# RF08bOmnibus.net
KiCad netlist of a schematic drawn in EAGLE
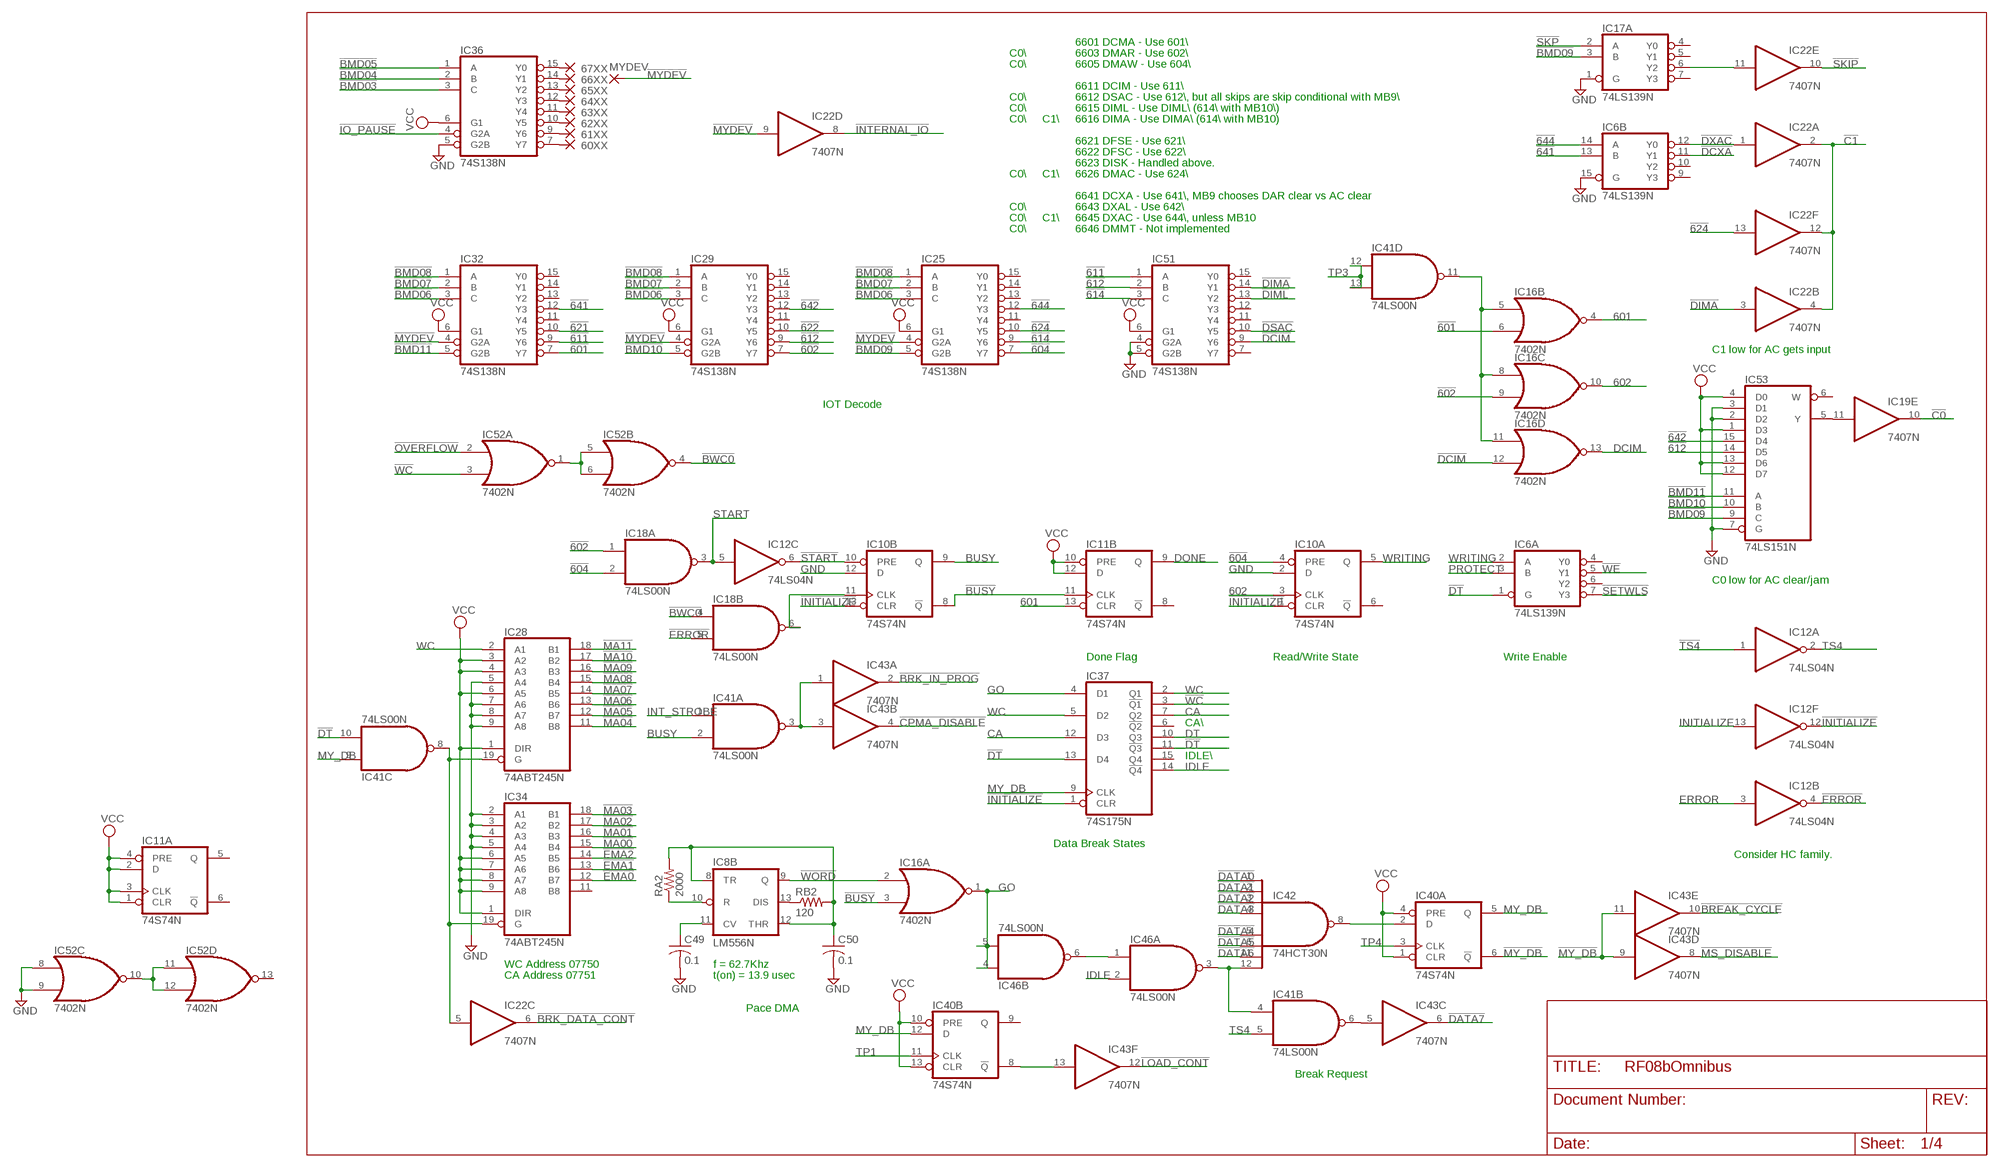
[diagram p0: schematic, sheet 1]
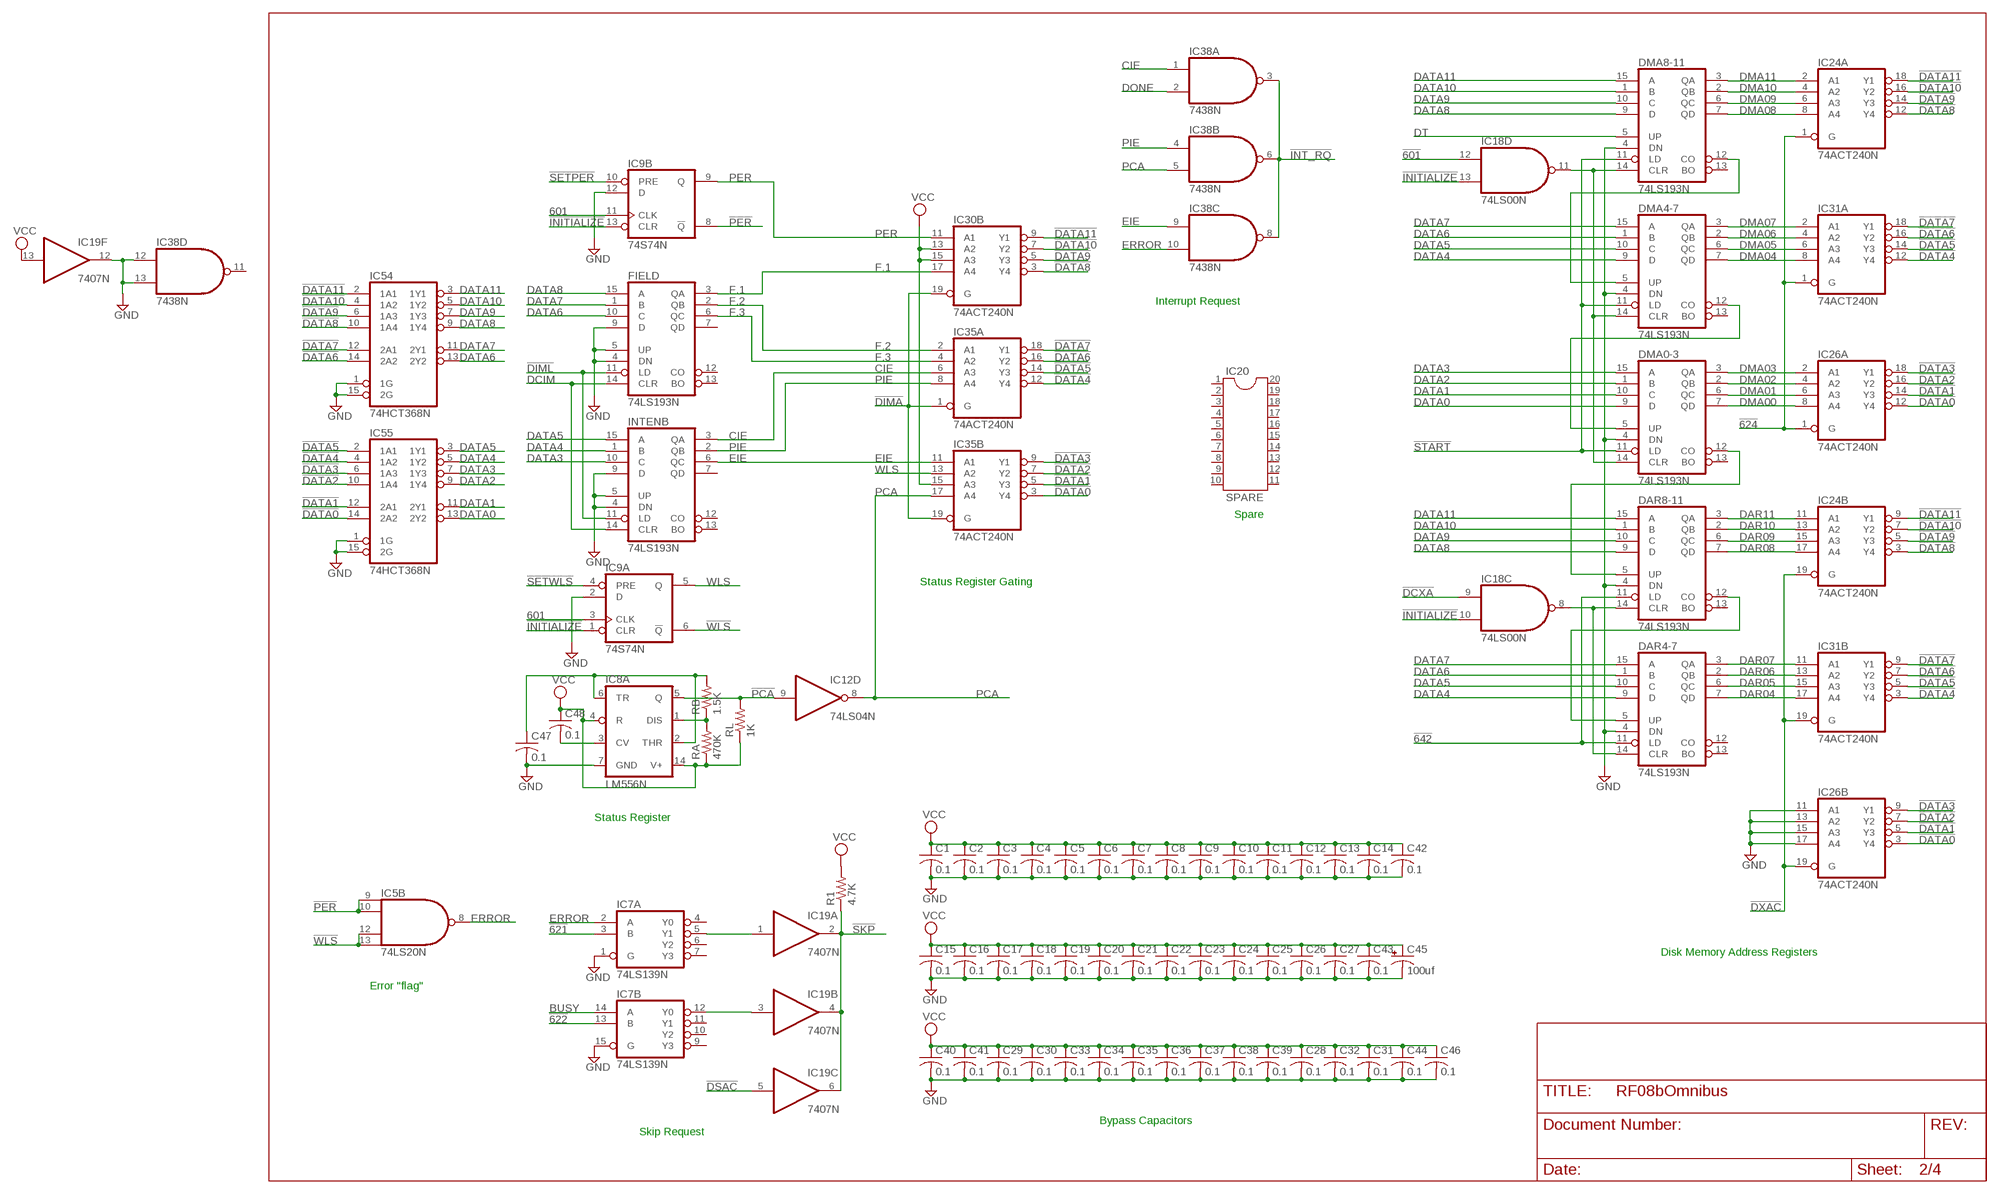
[diagram p1: schematic, sheet 2]
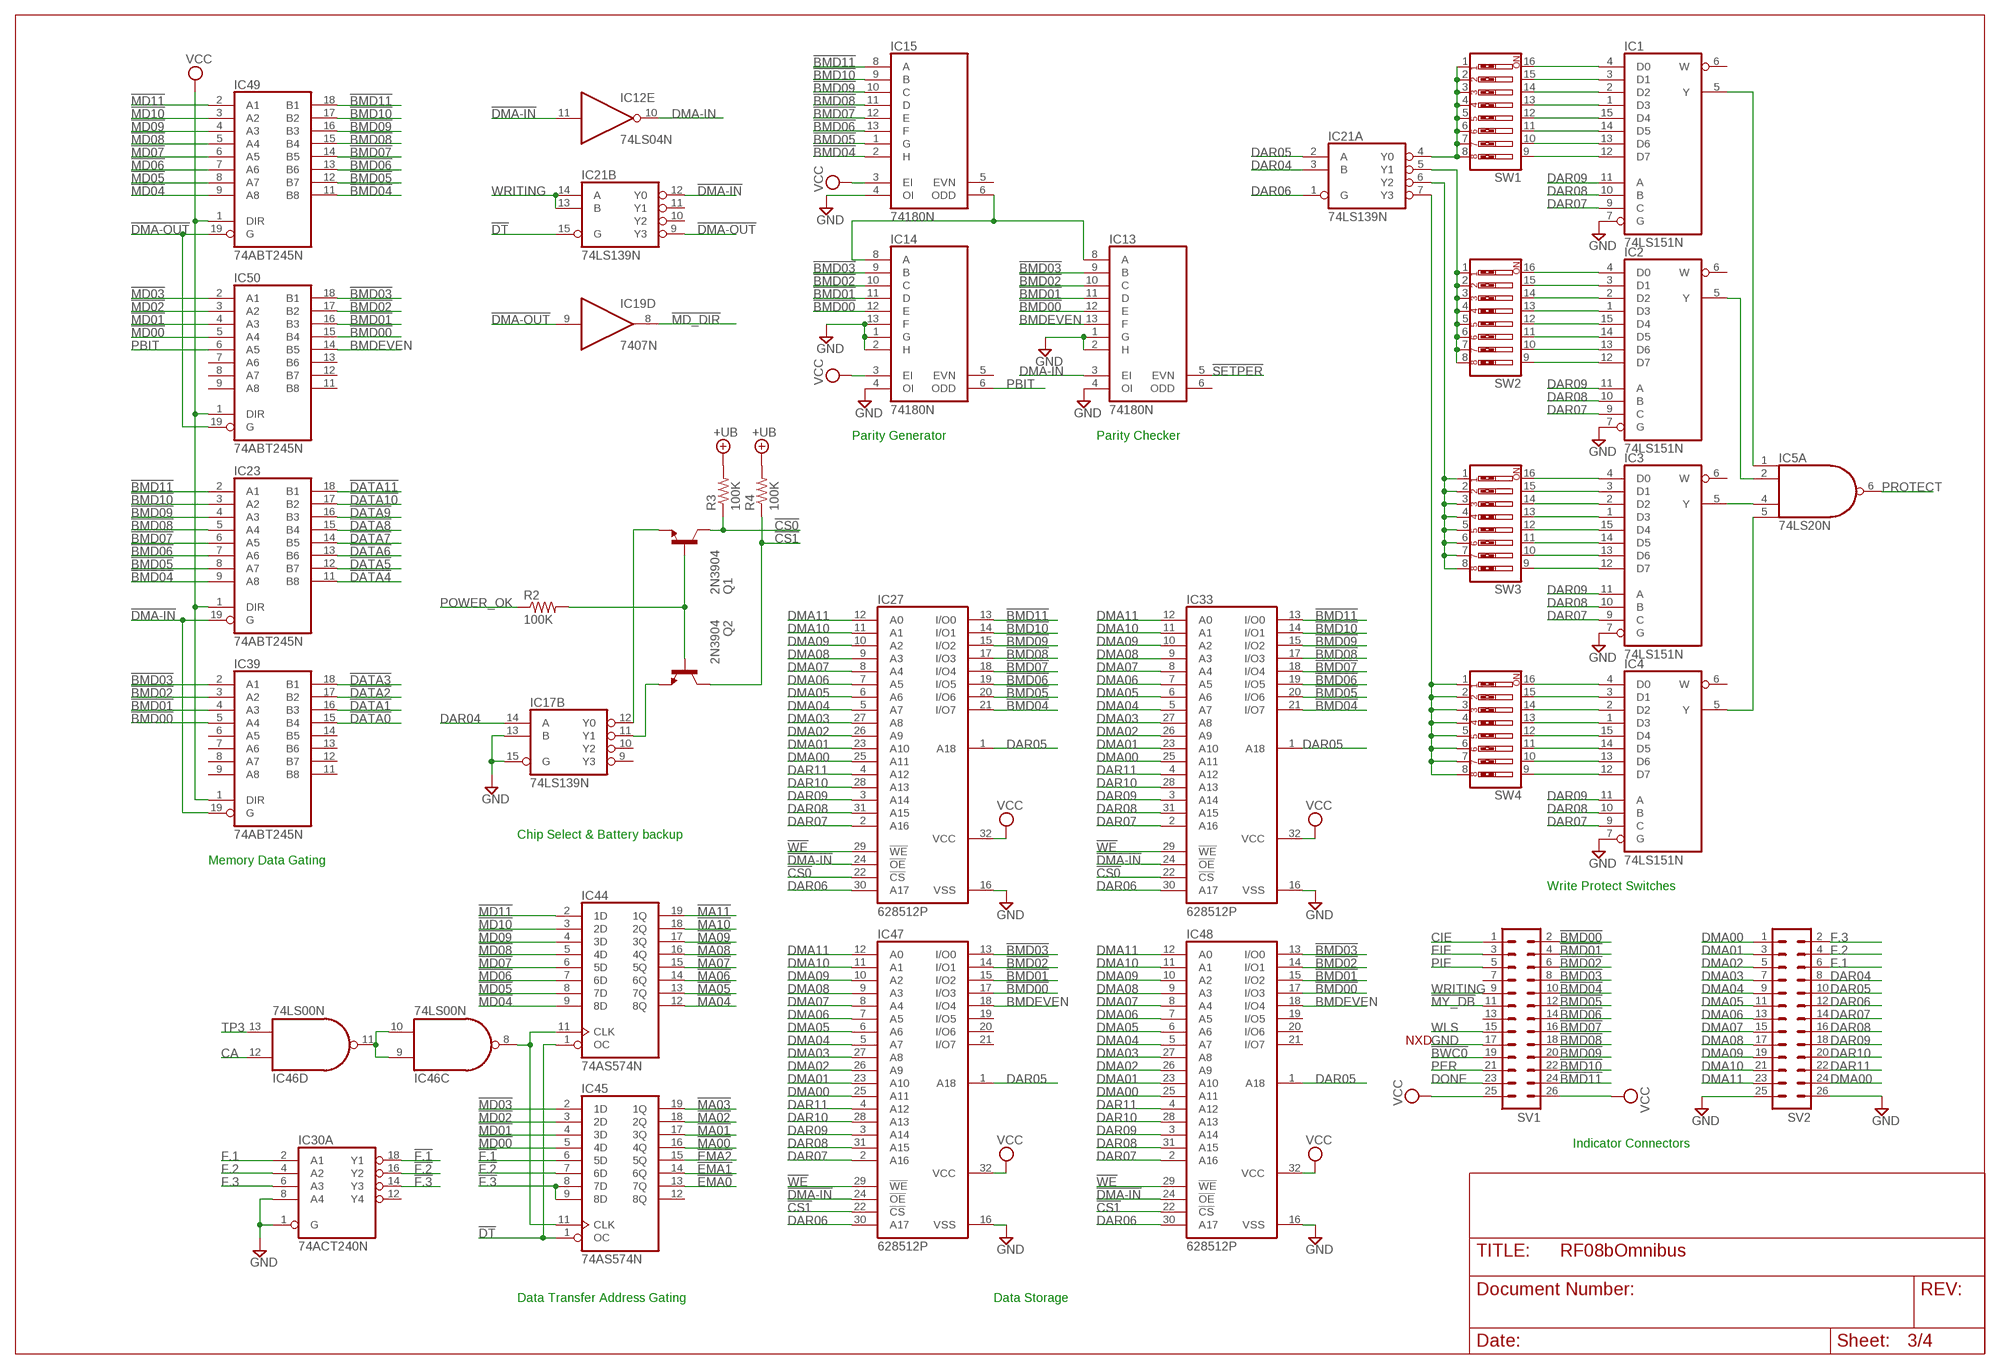
[diagram p2: schematic, sheet 3]
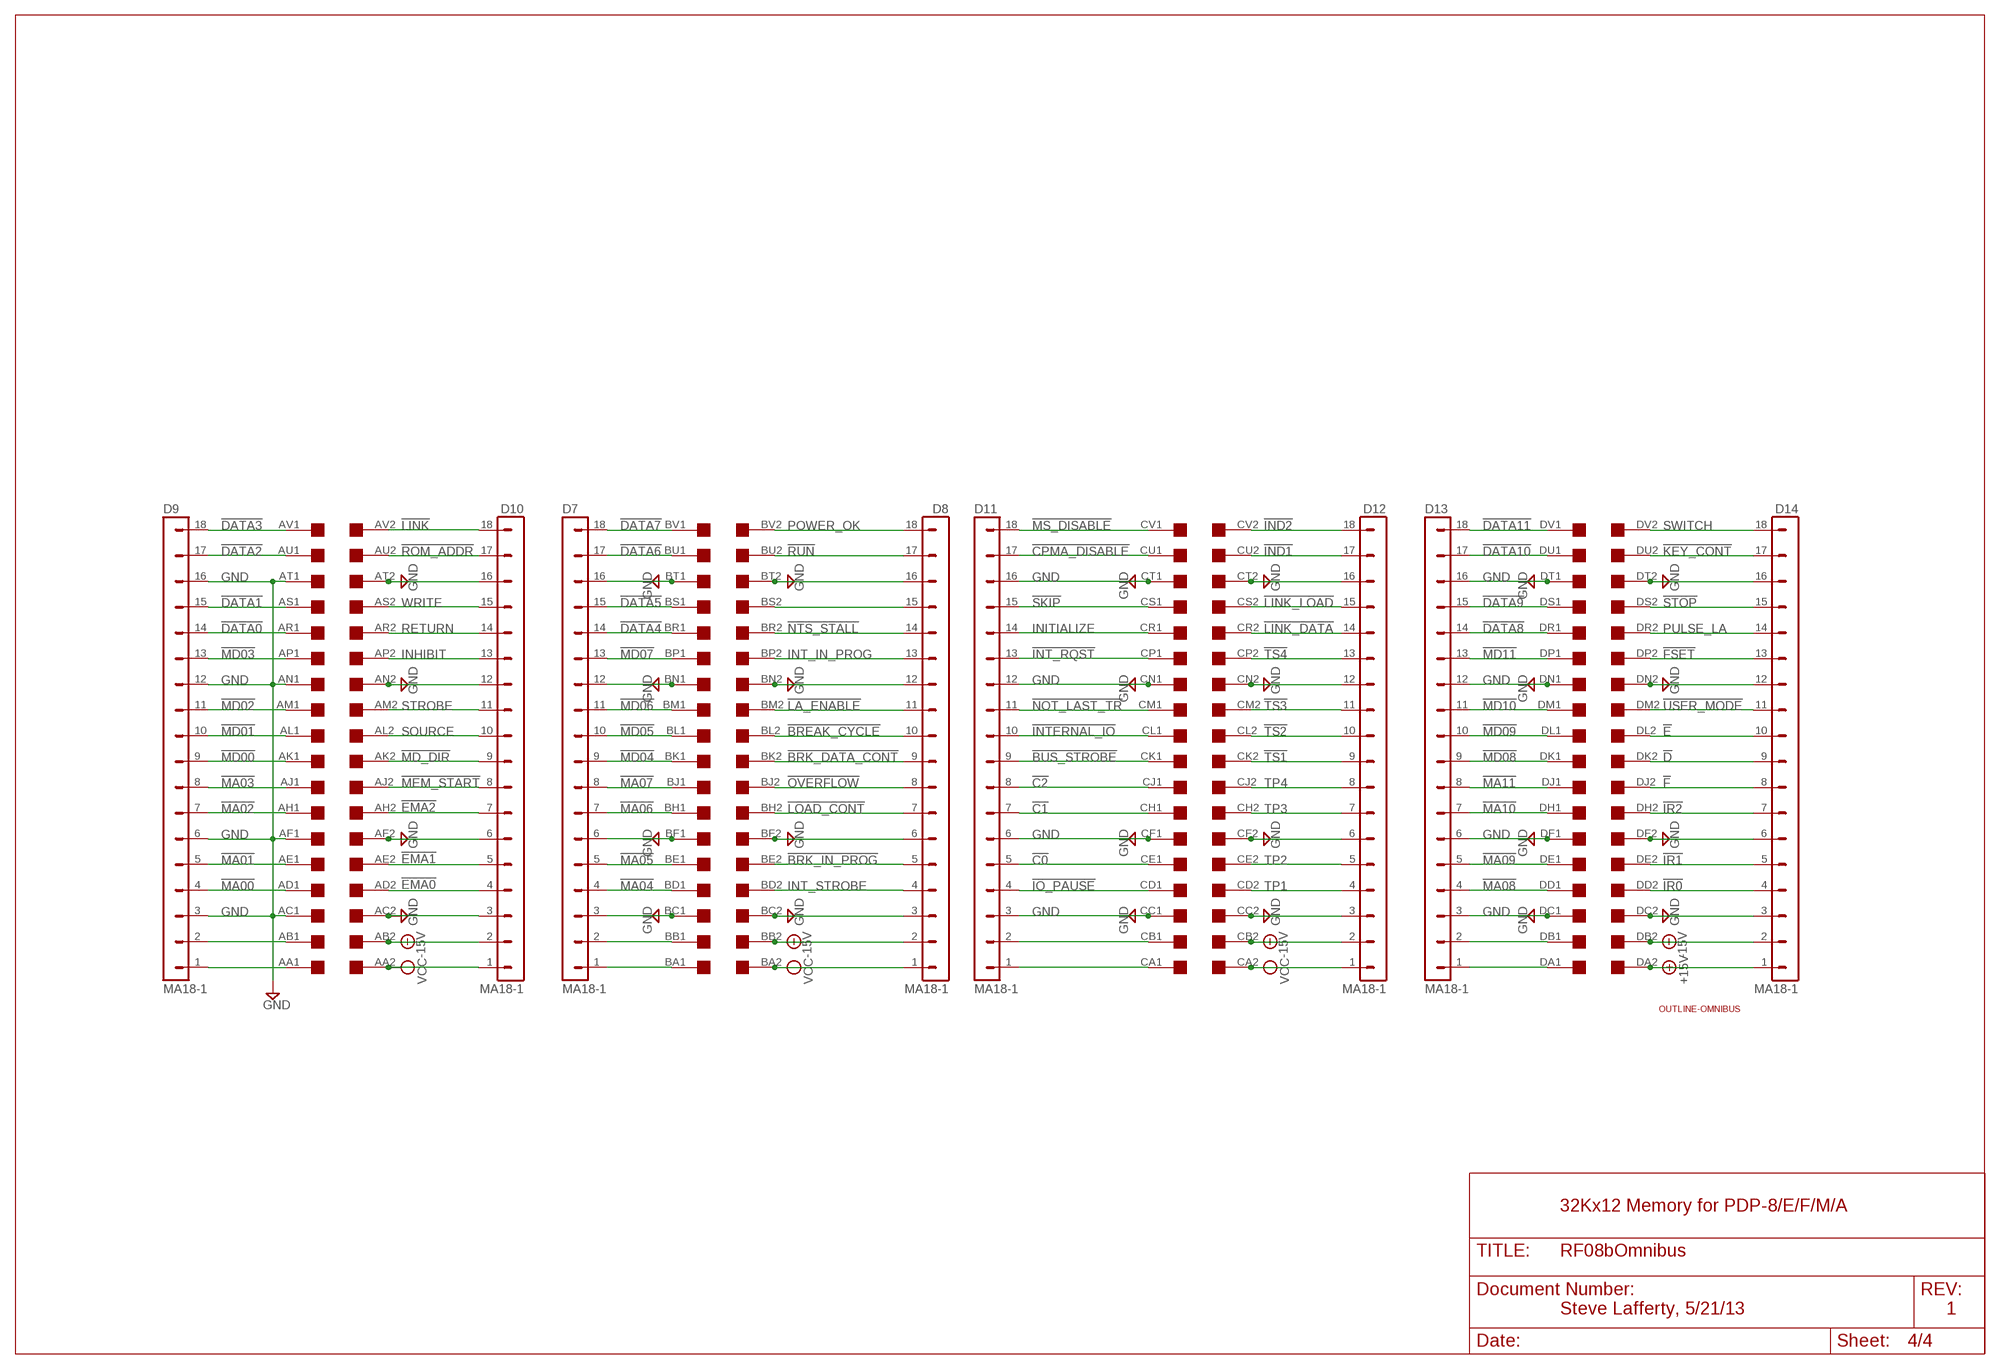
[diagram p3: schematic, sheet 4]

(export (version "E")
  (design (tool "Eeschema 10.0.6"))
  (components
    (comp (ref "D7")
      (value "MA18-1")
      (footprint "eagle-import:MA18-1")
      (libsource (lib "eagle-import") (part "MA18-1"))
    )
    (comp (ref "D8")
      (value "MA18-1")
      (footprint "eagle-import:MA18-1")
      (libsource (lib "eagle-import") (part "MA18-1"))
    )
    (comp (ref "D9")
      (value "MA18-1")
      (footprint "eagle-import:MA18-1")
      (libsource (lib "eagle-import") (part "MA18-1"))
    )
    (comp (ref "D10")
      (value "MA18-1")
      (footprint "eagle-import:MA18-1")
      (libsource (lib "eagle-import") (part "MA18-1"))
    )
    (comp (ref "D11")
      (value "MA18-1")
      (footprint "eagle-import:MA18-1")
      (libsource (lib "eagle-import") (part "MA18-1"))
    )
    (comp (ref "D12")
      (value "MA18-1")
      (footprint "eagle-import:MA18-1")
      (libsource (lib "eagle-import") (part "MA18-1"))
    )
    (comp (ref "D13")
      (value "MA18-1")
      (footprint "eagle-import:MA18-1")
      (libsource (lib "eagle-import") (part "MA18-1"))
    )
    (comp (ref "D14")
      (value "MA18-1")
      (footprint "eagle-import:MA18-1")
      (libsource (lib "eagle-import") (part "MA18-1"))
    )
    (comp (ref "U$15")
      (value "OUTLINE-OMNIBUS")
      (footprint "eagle-import:OMNIBUS")
      (libsource (lib "eagle-import") (part "OUTLINE-OMNIBUS"))
    )
    (comp (ref "U$19")
      (value "QUAD")
      (footprint "eagle-import:EDGE-CON8")
      (libsource (lib "eagle-import") (part "QUAD"))
    )
    (comp (ref "IC1")
      (value "74LS151N")
      (footprint "eagle-import:DIL16")
      (libsource (lib "eagle-import") (part "74151NLS"))
    )
    (comp (ref "IC2")
      (value "74LS151N")
      (footprint "eagle-import:DIL16")
      (libsource (lib "eagle-import") (part "74151NLS"))
    )
    (comp (ref "IC3")
      (value "74LS151N")
      (footprint "eagle-import:DIL16")
      (libsource (lib "eagle-import") (part "74151NLS"))
    )
    (comp (ref "IC4")
      (value "74LS151N")
      (footprint "eagle-import:DIL16")
      (libsource (lib "eagle-import") (part "74151NLS"))
    )
    (comp (ref "IC5")
      (value "74LS20N")
      (footprint "eagle-import:DIL14")
      (libsource (lib "eagle-import") (part "7420NLS"))
    )
    (comp (ref "IC12")
      (value "74LS04N")
      (footprint "eagle-import:DIL14")
      (libsource (lib "eagle-import") (part "7404NLS"))
    )
    (comp (ref "IC13")
      (value "74180N")
      (footprint "eagle-import:DIL14")
      (libsource (lib "eagle-import") (part "74180N"))
    )
    (comp (ref "IC14")
      (value "74180N")
      (footprint "eagle-import:DIL14")
      (libsource (lib "eagle-import") (part "74180N"))
    )
    (comp (ref "IC15")
      (value "74180N")
      (footprint "eagle-import:DIL14")
      (libsource (lib "eagle-import") (part "74180N"))
    )
    (comp (ref "IC17")
      (value "74LS139N")
      (footprint "eagle-import:DIL16")
      (libsource (lib "eagle-import") (part "74139NS"))
    )
    (comp (ref "IC19")
      (value "7407N")
      (footprint "eagle-import:DIL14")
      (libsource (lib "eagle-import") (part "7407N"))
    )
    (comp (ref "IC21")
      (value "74LS139N")
      (footprint "eagle-import:DIL16")
      (libsource (lib "eagle-import") (part "74139NLS"))
    )
    (comp (ref "IC23")
      (value "74ABT245N")
      (footprint "eagle-import:DIL20")
      (libsource (lib "eagle-import") (part "74245NLS"))
    )
    (comp (ref "IC27")
      (value "628512P")
      (footprint "eagle-import:DIL32")
      (libsource (lib "eagle-import") (part "628512P"))
    )
    (comp (ref "IC30")
      (value "74ACT240N")
      (footprint "eagle-import:DIL20")
      (libsource (lib "eagle-import") (part "74240NLS"))
    )
    (comp (ref "IC33")
      (value "628512P")
      (footprint "eagle-import:DIL32")
      (libsource (lib "eagle-import") (part "628512P"))
    )
    (comp (ref "IC39")
      (value "74ABT245N")
      (footprint "eagle-import:DIL20")
      (libsource (lib "eagle-import") (part "74245NLS"))
    )
    (comp (ref "IC44")
      (value "74AS574N")
      (footprint "eagle-import:DIL20")
      (libsource (lib "eagle-import") (part "74574NAS"))
    )
    (comp (ref "IC45")
      (value "74AS574N")
      (footprint "eagle-import:DIL20")
      (libsource (lib "eagle-import") (part "74574NAS"))
    )
    (comp (ref "IC46")
      (value "74LS00N")
      (footprint "eagle-import:DIL14")
      (libsource (lib "eagle-import") (part "7400NLS"))
    )
    (comp (ref "IC47")
      (value "628512P")
      (footprint "eagle-import:DIL32")
      (libsource (lib "eagle-import") (part "628512P"))
    )
    (comp (ref "IC48")
      (value "628512P")
      (footprint "eagle-import:DIL32")
      (libsource (lib "eagle-import") (part "628512P"))
    )
    (comp (ref "IC49")
      (value "74ABT245N")
      (footprint "eagle-import:DIL20")
      (libsource (lib "eagle-import") (part "74245NLS"))
    )
    (comp (ref "IC50")
      (value "74ABT245N")
      (footprint "eagle-import:DIL20")
      (libsource (lib "eagle-import") (part "74245NLS"))
    )
    (comp (ref "Q1")
      (value "2N3904")
      (footprint "eagle-import:TO92")
      (libsource (lib "eagle-import") (part "2N3904"))
    )
    (comp (ref "Q2")
      (value "2N3904")
      (footprint "eagle-import:TO92")
      (libsource (lib "eagle-import") (part "2N3904"))
    )
    (comp (ref "R2")
      (value "100K")
      (footprint "eagle-import:0207_10")
      (libsource (lib "eagle-import") (part "R-US_0207/10"))
    )
    (comp (ref "R3")
      (value "100K")
      (footprint "eagle-import:0207_10")
      (libsource (lib "eagle-import") (part "R-US_0207/10"))
    )
    (comp (ref "R4")
      (value "100K")
      (footprint "eagle-import:0207_10")
      (libsource (lib "eagle-import") (part "R-US_0207/10"))
    )
    (comp (ref "SV1")
      (value "MA13-2")
      (footprint "eagle-import:MA13-2")
      (libsource (lib "eagle-import") (part "MA13-2"))
    )
    (comp (ref "SV2")
      (value "MA13-2")
      (footprint "eagle-import:MA13-2")
      (libsource (lib "eagle-import") (part "MA13-2"))
    )
    (comp (ref "SW1")
      (value "SW_DIP-8")
      (footprint "eagle-import:EDG-08")
      (libsource (lib "eagle-import") (part "SW_DIP-8"))
    )
    (comp (ref "SW2")
      (value "SW_DIP-8")
      (footprint "eagle-import:EDG-08")
      (libsource (lib "eagle-import") (part "SW_DIP-8"))
    )
    (comp (ref "SW3")
      (value "SW_DIP-8")
      (footprint "eagle-import:EDG-08")
      (libsource (lib "eagle-import") (part "SW_DIP-8"))
    )
    (comp (ref "SW4")
      (value "SW_DIP-8")
      (footprint "eagle-import:EDG-08")
      (libsource (lib "eagle-import") (part "SW_DIP-8"))
    )
    (comp (ref "60XX")
      (value "1,6/0,8")
      (footprint "eagle-import:1,6_0,8")
      (libsource (lib "eagle-import") (part "1,6/0,8"))
    )
    (comp (ref "61XX")
      (value "1,6/0,8")
      (footprint "eagle-import:1,6_0,8")
      (libsource (lib "eagle-import") (part "1,6/0,8"))
    )
    (comp (ref "62XX")
      (value "1,6/0,8")
      (footprint "eagle-import:1,6_0,8")
      (libsource (lib "eagle-import") (part "1,6/0,8"))
    )
    (comp (ref "63XX")
      (value "1,6/0,8")
      (footprint "eagle-import:1,6_0,8")
      (libsource (lib "eagle-import") (part "1,6/0,8"))
    )
    (comp (ref "64XX")
      (value "1,6/0,8")
      (footprint "eagle-import:1,6_0,8")
      (libsource (lib "eagle-import") (part "1,6/0,8"))
    )
    (comp (ref "65XX")
      (value "1,6/0,8")
      (footprint "eagle-import:1,6_0,8")
      (libsource (lib "eagle-import") (part "1,6/0,8"))
    )
    (comp (ref "66XX")
      (value "1,6/0,8")
      (footprint "eagle-import:1,6_0,8")
      (libsource (lib "eagle-import") (part "1,6/0,8"))
    )
    (comp (ref "67XX")
      (value "1,6/0,8")
      (footprint "eagle-import:1,6_0,8")
      (libsource (lib "eagle-import") (part "1,6/0,8"))
    )
    (comp (ref "C49")
      (value "0.1")
      (footprint "eagle-import:C050-025X075")
      (libsource (lib "eagle-import") (part "C-US050-025X075"))
    )
    (comp (ref "C50")
      (value "0.1")
      (footprint "eagle-import:C050-025X075")
      (libsource (lib "eagle-import") (part "C-US050-025X075"))
    )
    (comp (ref "IC6")
      (value "74LS139N")
      (footprint "eagle-import:DIL16")
      (libsource (lib "eagle-import") (part "74139NS"))
    )
    (comp (ref "IC8")
      (value "LM556N")
      (footprint "eagle-import:DIL14")
      (libsource (lib "eagle-import") (part "556NLM"))
    )
    (comp (ref "IC10")
      (value "74S74N")
      (footprint "eagle-import:DIL14")
      (libsource (lib "eagle-import") (part "7474NS"))
    )
    (comp (ref "IC11")
      (value "74S74N")
      (footprint "eagle-import:DIL14")
      (libsource (lib "eagle-import") (part "7474NS"))
    )
    (comp (ref "IC16")
      (value "7402N")
      (footprint "eagle-import:DIL14")
      (libsource (lib "eagle-import") (part "7402N"))
    )
    (comp (ref "IC18")
      (value "74LS00N")
      (footprint "eagle-import:DIL14")
      (libsource (lib "eagle-import") (part "7400NLS"))
    )
    (comp (ref "IC22")
      (value "7407N")
      (footprint "eagle-import:DIL14")
      (libsource (lib "eagle-import") (part "7407N"))
    )
    (comp (ref "IC25")
      (value "74S138N")
      (footprint "eagle-import:DIL16")
      (libsource (lib "eagle-import") (part "74138NS"))
    )
    (comp (ref "IC28")
      (value "74ABT245N")
      (footprint "eagle-import:DIL20")
      (libsource (lib "eagle-import") (part "74245NLS"))
    )
    (comp (ref "IC29")
      (value "74S138N")
      (footprint "eagle-import:DIL16")
      (libsource (lib "eagle-import") (part "74138NS"))
    )
    (comp (ref "IC32")
      (value "74S138N")
      (footprint "eagle-import:DIL16")
      (libsource (lib "eagle-import") (part "74138NS"))
    )
    (comp (ref "IC34")
      (value "74ABT245N")
      (footprint "eagle-import:DIL20")
      (libsource (lib "eagle-import") (part "74245NLS"))
    )
    (comp (ref "IC36")
      (value "74S138N")
      (footprint "eagle-import:DIL16")
      (libsource (lib "eagle-import") (part "74138NS"))
    )
    (comp (ref "IC37")
      (value "74S175N")
      (footprint "eagle-import:DIL16")
      (libsource (lib "eagle-import") (part "74175NS"))
    )
    (comp (ref "IC40")
      (value "74S74N")
      (footprint "eagle-import:DIL14")
      (libsource (lib "eagle-import") (part "7474NS"))
    )
    (comp (ref "IC41")
      (value "74LS00N")
      (footprint "eagle-import:DIL14")
      (libsource (lib "eagle-import") (part "7400NLS"))
    )
    (comp (ref "IC42")
      (value "74HCT30N")
      (footprint "eagle-import:DIL14")
      (libsource (lib "eagle-import") (part "7430NLS"))
    )
    (comp (ref "IC43")
      (value "7407N")
      (footprint "eagle-import:DIL14")
      (libsource (lib "eagle-import") (part "7407N"))
    )
    (comp (ref "IC51")
      (value "74S138N")
      (footprint "eagle-import:DIL16")
      (libsource (lib "eagle-import") (part "74138NS"))
    )
    (comp (ref "IC52")
      (value "7402N")
      (footprint "eagle-import:DIL14")
      (libsource (lib "eagle-import") (part "7402N"))
    )
    (comp (ref "IC53")
      (value "74LS151N")
      (footprint "eagle-import:DIL16")
      (libsource (lib "eagle-import") (part "74151NLS"))
    )
    (comp (ref "MYDEV")
      (value "1,6/0,8")
      (footprint "eagle-import:1,6_0,8")
      (libsource (lib "eagle-import") (part "1,6/0,8"))
    )
    (comp (ref "RA2")
      (value "2000")
      (footprint "eagle-import:0207_10")
      (libsource (lib "eagle-import") (part "R-US_0207/10"))
    )
    (comp (ref "RB2")
      (value "120")
      (footprint "eagle-import:0207_10")
      (libsource (lib "eagle-import") (part "R-US_0207/10"))
    )
    (comp (ref "C1")
      (value "0.1")
      (footprint "eagle-import:C050-025X075")
      (libsource (lib "eagle-import") (part "C-US050-025X075"))
    )
    (comp (ref "C2")
      (value "0.1")
      (footprint "eagle-import:C050-025X075")
      (libsource (lib "eagle-import") (part "C-US050-025X075"))
    )
    (comp (ref "C3")
      (value "0.1")
      (footprint "eagle-import:C050-025X075")
      (libsource (lib "eagle-import") (part "C-US050-025X075"))
    )
    (comp (ref "C4")
      (value "0.1")
      (footprint "eagle-import:C050-025X075")
      (libsource (lib "eagle-import") (part "C-US050-025X075"))
    )
    (comp (ref "C5")
      (value "0.1")
      (footprint "eagle-import:C050-025X075")
      (libsource (lib "eagle-import") (part "C-US050-025X075"))
    )
    (comp (ref "C6")
      (value "0.1")
      (footprint "eagle-import:C050-025X075")
      (libsource (lib "eagle-import") (part "C-US050-025X075"))
    )
    (comp (ref "C7")
      (value "0.1")
      (footprint "eagle-import:C050-025X075")
      (libsource (lib "eagle-import") (part "C-US050-025X075"))
    )
    (comp (ref "C8")
      (value "0.1")
      (footprint "eagle-import:C050-025X075")
      (libsource (lib "eagle-import") (part "C-US050-025X075"))
    )
    (comp (ref "C9")
      (value "0.1")
      (footprint "eagle-import:C050-025X075")
      (libsource (lib "eagle-import") (part "C-US050-025X075"))
    )
    (comp (ref "C10")
      (value "0.1")
      (footprint "eagle-import:C050-025X075")
      (libsource (lib "eagle-import") (part "C-US050-025X075"))
    )
    (comp (ref "C11")
      (value "0.1")
      (footprint "eagle-import:C050-025X075")
      (libsource (lib "eagle-import") (part "C-US050-025X075"))
    )
    (comp (ref "C12")
      (value "0.1")
      (footprint "eagle-import:C050-025X075")
      (libsource (lib "eagle-import") (part "C-US050-025X075"))
    )
    (comp (ref "C13")
      (value "0.1")
      (footprint "eagle-import:C050-025X075")
      (libsource (lib "eagle-import") (part "C-US050-025X075"))
    )
    (comp (ref "C14")
      (value "0.1")
      (footprint "eagle-import:C050-025X075")
      (libsource (lib "eagle-import") (part "C-US050-025X075"))
    )
    (comp (ref "C15")
      (value "0.1")
      (footprint "eagle-import:C050-025X075")
      (libsource (lib "eagle-import") (part "C-US050-025X075"))
    )
    (comp (ref "C16")
      (value "0.1")
      (footprint "eagle-import:C050-025X075")
      (libsource (lib "eagle-import") (part "C-US050-025X075"))
    )
    (comp (ref "C17")
      (value "0.1")
      (footprint "eagle-import:C050-025X075")
      (libsource (lib "eagle-import") (part "C-US050-025X075"))
    )
    (comp (ref "C18")
      (value "0.1")
      (footprint "eagle-import:C050-025X075")
      (libsource (lib "eagle-import") (part "C-US050-025X075"))
    )
    (comp (ref "C19")
      (value "0.1")
      (footprint "eagle-import:C050-025X075")
      (libsource (lib "eagle-import") (part "C-US050-025X075"))
    )
    (comp (ref "C20")
      (value "0.1")
      (footprint "eagle-import:C050-025X075")
      (libsource (lib "eagle-import") (part "C-US050-025X075"))
    )
    (comp (ref "C21")
      (value "0.1")
      (footprint "eagle-import:C050-025X075")
      (libsource (lib "eagle-import") (part "C-US050-025X075"))
    )
    (comp (ref "C22")
      (value "0.1")
      (footprint "eagle-import:C050-025X075")
      (libsource (lib "eagle-import") (part "C-US050-025X075"))
    )
    (comp (ref "C23")
      (value "0.1")
      (footprint "eagle-import:C050-025X075")
      (libsource (lib "eagle-import") (part "C-US050-025X075"))
    )
    (comp (ref "C24")
      (value "0.1")
      (footprint "eagle-import:C050-025X075")
      (libsource (lib "eagle-import") (part "C-US050-025X075"))
    )
    (comp (ref "C25")
      (value "0.1")
      (footprint "eagle-import:C050-025X075")
      (libsource (lib "eagle-import") (part "C-US050-025X075"))
    )
    (comp (ref "C26")
      (value "0.1")
      (footprint "eagle-import:C050-025X075")
      (libsource (lib "eagle-import") (part "C-US050-025X075"))
    )
    (comp (ref "C27")
      (value "0.1")
      (footprint "eagle-import:C050-025X075")
      (libsource (lib "eagle-import") (part "C-US050-025X075"))
    )
    (comp (ref "C28")
      (value "0.1")
      (footprint "eagle-import:C050-025X075")
      (libsource (lib "eagle-import") (part "C-US050-025X075"))
    )
    (comp (ref "C29")
      (value "0.1")
      (footprint "eagle-import:C050-025X075")
      (libsource (lib "eagle-import") (part "C-US050-025X075"))
    )
    (comp (ref "C30")
      (value "0.1")
      (footprint "eagle-import:C050-025X075")
      (libsource (lib "eagle-import") (part "C-US050-025X075"))
    )
    (comp (ref "C31")
      (value "0.1")
      (footprint "eagle-import:C050-025X075")
      (libsource (lib "eagle-import") (part "C-US050-025X075"))
    )
    (comp (ref "C32")
      (value "0.1")
      (footprint "eagle-import:C050-025X075")
      (libsource (lib "eagle-import") (part "C-US050-025X075"))
    )
    (comp (ref "C33")
      (value "0.1")
      (footprint "eagle-import:C050-025X075")
      (libsource (lib "eagle-import") (part "C-US050-025X075"))
    )
    (comp (ref "C34")
      (value "0.1")
      (footprint "eagle-import:C050-025X075")
      (libsource (lib "eagle-import") (part "C-US050-025X075"))
    )
    (comp (ref "C35")
      (value "0.1")
      (footprint "eagle-import:C050-025X075")
      (libsource (lib "eagle-import") (part "C-US050-025X075"))
    )
    (comp (ref "C36")
      (value "0.1")
      (footprint "eagle-import:C050-025X075")
      (libsource (lib "eagle-import") (part "C-US050-025X075"))
    )
    (comp (ref "C37")
      (value "0.1")
      (footprint "eagle-import:C050-025X075")
      (libsource (lib "eagle-import") (part "C-US050-025X075"))
    )
    (comp (ref "C38")
      (value "0.1")
      (footprint "eagle-import:C050-025X075")
      (libsource (lib "eagle-import") (part "C-US050-025X075"))
    )
    (comp (ref "C39")
      (value "0.1")
      (footprint "eagle-import:C050-025X075")
      (libsource (lib "eagle-import") (part "C-US050-025X075"))
    )
    (comp (ref "C40")
      (value "0.1")
      (footprint "eagle-import:C050-025X075")
      (libsource (lib "eagle-import") (part "C-US050-025X075"))
    )
    (comp (ref "C41")
      (value "0.1")
      (footprint "eagle-import:C050-025X075")
      (libsource (lib "eagle-import") (part "C-US050-025X075"))
    )
    (comp (ref "C42")
      (value "0.1")
      (footprint "eagle-import:C050-025X075")
      (libsource (lib "eagle-import") (part "C-US050-025X075"))
    )
    (comp (ref "C43")
      (value "0.1")
      (footprint "eagle-import:C050-025X075")
      (libsource (lib "eagle-import") (part "C-US050-025X075"))
    )
    (comp (ref "C44")
      (value "0.1")
      (footprint "eagle-import:C050-025X075")
      (libsource (lib "eagle-import") (part "C-US050-025X075"))
    )
    (comp (ref "C45")
      (value "100uf")
      (footprint "eagle-import:E22-6")
      (libsource (lib "eagle-import") (part "CPOL-USE22-6AXIAL"))
    )
    (comp (ref "C46")
      (value "0.1")
      (footprint "eagle-import:C050-025X075")
      (libsource (lib "eagle-import") (part "C-US050-025X075"))
    )
    (comp (ref "C47")
      (value "0.1")
      (footprint "eagle-import:C050-025X075")
      (libsource (lib "eagle-import") (part "C-US050-025X075"))
    )
    (comp (ref "C48")
      (value "0.1")
      (footprint "eagle-import:C050-025X075")
      (libsource (lib "eagle-import") (part "C-US050-025X075"))
    )
    (comp (ref "DAR4-7")
      (value "74LS193N")
      (footprint "eagle-import:DIL16")
      (libsource (lib "eagle-import") (part "74192NLS"))
    )
    (comp (ref "DAR8-11")
      (value "74LS193N")
      (footprint "eagle-import:DIL16")
      (libsource (lib "eagle-import") (part "74192NLS"))
    )
    (comp (ref "DMA0-3")
      (value "74LS193N")
      (footprint "eagle-import:DIL16")
      (libsource (lib "eagle-import") (part "74192NLS"))
    )
    (comp (ref "DMA4-7")
      (value "74LS193N")
      (footprint "eagle-import:DIL16")
      (libsource (lib "eagle-import") (part "74192NLS"))
    )
    (comp (ref "DMA8-11")
      (value "74LS193N")
      (footprint "eagle-import:DIL16")
      (libsource (lib "eagle-import") (part "74192NLS"))
    )
    (comp (ref "FIELD")
      (value "74LS193N")
      (footprint "eagle-import:DIL16")
      (libsource (lib "eagle-import") (part "74192NLS"))
    )
    (comp (ref "IC7")
      (value "74LS139N")
      (footprint "eagle-import:DIL16")
      (libsource (lib "eagle-import") (part "74139NLS"))
    )
    (comp (ref "IC9")
      (value "74S74N")
      (footprint "eagle-import:DIL14")
      (libsource (lib "eagle-import") (part "7474NS"))
    )
    (comp (ref "IC20")
      (value "SPARE")
      (footprint "eagle-import:DIL20")
      (libsource (lib "eagle-import") (part "DIL20"))
    )
    (comp (ref "IC24")
      (value "74ACT240N")
      (footprint "eagle-import:DIL20")
      (libsource (lib "eagle-import") (part "74240NLS"))
    )
    (comp (ref "IC26")
      (value "74ACT240N")
      (footprint "eagle-import:DIL20")
      (libsource (lib "eagle-import") (part "74240NLS"))
    )
    (comp (ref "IC31")
      (value "74ACT240N")
      (footprint "eagle-import:DIL20")
      (libsource (lib "eagle-import") (part "74240NLS"))
    )
    (comp (ref "IC35")
      (value "74ACT240N")
      (footprint "eagle-import:DIL20")
      (libsource (lib "eagle-import") (part "74240NLS"))
    )
    (comp (ref "IC38")
      (value "7438N")
      (footprint "eagle-import:DIL14")
      (libsource (lib "eagle-import") (part "7438N"))
    )
    (comp (ref "IC54")
      (value "74HCT368N")
      (footprint "eagle-import:DIL16")
      (libsource (lib "eagle-import") (part "74368N"))
    )
    (comp (ref "IC55")
      (value "74HCT368N")
      (footprint "eagle-import:DIL16")
      (libsource (lib "eagle-import") (part "74368N"))
    )
    (comp (ref "INTENB")
      (value "74LS193N")
      (footprint "eagle-import:DIL16")
      (libsource (lib "eagle-import") (part "74192NLS"))
    )
    (comp (ref "R1")
      (value "4.7K")
      (footprint "eagle-import:0207_10")
      (libsource (lib "eagle-import") (part "R-US_0207/10"))
    )
    (comp (ref "RA")
      (value "470K")
      (footprint "eagle-import:0207_10")
      (libsource (lib "eagle-import") (part "R-US_0207/10"))
    )
    (comp (ref "RB")
      (value "1.5K")
      (footprint "eagle-import:0207_10")
      (libsource (lib "eagle-import") (part "R-US_0207/10"))
    )
    (comp (ref "RL")
      (value "1K")
      (footprint "eagle-import:0207_10")
      (libsource (lib "eagle-import") (part "R-US_0207/10"))
    )
  )
  (nets
    (net (code "1") (name "+15V") (class "Default")
      (node (ref "D14") (pin "1") (pinfunction "1_1") (pintype "passive"))
      (node (ref "U$19") (pin "DA2") (pinfunction "1_DA2") (pintype "bidirectional"))
    )
    (net (code "2") (name "+UB") (class "Default")
      (node (ref "R3") (pin "2") (pinfunction "2_2") (pintype "passive"))
      (node (ref "R4") (pin "2") (pinfunction "2_2") (pintype "passive"))
    )
    (net (code "3") (name "-15V") (class "Default")
      (node (ref "D10") (pin "2") (pinfunction "2_2") (pintype "passive"))
      (node (ref "D12") (pin "2") (pinfunction "2_2") (pintype "passive"))
      (node (ref "D14") (pin "2") (pinfunction "2_2") (pintype "passive"))
      (node (ref "D8") (pin "2") (pinfunction "2_2") (pintype "passive"))
      (node (ref "U$19") (pin "AB2") (pinfunction "1_AB2") (pintype "bidirectional"))
      (node (ref "U$19") (pin "BB2") (pinfunction "1_BB2") (pintype "bidirectional"))
      (node (ref "U$19") (pin "CB2") (pinfunction "1_CB2") (pintype "bidirectional"))
      (node (ref "U$19") (pin "DB2") (pinfunction "1_DB2") (pintype "bidirectional"))
    )
    (net (code "4") (name "601") (class "Default")
      (node (ref "IC11") (pin "13") (pinfunction "CLR_13") (pintype "input"))
      (node (ref "IC16") (pin "4") (pinfunction "O_4") (pintype "output"))
      (node (ref "IC9") (pin "11") (pinfunction "CLK_11") (pintype "input"))
      (node (ref "IC9") (pin "3") (pinfunction "CLK_3") (pintype "input"))
    )
    (net (code "5") (name "602") (class "Default")
      (node (ref "IC10") (pin "3") (pinfunction "CLK_3") (pintype "input"))
      (node (ref "IC16") (pin "10") (pinfunction "O_10") (pintype "output"))
    )
    (net (code "6") (name "BMDEVEN") (class "Default")
      (node (ref "IC13") (pin "13") (pinfunction "F_13") (pintype "input"))
      (node (ref "IC47") (pin "18") (pinfunction "I/O4_18") (pintype "bidirectional"))
      (node (ref "IC48") (pin "18") (pinfunction "I/O4_18") (pintype "bidirectional"))
      (node (ref "IC50") (pin "14") (pinfunction "B5_14") (pintype "bidirectional"))
    )
    (net (code "7") (name "BUSY") (class "Default")
      (node (ref "IC10") (pin "9") (pinfunction "Q_9") (pintype "output"))
      (node (ref "IC41") (pin "2") (pinfunction "I1_2") (pintype "input"))
      (node (ref "IC7") (pin "14") (pinfunction "A_14") (pintype "input"))
    )
    (net (code "8") (name "CA") (class "Default")
      (node (ref "IC37") (pin "12") (pinfunction "D3_12") (pintype "input"))
      (node (ref "IC37") (pin "7") (pinfunction "Q2_7") (pintype "output"))
      (node (ref "IC46") (pin "12") (pinfunction "I0_12") (pintype "input"))
    )
    (net (code "9") (name "CIE") (class "Default")
      (node (ref "IC35") (pin "6") (pinfunction "A3_6") (pintype "input"))
      (node (ref "IC38") (pin "1") (pinfunction "I0_1") (pintype "input"))
      (node (ref "INTENB") (pin "3") (pinfunction "QA_3") (pintype "output"))
      (node (ref "SV1") (pin "1") (pinfunction "1_1") (pintype "passive"))
    )
    (net (code "10") (name "DAR04") (class "Default")
      (node (ref "DAR4-7") (pin "7") (pinfunction "QD_7") (pintype "output"))
      (node (ref "IC17") (pin "14") (pinfunction "A_14") (pintype "input"))
      (node (ref "IC21") (pin "3") (pinfunction "B_3") (pintype "input"))
      (node (ref "IC31") (pin "17") (pinfunction "A4_17") (pintype "input"))
      (node (ref "SV2") (pin "8") (pinfunction "8_8") (pintype "passive"))
    )
    (net (code "11") (name "DAR05") (class "Default")
      (node (ref "DAR4-7") (pin "6") (pinfunction "QC_6") (pintype "output"))
      (node (ref "IC21") (pin "2") (pinfunction "A_2") (pintype "input"))
      (node (ref "IC27") (pin "1") (pinfunction "A18_1") (pintype "input"))
      (node (ref "IC31") (pin "15") (pinfunction "A3_15") (pintype "input"))
      (node (ref "IC33") (pin "1") (pinfunction "A18_1") (pintype "input"))
      (node (ref "IC47") (pin "1") (pinfunction "A18_1") (pintype "input"))
      (node (ref "IC48") (pin "1") (pinfunction "A18_1") (pintype "input"))
      (node (ref "SV2") (pin "10") (pinfunction "10_10") (pintype "passive"))
    )
    (net (code "12") (name "DAR06") (class "Default")
      (node (ref "DAR4-7") (pin "2") (pinfunction "QB_2") (pintype "output"))
      (node (ref "IC21") (pin "1") (pinfunction "G_1") (pintype "input"))
      (node (ref "IC27") (pin "30") (pinfunction "A17_30") (pintype "input"))
      (node (ref "IC31") (pin "13") (pinfunction "A2_13") (pintype "input"))
      (node (ref "IC33") (pin "30") (pinfunction "A17_30") (pintype "input"))
      (node (ref "IC47") (pin "30") (pinfunction "A17_30") (pintype "input"))
      (node (ref "IC48") (pin "30") (pinfunction "A17_30") (pintype "input"))
      (node (ref "SV2") (pin "12") (pinfunction "12_12") (pintype "passive"))
    )
    (net (code "13") (name "DAR07") (class "Default")
      (node (ref "DAR4-7") (pin "3") (pinfunction "QA_3") (pintype "output"))
      (node (ref "IC1") (pin "9") (pinfunction "C_9") (pintype "input"))
      (node (ref "IC2") (pin "9") (pinfunction "C_9") (pintype "input"))
      (node (ref "IC27") (pin "2") (pinfunction "A16_2") (pintype "input"))
      (node (ref "IC3") (pin "9") (pinfunction "C_9") (pintype "input"))
      (node (ref "IC31") (pin "11") (pinfunction "A1_11") (pintype "input"))
      (node (ref "IC33") (pin "2") (pinfunction "A16_2") (pintype "input"))
      (node (ref "IC4") (pin "9") (pinfunction "C_9") (pintype "input"))
      (node (ref "IC47") (pin "2") (pinfunction "A16_2") (pintype "input"))
      (node (ref "IC48") (pin "2") (pinfunction "A16_2") (pintype "input"))
      (node (ref "SV2") (pin "14") (pinfunction "14_14") (pintype "passive"))
    )
    (net (code "14") (name "DAR08") (class "Default")
      (node (ref "DAR8-11") (pin "7") (pinfunction "QD_7") (pintype "output"))
      (node (ref "IC1") (pin "10") (pinfunction "B_10") (pintype "input"))
      (node (ref "IC2") (pin "10") (pinfunction "B_10") (pintype "input"))
      (node (ref "IC24") (pin "17") (pinfunction "A4_17") (pintype "input"))
      (node (ref "IC27") (pin "31") (pinfunction "A15_31") (pintype "input"))
      (node (ref "IC3") (pin "10") (pinfunction "B_10") (pintype "input"))
      (node (ref "IC33") (pin "31") (pinfunction "A15_31") (pintype "input"))
      (node (ref "IC4") (pin "10") (pinfunction "B_10") (pintype "input"))
      (node (ref "IC47") (pin "31") (pinfunction "A15_31") (pintype "input"))
      (node (ref "IC48") (pin "31") (pinfunction "A15_31") (pintype "input"))
      (node (ref "SV2") (pin "16") (pinfunction "16_16") (pintype "passive"))
    )
    (net (code "15") (name "DAR09") (class "Default")
      (node (ref "DAR8-11") (pin "6") (pinfunction "QC_6") (pintype "output"))
      (node (ref "IC1") (pin "11") (pinfunction "A_11") (pintype "input"))
      (node (ref "IC2") (pin "11") (pinfunction "A_11") (pintype "input"))
      (node (ref "IC24") (pin "15") (pinfunction "A3_15") (pintype "input"))
      (node (ref "IC27") (pin "3") (pinfunction "A14_3") (pintype "input"))
      (node (ref "IC3") (pin "11") (pinfunction "A_11") (pintype "input"))
      (node (ref "IC33") (pin "3") (pinfunction "A14_3") (pintype "input"))
      (node (ref "IC4") (pin "11") (pinfunction "A_11") (pintype "input"))
      (node (ref "IC47") (pin "3") (pinfunction "A14_3") (pintype "input"))
      (node (ref "IC48") (pin "3") (pinfunction "A14_3") (pintype "input"))
      (node (ref "SV2") (pin "18") (pinfunction "18_18") (pintype "passive"))
    )
    (net (code "16") (name "DAR10") (class "Default")
      (node (ref "DAR8-11") (pin "2") (pinfunction "QB_2") (pintype "output"))
      (node (ref "IC24") (pin "13") (pinfunction "A2_13") (pintype "input"))
      (node (ref "IC27") (pin "28") (pinfunction "A13_28") (pintype "input"))
      (node (ref "IC33") (pin "28") (pinfunction "A13_28") (pintype "input"))
      (node (ref "IC47") (pin "28") (pinfunction "A13_28") (pintype "input"))
      (node (ref "IC48") (pin "28") (pinfunction "A13_28") (pintype "input"))
      (node (ref "SV2") (pin "20") (pinfunction "20_20") (pintype "passive"))
    )
    (net (code "17") (name "DAR11") (class "Default")
      (node (ref "DAR8-11") (pin "3") (pinfunction "QA_3") (pintype "output"))
      (node (ref "IC24") (pin "11") (pinfunction "A1_11") (pintype "input"))
      (node (ref "IC27") (pin "4") (pinfunction "A12_4") (pintype "input"))
      (node (ref "IC33") (pin "4") (pinfunction "A12_4") (pintype "input"))
      (node (ref "IC47") (pin "4") (pinfunction "A12_4") (pintype "input"))
      (node (ref "IC48") (pin "4") (pinfunction "A12_4") (pintype "input"))
      (node (ref "SV2") (pin "22") (pinfunction "22_22") (pintype "passive"))
    )
    (net (code "18") (name "DATA0") (class "Default")
      (node (ref "DMA0-3") (pin "9") (pinfunction "D_9") (pintype "input"))
      (node (ref "IC55") (pin "13") (pinfunction "2Y2_13") (pintype "tri_state"))
    )
    (net (code "19") (name "DATA1") (class "Default")
      (node (ref "DMA0-3") (pin "10") (pinfunction "C_10") (pintype "input"))
      (node (ref "IC55") (pin "11") (pinfunction "2Y1_11") (pintype "tri_state"))
    )
    (net (code "20") (name "DATA2") (class "Default")
      (node (ref "DMA0-3") (pin "1") (pinfunction "B_1") (pintype "input"))
      (node (ref "IC55") (pin "9") (pinfunction "1Y4_9") (pintype "tri_state"))
    )
    (net (code "21") (name "DATA3") (class "Default")
      (node (ref "DMA0-3") (pin "15") (pinfunction "A_15") (pintype "input"))
      (node (ref "IC55") (pin "7") (pinfunction "1Y3_7") (pintype "tri_state"))
      (node (ref "INTENB") (pin "10") (pinfunction "C_10") (pintype "input"))
    )
    (net (code "22") (name "DATA4") (class "Default")
      (node (ref "DAR4-7") (pin "9") (pinfunction "D_9") (pintype "input"))
      (node (ref "DMA4-7") (pin "9") (pinfunction "D_9") (pintype "input"))
      (node (ref "IC55") (pin "5") (pinfunction "1Y2_5") (pintype "tri_state"))
      (node (ref "INTENB") (pin "1") (pinfunction "B_1") (pintype "input"))
    )
    (net (code "23") (name "DATA5") (class "Default")
      (node (ref "DAR4-7") (pin "10") (pinfunction "C_10") (pintype "input"))
      (node (ref "DMA4-7") (pin "10") (pinfunction "C_10") (pintype "input"))
      (node (ref "IC55") (pin "3") (pinfunction "1Y1_3") (pintype "tri_state"))
      (node (ref "INTENB") (pin "15") (pinfunction "A_15") (pintype "input"))
    )
    (net (code "24") (name "DATA6") (class "Default")
      (node (ref "DAR4-7") (pin "1") (pinfunction "B_1") (pintype "input"))
      (node (ref "DMA4-7") (pin "1") (pinfunction "B_1") (pintype "input"))
      (node (ref "FIELD") (pin "10") (pinfunction "C_10") (pintype "input"))
      (node (ref "IC54") (pin "13") (pinfunction "2Y2_13") (pintype "tri_state"))
    )
    (net (code "25") (name "DATA7") (class "Default")
      (node (ref "DAR4-7") (pin "15") (pinfunction "A_15") (pintype "input"))
      (node (ref "DMA4-7") (pin "15") (pinfunction "A_15") (pintype "input"))
      (node (ref "FIELD") (pin "1") (pinfunction "B_1") (pintype "input"))
      (node (ref "IC54") (pin "11") (pinfunction "2Y1_11") (pintype "tri_state"))
    )
    (net (code "26") (name "DATA8") (class "Default")
      (node (ref "DAR8-11") (pin "9") (pinfunction "D_9") (pintype "input"))
      (node (ref "DMA8-11") (pin "9") (pinfunction "D_9") (pintype "input"))
      (node (ref "FIELD") (pin "15") (pinfunction "A_15") (pintype "input"))
      (node (ref "IC54") (pin "9") (pinfunction "1Y4_9") (pintype "tri_state"))
    )
    (net (code "27") (name "DATA9") (class "Default")
      (node (ref "DAR8-11") (pin "10") (pinfunction "C_10") (pintype "input"))
      (node (ref "DMA8-11") (pin "10") (pinfunction "C_10") (pintype "input"))
      (node (ref "IC54") (pin "7") (pinfunction "1Y3_7") (pintype "tri_state"))
    )
    (net (code "28") (name "DATA10") (class "Default")
      (node (ref "DAR8-11") (pin "1") (pinfunction "B_1") (pintype "input"))
      (node (ref "DMA8-11") (pin "1") (pinfunction "B_1") (pintype "input"))
      (node (ref "IC54") (pin "5") (pinfunction "1Y2_5") (pintype "tri_state"))
    )
    (net (code "29") (name "DATA11") (class "Default")
      (node (ref "DAR8-11") (pin "15") (pinfunction "A_15") (pintype "input"))
      (node (ref "DMA8-11") (pin "15") (pinfunction "A_15") (pintype "input"))
      (node (ref "IC54") (pin "3") (pinfunction "1Y1_3") (pintype "tri_state"))
    )
    (net (code "30") (name "DCIM") (class "Default")
      (node (ref "FIELD") (pin "14") (pinfunction "CLR_14") (pintype "input"))
      (node (ref "IC16") (pin "13") (pinfunction "O_13") (pintype "output"))
      (node (ref "INTENB") (pin "14") (pinfunction "CLR_14") (pintype "input"))
    )
    (net (code "31") (name "DMA-IN") (class "Default")
      (node (ref "IC12") (pin "10") (pinfunction "O_10") (pintype "output"))
      (node (ref "IC13") (pin "3") (pinfunction "EI_3") (pintype "input"))
    )
    (net (code "32") (name "DMA00") (class "Default")
      (node (ref "DMA0-3") (pin "7") (pinfunction "QD_7") (pintype "output"))
      (node (ref "IC26") (pin "8") (pinfunction "A4_8") (pintype "input"))
      (node (ref "IC27") (pin "25") (pinfunction "A11_25") (pintype "input"))
      (node (ref "IC33") (pin "25") (pinfunction "A11_25") (pintype "input"))
      (node (ref "IC47") (pin "25") (pinfunction "A11_25") (pintype "input"))
      (node (ref "IC48") (pin "25") (pinfunction "A11_25") (pintype "input"))
      (node (ref "SV2") (pin "1") (pinfunction "1_1") (pintype "passive"))
      (node (ref "SV2") (pin "24") (pinfunction "24_24") (pintype "passive"))
    )
    (net (code "33") (name "DMA01") (class "Default")
      (node (ref "DMA0-3") (pin "6") (pinfunction "QC_6") (pintype "output"))
      (node (ref "IC26") (pin "6") (pinfunction "A3_6") (pintype "input"))
      (node (ref "IC27") (pin "23") (pinfunction "A10_23") (pintype "input"))
      (node (ref "IC33") (pin "23") (pinfunction "A10_23") (pintype "input"))
      (node (ref "IC47") (pin "23") (pinfunction "A10_23") (pintype "input"))
      (node (ref "IC48") (pin "23") (pinfunction "A10_23") (pintype "input"))
      (node (ref "SV2") (pin "3") (pinfunction "3_3") (pintype "passive"))
    )
    (net (code "34") (name "DMA02") (class "Default")
      (node (ref "DMA0-3") (pin "2") (pinfunction "QB_2") (pintype "output"))
      (node (ref "IC26") (pin "4") (pinfunction "A2_4") (pintype "input"))
      (node (ref "IC27") (pin "26") (pinfunction "A9_26") (pintype "input"))
      (node (ref "IC33") (pin "26") (pinfunction "A9_26") (pintype "input"))
      (node (ref "IC47") (pin "26") (pinfunction "A9_26") (pintype "input"))
      (node (ref "IC48") (pin "26") (pinfunction "A9_26") (pintype "input"))
      (node (ref "SV2") (pin "5") (pinfunction "5_5") (pintype "passive"))
    )
    (net (code "35") (name "DMA03") (class "Default")
      (node (ref "DMA0-3") (pin "3") (pinfunction "QA_3") (pintype "output"))
      (node (ref "IC26") (pin "2") (pinfunction "A1_2") (pintype "input"))
      (node (ref "IC27") (pin "27") (pinfunction "A8_27") (pintype "input"))
      (node (ref "IC33") (pin "27") (pinfunction "A8_27") (pintype "input"))
      (node (ref "IC47") (pin "27") (pinfunction "A8_27") (pintype "input"))
      (node (ref "IC48") (pin "27") (pinfunction "A8_27") (pintype "input"))
      (node (ref "SV2") (pin "7") (pinfunction "7_7") (pintype "passive"))
    )
    (net (code "36") (name "DMA04") (class "Default")
      (node (ref "DMA4-7") (pin "7") (pinfunction "QD_7") (pintype "output"))
      (node (ref "IC27") (pin "5") (pinfunction "A7_5") (pintype "input"))
      (node (ref "IC31") (pin "8") (pinfunction "A4_8") (pintype "input"))
      (node (ref "IC33") (pin "5") (pinfunction "A7_5") (pintype "input"))
      (node (ref "IC47") (pin "5") (pinfunction "A7_5") (pintype "input"))
      (node (ref "IC48") (pin "5") (pinfunction "A7_5") (pintype "input"))
      (node (ref "SV2") (pin "9") (pinfunction "9_9") (pintype "passive"))
    )
    (net (code "37") (name "DMA05") (class "Default")
      (node (ref "DMA4-7") (pin "6") (pinfunction "QC_6") (pintype "output"))
      (node (ref "IC27") (pin "6") (pinfunction "A6_6") (pintype "input"))
      (node (ref "IC31") (pin "6") (pinfunction "A3_6") (pintype "input"))
      (node (ref "IC33") (pin "6") (pinfunction "A6_6") (pintype "input"))
      (node (ref "IC47") (pin "6") (pinfunction "A6_6") (pintype "input"))
      (node (ref "IC48") (pin "6") (pinfunction "A6_6") (pintype "input"))
      (node (ref "SV2") (pin "11") (pinfunction "11_11") (pintype "passive"))
    )
    (net (code "38") (name "DMA06") (class "Default")
      (node (ref "DMA4-7") (pin "2") (pinfunction "QB_2") (pintype "output"))
      (node (ref "IC27") (pin "7") (pinfunction "A5_7") (pintype "input"))
      (node (ref "IC31") (pin "4") (pinfunction "A2_4") (pintype "input"))
      (node (ref "IC33") (pin "7") (pinfunction "A5_7") (pintype "input"))
      (node (ref "IC47") (pin "7") (pinfunction "A5_7") (pintype "input"))
      (node (ref "IC48") (pin "7") (pinfunction "A5_7") (pintype "input"))
      (node (ref "SV2") (pin "13") (pinfunction "13_13") (pintype "passive"))
    )
    (net (code "39") (name "DMA07") (class "Default")
      (node (ref "DMA4-7") (pin "3") (pinfunction "QA_3") (pintype "output"))
      (node (ref "IC27") (pin "8") (pinfunction "A4_8") (pintype "input"))
      (node (ref "IC31") (pin "2") (pinfunction "A1_2") (pintype "input"))
      (node (ref "IC33") (pin "8") (pinfunction "A4_8") (pintype "input"))
      (node (ref "IC47") (pin "8") (pinfunction "A4_8") (pintype "input"))
      (node (ref "IC48") (pin "8") (pinfunction "A4_8") (pintype "input"))
      (node (ref "SV2") (pin "15") (pinfunction "15_15") (pintype "passive"))
    )
    (net (code "40") (name "DMA08") (class "Default")
      (node (ref "DMA8-11") (pin "7") (pinfunction "QD_7") (pintype "output"))
      (node (ref "IC24") (pin "8") (pinfunction "A4_8") (pintype "input"))
      (node (ref "IC27") (pin "9") (pinfunction "A3_9") (pintype "input"))
      (node (ref "IC33") (pin "9") (pinfunction "A3_9") (pintype "input"))
      (node (ref "IC47") (pin "9") (pinfunction "A3_9") (pintype "input"))
      (node (ref "IC48") (pin "9") (pinfunction "A3_9") (pintype "input"))
      (node (ref "SV2") (pin "17") (pinfunction "17_17") (pintype "passive"))
    )
    (net (code "41") (name "DMA09") (class "Default")
      (node (ref "DMA8-11") (pin "6") (pinfunction "QC_6") (pintype "output"))
      (node (ref "IC24") (pin "6") (pinfunction "A3_6") (pintype "input"))
      (node (ref "IC27") (pin "10") (pinfunction "A2_10") (pintype "input"))
      (node (ref "IC33") (pin "10") (pinfunction "A2_10") (pintype "input"))
      (node (ref "IC47") (pin "10") (pinfunction "A2_10") (pintype "input"))
      (node (ref "IC48") (pin "10") (pinfunction "A2_10") (pintype "input"))
      (node (ref "SV2") (pin "19") (pinfunction "19_19") (pintype "passive"))
    )
    (net (code "42") (name "DMA10") (class "Default")
      (node (ref "DMA8-11") (pin "2") (pinfunction "QB_2") (pintype "output"))
      (node (ref "IC24") (pin "4") (pinfunction "A2_4") (pintype "input"))
      (node (ref "IC27") (pin "11") (pinfunction "A1_11") (pintype "input"))
      (node (ref "IC33") (pin "11") (pinfunction "A1_11") (pintype "input"))
      (node (ref "IC47") (pin "11") (pinfunction "A1_11") (pintype "input"))
      (node (ref "IC48") (pin "11") (pinfunction "A1_11") (pintype "input"))
      (node (ref "SV2") (pin "21") (pinfunction "21_21") (pintype "passive"))
    )
    (net (code "43") (name "DMA11") (class "Default")
      (node (ref "DMA8-11") (pin "3") (pinfunction "QA_3") (pintype "output"))
      (node (ref "IC24") (pin "2") (pinfunction "A1_2") (pintype "input"))
      (node (ref "IC27") (pin "12") (pinfunction "A0_12") (pintype "input"))
      (node (ref "IC33") (pin "12") (pinfunction "A0_12") (pintype "input"))
      (node (ref "IC47") (pin "12") (pinfunction "A0_12") (pintype "input"))
      (node (ref "IC48") (pin "12") (pinfunction "A0_12") (pintype "input"))
      (node (ref "SV2") (pin "23") (pinfunction "23_23") (pintype "passive"))
    )
    (net (code "44") (name "DONE") (class "Default")
      (node (ref "IC11") (pin "9") (pinfunction "Q_9") (pintype "output"))
      (node (ref "IC38") (pin "2") (pinfunction "I1_2") (pintype "input"))
      (node (ref "SV1") (pin "23") (pinfunction "23_23") (pintype "passive"))
    )
    (net (code "45") (name "DT") (class "Default")
      (node (ref "DMA8-11") (pin "5") (pinfunction "UP_5") (pintype "input"))
      (node (ref "IC37") (pin "10") (pinfunction "Q3_10") (pintype "output"))
    )
    (net (code "46") (name "EIE") (class "Default")
      (node (ref "IC35") (pin "11") (pinfunction "A1_11") (pintype "input"))
      (node (ref "IC38") (pin "9") (pinfunction "I0_9") (pintype "input"))
      (node (ref "INTENB") (pin "6") (pinfunction "QC_6") (pintype "output"))
      (node (ref "SV1") (pin "3") (pinfunction "3_3") (pintype "passive"))
    )
    (net (code "47") (name "ERROR") (class "Default")
      (node (ref "IC12") (pin "3") (pinfunction "I_3") (pintype "input"))
      (node (ref "IC38") (pin "10") (pinfunction "I1_10") (pintype "input"))
      (node (ref "IC5") (pin "8") (pinfunction "O_8") (pintype "output"))
      (node (ref "IC7") (pin "2") (pinfunction "A_2") (pintype "input"))
    )
    (net (code "48") (name "F.1") (class "Default")
      (node (ref "FIELD") (pin "3") (pinfunction "QA_3") (pintype "output"))
      (node (ref "IC30") (pin "17") (pinfunction "A4_17") (pintype "input"))
      (node (ref "IC30") (pin "2") (pinfunction "A1_2") (pintype "input"))
      (node (ref "SV2") (pin "6") (pinfunction "6_6") (pintype "passive"))
    )
    (net (code "49") (name "F.2") (class "Default")
      (node (ref "FIELD") (pin "2") (pinfunction "QB_2") (pintype "output"))
      (node (ref "IC30") (pin "4") (pinfunction "A2_4") (pintype "input"))
      (node (ref "IC35") (pin "2") (pinfunction "A1_2") (pintype "input"))
      (node (ref "SV2") (pin "4") (pinfunction "4_4") (pintype "passive"))
    )
    (net (code "50") (name "F.3") (class "Default")
      (node (ref "FIELD") (pin "6") (pinfunction "QC_6") (pintype "output"))
      (node (ref "IC30") (pin "6") (pinfunction "A3_6") (pintype "input"))
      (node (ref "IC35") (pin "4") (pinfunction "A2_4") (pintype "input"))
      (node (ref "SV2") (pin "2") (pinfunction "2_2") (pintype "passive"))
    )
    (net (code "51") (name "GND") (class "Default")
      (node (ref "C1") (pin "2") (pinfunction "2_2") (pintype "passive"))
      (node (ref "C10") (pin "2") (pinfunction "2_2") (pintype "passive"))
      (node (ref "C11") (pin "2") (pinfunction "2_2") (pintype "passive"))
      (node (ref "C12") (pin "2") (pinfunction "2_2") (pintype "passive"))
      (node (ref "C13") (pin "2") (pinfunction "2_2") (pintype "passive"))
      (node (ref "C14") (pin "2") (pinfunction "2_2") (pintype "passive"))
      (node (ref "C15") (pin "2") (pinfunction "2_2") (pintype "passive"))
      (node (ref "C16") (pin "2") (pinfunction "2_2") (pintype "passive"))
      (node (ref "C17") (pin "2") (pinfunction "2_2") (pintype "passive"))
      (node (ref "C18") (pin "2") (pinfunction "2_2") (pintype "passive"))
      (node (ref "C19") (pin "2") (pinfunction "2_2") (pintype "passive"))
      (node (ref "C2") (pin "2") (pinfunction "2_2") (pintype "passive"))
      (node (ref "C20") (pin "2") (pinfunction "2_2") (pintype "passive"))
      (node (ref "C21") (pin "2") (pinfunction "2_2") (pintype "passive"))
      (node (ref "C22") (pin "2") (pinfunction "2_2") (pintype "passive"))
      (node (ref "C23") (pin "2") (pinfunction "2_2") (pintype "passive"))
      (node (ref "C24") (pin "2") (pinfunction "2_2") (pintype "passive"))
      (node (ref "C25") (pin "2") (pinfunction "2_2") (pintype "passive"))
      (node (ref "C26") (pin "2") (pinfunction "2_2") (pintype "passive"))
      (node (ref "C27") (pin "2") (pinfunction "2_2") (pintype "passive"))
      (node (ref "C28") (pin "2") (pinfunction "2_2") (pintype "passive"))
      (node (ref "C29") (pin "2") (pinfunction "2_2") (pintype "passive"))
      (node (ref "C3") (pin "2") (pinfunction "2_2") (pintype "passive"))
      (node (ref "C30") (pin "2") (pinfunction "2_2") (pintype "passive"))
      (node (ref "C31") (pin "2") (pinfunction "2_2") (pintype "passive"))
      (node (ref "C32") (pin "2") (pinfunction "2_2") (pintype "passive"))
      (node (ref "C33") (pin "2") (pinfunction "2_2") (pintype "passive"))
      (node (ref "C34") (pin "2") (pinfunction "2_2") (pintype "passive"))
      (node (ref "C35") (pin "2") (pinfunction "2_2") (pintype "passive"))
      (node (ref "C36") (pin "2") (pinfunction "2_2") (pintype "passive"))
      (node (ref "C37") (pin "2") (pinfunction "2_2") (pintype "passive"))
      (node (ref "C38") (pin "2") (pinfunction "2_2") (pintype "passive"))
      (node (ref "C39") (pin "2") (pinfunction "2_2") (pintype "passive"))
      (node (ref "C4") (pin "2") (pinfunction "2_2") (pintype "passive"))
      (node (ref "C40") (pin "2") (pinfunction "2_2") (pintype "passive"))
      (node (ref "C41") (pin "2") (pinfunction "2_2") (pintype "passive"))
      (node (ref "C42") (pin "2") (pinfunction "2_2") (pintype "passive"))
      (node (ref "C43") (pin "2") (pinfunction "2_2") (pintype "passive"))
      (node (ref "C44") (pin "2") (pinfunction "2_2") (pintype "passive"))
      (node (ref "C45") (pin "-") (pinfunction "-_-") (pintype "passive"))
      (node (ref "C46") (pin "2") (pinfunction "2_2") (pintype "passive"))
      (node (ref "C47") (pin "2") (pinfunction "2_2") (pintype "passive"))
      (node (ref "C49") (pin "2") (pinfunction "2_2") (pintype "passive"))
      (node (ref "C5") (pin "2") (pinfunction "2_2") (pintype "passive"))
      (node (ref "C50") (pin "2") (pinfunction "2_2") (pintype "passive"))
      (node (ref "C6") (pin "2") (pinfunction "2_2") (pintype "passive"))
      (node (ref "C7") (pin "2") (pinfunction "2_2") (pintype "passive"))
      (node (ref "C8") (pin "2") (pinfunction "2_2") (pintype "passive"))
      (node (ref "C9") (pin "2") (pinfunction "2_2") (pintype "passive"))
      (node (ref "D10") (pin "12") (pinfunction "12_12") (pintype "passive"))
      (node (ref "D10") (pin "16") (pinfunction "16_16") (pintype "passive"))
      (node (ref "D10") (pin "3") (pinfunction "3_3") (pintype "passive"))
      (node (ref "D10") (pin "6") (pinfunction "6_6") (pintype "passive"))
      (node (ref "D11") (pin "12") (pinfunction "12_12") (pintype "passive"))
      (node (ref "D11") (pin "16") (pinfunction "16_16") (pintype "passive"))
      (node (ref "D11") (pin "3") (pinfunction "3_3") (pintype "passive"))
      (node (ref "D11") (pin "6") (pinfunction "6_6") (pintype "passive"))
      (node (ref "D12") (pin "12") (pinfunction "12_12") (pintype "passive"))
      (node (ref "D12") (pin "16") (pinfunction "16_16") (pintype "passive"))
      (node (ref "D12") (pin "3") (pinfunction "3_3") (pintype "passive"))
      (node (ref "D12") (pin "6") (pinfunction "6_6") (pintype "passive"))
      (node (ref "D13") (pin "12") (pinfunction "12_12") (pintype "passive"))
      (node (ref "D13") (pin "16") (pinfunction "16_16") (pintype "passive"))
      (node (ref "D13") (pin "3") (pinfunction "3_3") (pintype "passive"))
      (node (ref "D13") (pin "6") (pinfunction "6_6") (pintype "passive"))
      (node (ref "D14") (pin "12") (pinfunction "12_12") (pintype "passive"))
      (node (ref "D14") (pin "16") (pinfunction "16_16") (pintype "passive"))
      (node (ref "D14") (pin "3") (pinfunction "3_3") (pintype "passive"))
      (node (ref "D14") (pin "6") (pinfunction "6_6") (pintype "passive"))
      (node (ref "D7") (pin "12") (pinfunction "12_12") (pintype "passive"))
      (node (ref "D7") (pin "16") (pinfunction "16_16") (pintype "passive"))
      (node (ref "D7") (pin "3") (pinfunction "3_3") (pintype "passive"))
      (node (ref "D7") (pin "6") (pinfunction "6_6") (pintype "passive"))
      (node (ref "D8") (pin "12") (pinfunction "12_12") (pintype "passive"))
      (node (ref "D8") (pin "16") (pinfunction "16_16") (pintype "passive"))
      (node (ref "D8") (pin "3") (pinfunction "3_3") (pintype "passive"))
      (node (ref "D8") (pin "6") (pinfunction "6_6") (pintype "passive"))
      (node (ref "D9") (pin "12") (pinfunction "12_12") (pintype "passive"))
      (node (ref "D9") (pin "16") (pinfunction "16_16") (pintype "passive"))
      (node (ref "D9") (pin "3") (pinfunction "3_3") (pintype "passive"))
      (node (ref "D9") (pin "6") (pinfunction "6_6") (pintype "passive"))
      (node (ref "DAR4-7") (pin "4") (pinfunction "DN_4") (pintype "input"))
      (node (ref "DAR8-11") (pin "4") (pinfunction "DN_4") (pintype "input"))
      (node (ref "DMA0-3") (pin "4") (pinfunction "DN_4") (pintype "input"))
      (node (ref "DMA4-7") (pin "4") (pinfunction "DN_4") (pintype "input"))
      (node (ref "DMA8-11") (pin "4") (pinfunction "DN_4") (pintype "input"))
      (node (ref "FIELD") (pin "4") (pinfunction "DN_4") (pintype "input"))
      (node (ref "FIELD") (pin "5") (pinfunction "UP_5") (pintype "input"))
      (node (ref "FIELD") (pin "9") (pinfunction "D_9") (pintype "input"))
      (node (ref "IC1") (pin "7") (pinfunction "G_7") (pintype "input"))
      (node (ref "IC10") (pin "12") (pinfunction "D_12") (pintype "input"))
      (node (ref "IC10") (pin "2") (pinfunction "D_2") (pintype "input"))
      (node (ref "IC13") (pin "1") (pinfunction "G_1") (pintype "input"))
      (node (ref "IC13") (pin "2") (pinfunction "H_2") (pintype "input"))
      (node (ref "IC13") (pin "4") (pinfunction "OI_4") (pintype "input"))
      (node (ref "IC14") (pin "1") (pinfunction "G_1") (pintype "input"))
      (node (ref "IC14") (pin "13") (pinfunction "F_13") (pintype "input"))
      (node (ref "IC14") (pin "2") (pinfunction "H_2") (pintype "input"))
      (node (ref "IC14") (pin "4") (pinfunction "OI_4") (pintype "input"))
      (node (ref "IC15") (pin "4") (pinfunction "OI_4") (pintype "input"))
      (node (ref "IC17") (pin "1") (pinfunction "G_1") (pintype "input"))
      (node (ref "IC17") (pin "13") (pinfunction "B_13") (pintype "input"))
      (node (ref "IC17") (pin "15") (pinfunction "G_15") (pintype "input"))
      (node (ref "IC19") (pin "12") (pinfunction "O_12") (pintype "open_collector"))
      (node (ref "IC2") (pin "7") (pinfunction "G_7") (pintype "input"))
      (node (ref "IC26") (pin "11") (pinfunction "A1_11") (pintype "input"))
      (node (ref "IC26") (pin "13") (pinfunction "A2_13") (pintype "input"))
      (node (ref "IC26") (pin "15") (pinfunction "A3_15") (pintype "input"))
      (node (ref "IC26") (pin "17") (pinfunction "A4_17") (pintype "input"))
      (node (ref "IC27") (pin "16") (pinfunction "VSS_16") (pintype "power_in"))
      (node (ref "IC28") (pin "5") (pinfunction "A4_5") (pintype "bidirectional"))
      (node (ref "IC28") (pin "7") (pinfunction "A6_7") (pintype "bidirectional"))
      (node (ref "IC28") (pin "8") (pinfunction "A7_8") (pintype "bidirectional"))
      (node (ref "IC28") (pin "9") (pinfunction "A8_9") (pintype "bidirectional"))
      (node (ref "IC3") (pin "7") (pinfunction "G_7") (pintype "input"))
      (node (ref "IC30") (pin "1") (pinfunction "G_1") (pintype "input"))
      (node (ref "IC30") (pin "8") (pinfunction "A4_8") (pintype "input"))
      (node (ref "IC33") (pin "16") (pinfunction "VSS_16") (pintype "power_in"))
      (node (ref "IC34") (pin "2") (pinfunction "A1_2") (pintype "bidirectional"))
      (node (ref "IC34") (pin "3") (pinfunction "A2_3") (pintype "bidirectional"))
      (node (ref "IC34") (pin "4") (pinfunction "A3_4") (pintype "bidirectional"))
      (node (ref "IC34") (pin "5") (pinfunction "A4_5") (pintype "bidirectional"))
      (node (ref "IC36") (pin "5") (pinfunction "G2B_5") (pintype "input"))
      (node (ref "IC38") (pin "12") (pinfunction "I0_12") (pintype "input"))
      (node (ref "IC38") (pin "13") (pinfunction "I1_13") (pintype "input"))
      (node (ref "IC4") (pin "7") (pinfunction "G_7") (pintype "input"))
      (node (ref "IC47") (pin "16") (pinfunction "VSS_16") (pintype "power_in"))
      (node (ref "IC48") (pin "16") (pinfunction "VSS_16") (pintype "power_in"))
      (node (ref "IC51") (pin "4") (pinfunction "G2A_4") (pintype "input"))
      (node (ref "IC51") (pin "5") (pinfunction "G2B_5") (pintype "input"))
      (node (ref "IC52") (pin "8") (pinfunction "I0_8") (pintype "input"))
      (node (ref "IC52") (pin "9") (pinfunction "I1_9") (pintype "input"))
      (node (ref "IC53") (pin "2") (pinfunction "D2_2") (pintype "input"))
      (node (ref "IC53") (pin "3") (pinfunction "D1_3") (pintype "input"))
      (node (ref "IC53") (pin "7") (pinfunction "G_7") (pintype "input"))
      (node (ref "IC54") (pin "1") (pinfunction "1G_1") (pintype "input"))
      (node (ref "IC54") (pin "15") (pinfunction "2G_15") (pintype "input"))
      (node (ref "IC55") (pin "1") (pinfunction "1G_1") (pintype "input"))
      (node (ref "IC55") (pin "15") (pinfunction "2G_15") (pintype "input"))
      (node (ref "IC6") (pin "15") (pinfunction "G_15") (pintype "input"))
      (node (ref "IC7") (pin "1") (pinfunction "G_1") (pintype "input"))
      (node (ref "IC7") (pin "15") (pinfunction "G_15") (pintype "input"))
      (node (ref "IC8") (pin "7") (pinfunction "GND_7") (pintype "power_in"))
      (node (ref "IC9") (pin "12") (pinfunction "D_12") (pintype "input"))
      (node (ref "IC9") (pin "2") (pinfunction "D_2") (pintype "input"))
      (node (ref "INTENB") (pin "4") (pinfunction "DN_4") (pintype "input"))
      (node (ref "INTENB") (pin "5") (pinfunction "UP_5") (pintype "input"))
      (node (ref "INTENB") (pin "9") (pinfunction "D_9") (pintype "input"))
      (node (ref "SV1") (pin "17") (pinfunction "17_17") (pintype "passive"))
      (node (ref "SV2") (pin "25") (pinfunction "25_25") (pintype "passive"))
      (node (ref "SV2") (pin "26") (pinfunction "26_26") (pintype "passive"))
      (node (ref "U$19") (pin "AC1") (pinfunction "1_AC1") (pintype "bidirectional"))
      (node (ref "U$19") (pin "AC2") (pinfunction "1_AC2") (pintype "bidirectional"))
      (node (ref "U$19") (pin "AF1") (pinfunction "1_AF1") (pintype "bidirectional"))
      (node (ref "U$19") (pin "AF2") (pinfunction "1_AF2") (pintype "bidirectional"))
      (node (ref "U$19") (pin "AN1") (pinfunction "1_AN1") (pintype "bidirectional"))
      (node (ref "U$19") (pin "AN2") (pinfunction "1_AN2") (pintype "bidirectional"))
      (node (ref "U$19") (pin "AT1") (pinfunction "1_AT1") (pintype "bidirectional"))
      (node (ref "U$19") (pin "AT2") (pinfunction "1_AT2") (pintype "bidirectional"))
      (node (ref "U$19") (pin "BC1") (pinfunction "1_BC1") (pintype "bidirectional"))
      (node (ref "U$19") (pin "BC2") (pinfunction "1_BC2") (pintype "bidirectional"))
      (node (ref "U$19") (pin "BF1") (pinfunction "1_BF1") (pintype "bidirectional"))
      (node (ref "U$19") (pin "BF2") (pinfunction "1_BF2") (pintype "bidirectional"))
      (node (ref "U$19") (pin "BN1") (pinfunction "1_BN1") (pintype "bidirectional"))
      (node (ref "U$19") (pin "BN2") (pinfunction "1_BN2") (pintype "bidirectional"))
      (node (ref "U$19") (pin "BT1") (pinfunction "1_BT1") (pintype "bidirectional"))
      (node (ref "U$19") (pin "BT2") (pinfunction "1_BT2") (pintype "bidirectional"))
      (node (ref "U$19") (pin "CC1") (pinfunction "1_CC1") (pintype "bidirectional"))
      (node (ref "U$19") (pin "CC2") (pinfunction "1_CC2") (pintype "bidirectional"))
      (node (ref "U$19") (pin "CF1") (pinfunction "1_CF1") (pintype "bidirectional"))
      (node (ref "U$19") (pin "CF2") (pinfunction "1_CF2") (pintype "bidirectional"))
      (node (ref "U$19") (pin "CN1") (pinfunction "1_CN1") (pintype "bidirectional"))
      (node (ref "U$19") (pin "CN2") (pinfunction "1_CN2") (pintype "bidirectional"))
      (node (ref "U$19") (pin "CT1") (pinfunction "1_CT1") (pintype "bidirectional"))
      (node (ref "U$19") (pin "CT2") (pinfunction "1_CT2") (pintype "bidirectional"))
      (node (ref "U$19") (pin "DC1") (pinfunction "1_DC1") (pintype "bidirectional"))
      (node (ref "U$19") (pin "DC2") (pinfunction "1_DC2") (pintype "bidirectional"))
      (node (ref "U$19") (pin "DF1") (pinfunction "1_DF1") (pintype "bidirectional"))
      (node (ref "U$19") (pin "DF2") (pinfunction "1_DF2") (pintype "bidirectional"))
      (node (ref "U$19") (pin "DN1") (pinfunction "1_DN1") (pintype "bidirectional"))
      (node (ref "U$19") (pin "DN2") (pinfunction "1_DN2") (pintype "bidirectional"))
      (node (ref "U$19") (pin "DT1") (pinfunction "1_DT1") (pintype "bidirectional"))
      (node (ref "U$19") (pin "DT2") (pinfunction "1_DT2") (pintype "bidirectional"))
    )
    (net (code "52") (name "GO") (class "Default")
      (node (ref "IC16") (pin "1") (pinfunction "O_1") (pintype "output"))
      (node (ref "IC37") (pin "4") (pinfunction "D1_4") (pintype "input"))
      (node (ref "IC46") (pin "4") (pinfunction "I0_4") (pintype "input"))
      (node (ref "IC46") (pin "5") (pinfunction "I1_5") (pintype "input"))
    )
    (net (code "53") (name "IDLE") (class "Default")
      (node (ref "IC37") (pin "14") (pinfunction "~{Q4}_14") (pintype "output"))
      (node (ref "IC46") (pin "2") (pinfunction "I1_2") (pintype "input"))
    )
    (net (code "54") (name "INHIBIT") (class "Default")
      (node (ref "D10") (pin "13") (pinfunction "13_13") (pintype "passive"))
      (node (ref "U$19") (pin "AP2") (pinfunction "1_AP2") (pintype "bidirectional"))
    )
    (net (code "55") (name "INITIALIZE") (class "Default")
      (node (ref "D11") (pin "14") (pinfunction "14_14") (pintype "passive"))
      (node (ref "IC12") (pin "13") (pinfunction "I_13") (pintype "input"))
      (node (ref "U$19") (pin "CR1") (pinfunction "1_CR1") (pintype "bidirectional"))
    )
    (net (code "56") (name "INT_IN_PROG") (class "Default")
      (node (ref "D8") (pin "13") (pinfunction "13_13") (pintype "passive"))
      (node (ref "U$19") (pin "BP2") (pinfunction "1_BP2") (pintype "bidirectional"))
    )
    (net (code "57") (name "INT_STROBE") (class "Default")
      (node (ref "D8") (pin "4") (pinfunction "4_4") (pintype "passive"))
      (node (ref "IC41") (pin "1") (pinfunction "I0_1") (pintype "input"))
      (node (ref "U$19") (pin "BD2") (pinfunction "1_BD2") (pintype "bidirectional"))
    )
    (net (code "58") (name "MY_DB") (class "Default")
      (node (ref "IC37") (pin "9") (pinfunction "CLK_9") (pintype "input"))
      (node (ref "IC40") (pin "12") (pinfunction "D_12") (pintype "input"))
      (node (ref "IC40") (pin "5") (pinfunction "Q_5") (pintype "output"))
      (node (ref "IC41") (pin "9") (pinfunction "I0_9") (pintype "input"))
    )
    (net (code "59") (name "Net-(60XX-P)") (class "Default")
      (node (ref "60XX") (pin "1") (pinfunction "P_1") (pintype "passive"))
      (node (ref "IC36") (pin "7") (pinfunction "Y7_7") (pintype "output"))
    )
    (net (code "60") (name "Net-(61XX-P)") (class "Default")
      (node (ref "61XX") (pin "1") (pinfunction "P_1") (pintype "passive"))
      (node (ref "IC36") (pin "9") (pinfunction "Y6_9") (pintype "output"))
    )
    (net (code "61") (name "Net-(62XX-P)") (class "Default")
      (node (ref "62XX") (pin "1") (pinfunction "P_1") (pintype "passive"))
      (node (ref "IC36") (pin "10") (pinfunction "Y5_10") (pintype "output"))
    )
    (net (code "62") (name "Net-(63XX-P)") (class "Default")
      (node (ref "63XX") (pin "1") (pinfunction "P_1") (pintype "passive"))
      (node (ref "IC36") (pin "11") (pinfunction "Y4_11") (pintype "output"))
    )
    (net (code "63") (name "Net-(64XX-P)") (class "Default")
      (node (ref "64XX") (pin "1") (pinfunction "P_1") (pintype "passive"))
      (node (ref "IC36") (pin "12") (pinfunction "Y3_12") (pintype "output"))
    )
    (net (code "64") (name "Net-(65XX-P)") (class "Default")
      (node (ref "65XX") (pin "1") (pinfunction "P_1") (pintype "passive"))
      (node (ref "IC36") (pin "13") (pinfunction "Y2_13") (pintype "output"))
    )
    (net (code "65") (name "Net-(66XX-P)") (class "Default")
      (node (ref "66XX") (pin "1") (pinfunction "P_1") (pintype "passive"))
      (node (ref "IC36") (pin "14") (pinfunction "Y1_14") (pintype "output"))
    )
    (net (code "66") (name "Net-(67XX-P)") (class "Default")
      (node (ref "67XX") (pin "1") (pinfunction "P_1") (pintype "passive"))
      (node (ref "IC36") (pin "15") (pinfunction "Y0_15") (pintype "output"))
    )
    (net (code "67") (name "Net-(DAR4-7A-CLR)") (class "Default")
      (node (ref "DAR4-7") (pin "14") (pinfunction "CLR_14") (pintype "input"))
      (node (ref "DAR8-11") (pin "14") (pinfunction "CLR_14") (pintype "input"))
      (node (ref "IC18") (pin "8") (pinfunction "O_8") (pintype "output"))
    )
    (net (code "68") (name "Net-(DAR4-7A-UP)") (class "Default")
      (node (ref "DAR4-7") (pin "5") (pinfunction "UP_5") (pintype "input"))
      (node (ref "DAR8-11") (pin "12") (pinfunction "CO_12") (pintype "output"))
    )
    (net (code "69") (name "Net-(DAR8-11A-UP)") (class "Default")
      (node (ref "DAR8-11") (pin "5") (pinfunction "UP_5") (pintype "input"))
      (node (ref "DMA0-3") (pin "12") (pinfunction "CO_12") (pintype "output"))
    )
    (net (code "70") (name "Net-(DMA0-3A-CLR)") (class "Default")
      (node (ref "DMA0-3") (pin "14") (pinfunction "CLR_14") (pintype "input"))
      (node (ref "DMA4-7") (pin "14") (pinfunction "CLR_14") (pintype "input"))
      (node (ref "DMA8-11") (pin "14") (pinfunction "CLR_14") (pintype "input"))
      (node (ref "IC18") (pin "11") (pinfunction "O_11") (pintype "output"))
    )
    (net (code "71") (name "Net-(DMA0-3A-UP)") (class "Default")
      (node (ref "DMA0-3") (pin "5") (pinfunction "UP_5") (pintype "input"))
      (node (ref "DMA4-7") (pin "12") (pinfunction "CO_12") (pintype "output"))
    )
    (net (code "72") (name "Net-(DMA4-7A-UP)") (class "Default")
      (node (ref "DMA4-7") (pin "5") (pinfunction "UP_5") (pintype "input"))
      (node (ref "DMA8-11") (pin "12") (pinfunction "CO_12") (pintype "output"))
    )
    (net (code "73") (name "Net-(IC1A-D0)") (class "Default")
      (node (ref "IC1") (pin "4") (pinfunction "D0_4") (pintype "input"))
      (node (ref "SW1") (pin "16") (pinfunction "16_16") (pintype "passive"))
    )
    (net (code "74") (name "Net-(IC1A-D1)") (class "Default")
      (node (ref "IC1") (pin "3") (pinfunction "D1_3") (pintype "input"))
      (node (ref "SW1") (pin "15") (pinfunction "15_15") (pintype "passive"))
    )
    (net (code "75") (name "Net-(IC1A-D2)") (class "Default")
      (node (ref "IC1") (pin "2") (pinfunction "D2_2") (pintype "input"))
      (node (ref "SW1") (pin "14") (pinfunction "14_14") (pintype "passive"))
    )
    (net (code "76") (name "Net-(IC1A-D3)") (class "Default")
      (node (ref "IC1") (pin "1") (pinfunction "D3_1") (pintype "input"))
      (node (ref "SW1") (pin "13") (pinfunction "13_13") (pintype "passive"))
    )
    (net (code "77") (name "Net-(IC1A-D4)") (class "Default")
      (node (ref "IC1") (pin "15") (pinfunction "D4_15") (pintype "input"))
      (node (ref "SW1") (pin "12") (pinfunction "12_12") (pintype "passive"))
    )
    (net (code "78") (name "Net-(IC1A-D5)") (class "Default")
      (node (ref "IC1") (pin "14") (pinfunction "D5_14") (pintype "input"))
      (node (ref "SW1") (pin "11") (pinfunction "11_11") (pintype "passive"))
    )
    (net (code "79") (name "Net-(IC1A-D6)") (class "Default")
      (node (ref "IC1") (pin "13") (pinfunction "D6_13") (pintype "input"))
      (node (ref "SW1") (pin "10") (pinfunction "10_10") (pintype "passive"))
    )
    (net (code "80") (name "Net-(IC1A-D7)") (class "Default")
      (node (ref "IC1") (pin "12") (pinfunction "D7_12") (pintype "input"))
      (node (ref "SW1") (pin "9") (pinfunction "9_9") (pintype "passive"))
    )
    (net (code "81") (name "Net-(IC1A-Y)") (class "Default")
      (node (ref "IC1") (pin "5") (pinfunction "Y_5") (pintype "output"))
      (node (ref "IC5") (pin "1") (pinfunction "I0_1") (pintype "input"))
    )
    (net (code "82") (name "Net-(IC2A-D0)") (class "Default")
      (node (ref "IC2") (pin "4") (pinfunction "D0_4") (pintype "input"))
      (node (ref "SW2") (pin "16") (pinfunction "16_16") (pintype "passive"))
    )
    (net (code "83") (name "Net-(IC2A-D1)") (class "Default")
      (node (ref "IC2") (pin "3") (pinfunction "D1_3") (pintype "input"))
      (node (ref "SW2") (pin "15") (pinfunction "15_15") (pintype "passive"))
    )
    (net (code "84") (name "Net-(IC2A-D2)") (class "Default")
      (node (ref "IC2") (pin "2") (pinfunction "D2_2") (pintype "input"))
      (node (ref "SW2") (pin "14") (pinfunction "14_14") (pintype "passive"))
    )
    (net (code "85") (name "Net-(IC2A-D3)") (class "Default")
      (node (ref "IC2") (pin "1") (pinfunction "D3_1") (pintype "input"))
      (node (ref "SW2") (pin "13") (pinfunction "13_13") (pintype "passive"))
    )
    (net (code "86") (name "Net-(IC2A-D4)") (class "Default")
      (node (ref "IC2") (pin "15") (pinfunction "D4_15") (pintype "input"))
      (node (ref "SW2") (pin "12") (pinfunction "12_12") (pintype "passive"))
    )
    (net (code "87") (name "Net-(IC2A-D5)") (class "Default")
      (node (ref "IC2") (pin "14") (pinfunction "D5_14") (pintype "input"))
      (node (ref "SW2") (pin "11") (pinfunction "11_11") (pintype "passive"))
    )
    (net (code "88") (name "Net-(IC2A-D6)") (class "Default")
      (node (ref "IC2") (pin "13") (pinfunction "D6_13") (pintype "input"))
      (node (ref "SW2") (pin "10") (pinfunction "10_10") (pintype "passive"))
    )
    (net (code "89") (name "Net-(IC2A-D7)") (class "Default")
      (node (ref "IC2") (pin "12") (pinfunction "D7_12") (pintype "input"))
      (node (ref "SW2") (pin "9") (pinfunction "9_9") (pintype "passive"))
    )
    (net (code "90") (name "Net-(IC2A-Y)") (class "Default")
      (node (ref "IC2") (pin "5") (pinfunction "Y_5") (pintype "output"))
      (node (ref "IC5") (pin "2") (pinfunction "I1_2") (pintype "input"))
    )
    (net (code "91") (name "Net-(IC3A-D0)") (class "Default")
      (node (ref "IC3") (pin "4") (pinfunction "D0_4") (pintype "input"))
      (node (ref "SW3") (pin "16") (pinfunction "16_16") (pintype "passive"))
    )
    (net (code "92") (name "Net-(IC3A-D1)") (class "Default")
      (node (ref "IC3") (pin "3") (pinfunction "D1_3") (pintype "input"))
      (node (ref "SW3") (pin "15") (pinfunction "15_15") (pintype "passive"))
    )
    (net (code "93") (name "Net-(IC3A-D2)") (class "Default")
      (node (ref "IC3") (pin "2") (pinfunction "D2_2") (pintype "input"))
      (node (ref "SW3") (pin "14") (pinfunction "14_14") (pintype "passive"))
    )
    (net (code "94") (name "Net-(IC3A-D3)") (class "Default")
      (node (ref "IC3") (pin "1") (pinfunction "D3_1") (pintype "input"))
      (node (ref "SW3") (pin "13") (pinfunction "13_13") (pintype "passive"))
    )
    (net (code "95") (name "Net-(IC3A-D4)") (class "Default")
      (node (ref "IC3") (pin "15") (pinfunction "D4_15") (pintype "input"))
      (node (ref "SW3") (pin "12") (pinfunction "12_12") (pintype "passive"))
    )
    (net (code "96") (name "Net-(IC3A-D5)") (class "Default")
      (node (ref "IC3") (pin "14") (pinfunction "D5_14") (pintype "input"))
      (node (ref "SW3") (pin "11") (pinfunction "11_11") (pintype "passive"))
    )
    (net (code "97") (name "Net-(IC3A-D6)") (class "Default")
      (node (ref "IC3") (pin "13") (pinfunction "D6_13") (pintype "input"))
      (node (ref "SW3") (pin "10") (pinfunction "10_10") (pintype "passive"))
    )
    (net (code "98") (name "Net-(IC3A-D7)") (class "Default")
      (node (ref "IC3") (pin "12") (pinfunction "D7_12") (pintype "input"))
      (node (ref "SW3") (pin "9") (pinfunction "9_9") (pintype "passive"))
    )
    (net (code "99") (name "Net-(IC3A-Y)") (class "Default")
      (node (ref "IC3") (pin "5") (pinfunction "Y_5") (pintype "output"))
      (node (ref "IC5") (pin "4") (pinfunction "I2_4") (pintype "input"))
    )
    (net (code "100") (name "Net-(IC4A-D0)") (class "Default")
      (node (ref "IC4") (pin "4") (pinfunction "D0_4") (pintype "input"))
      (node (ref "SW4") (pin "16") (pinfunction "16_16") (pintype "passive"))
    )
    (net (code "101") (name "Net-(IC4A-D1)") (class "Default")
      (node (ref "IC4") (pin "3") (pinfunction "D1_3") (pintype "input"))
      (node (ref "SW4") (pin "15") (pinfunction "15_15") (pintype "passive"))
    )
    (net (code "102") (name "Net-(IC4A-D2)") (class "Default")
      (node (ref "IC4") (pin "2") (pinfunction "D2_2") (pintype "input"))
      (node (ref "SW4") (pin "14") (pinfunction "14_14") (pintype "passive"))
    )
    (net (code "103") (name "Net-(IC4A-D3)") (class "Default")
      (node (ref "IC4") (pin "1") (pinfunction "D3_1") (pintype "input"))
      (node (ref "SW4") (pin "13") (pinfunction "13_13") (pintype "passive"))
    )
    (net (code "104") (name "Net-(IC4A-D4)") (class "Default")
      (node (ref "IC4") (pin "15") (pinfunction "D4_15") (pintype "input"))
      (node (ref "SW4") (pin "12") (pinfunction "12_12") (pintype "passive"))
    )
    (net (code "105") (name "Net-(IC4A-D5)") (class "Default")
      (node (ref "IC4") (pin "14") (pinfunction "D5_14") (pintype "input"))
      (node (ref "SW4") (pin "11") (pinfunction "11_11") (pintype "passive"))
    )
    (net (code "106") (name "Net-(IC4A-D6)") (class "Default")
      (node (ref "IC4") (pin "13") (pinfunction "D6_13") (pintype "input"))
      (node (ref "SW4") (pin "10") (pinfunction "10_10") (pintype "passive"))
    )
    (net (code "107") (name "Net-(IC4A-D7)") (class "Default")
      (node (ref "IC4") (pin "12") (pinfunction "D7_12") (pintype "input"))
      (node (ref "SW4") (pin "9") (pinfunction "9_9") (pintype "passive"))
    )
    (net (code "108") (name "Net-(IC4A-Y)") (class "Default")
      (node (ref "IC4") (pin "5") (pinfunction "Y_5") (pintype "output"))
      (node (ref "IC5") (pin "5") (pinfunction "I3_5") (pintype "input"))
    )
    (net (code "109") (name "Net-(IC8A-CV)") (class "Default")
      (node (ref "C48") (pin "2") (pinfunction "2_2") (pintype "passive"))
      (node (ref "IC8") (pin "3") (pinfunction "CV_3") (pintype "input"))
    )
    (net (code "110") (name "Net-(IC8A-DIS)") (class "Default")
      (node (ref "IC8") (pin "1") (pinfunction "DIS_1") (pintype "input"))
      (node (ref "RA") (pin "2") (pinfunction "2_2") (pintype "passive"))
      (node (ref "RB") (pin "1") (pinfunction "1_1") (pintype "passive"))
    )
    (net (code "111") (name "Net-(IC8A-THR)") (class "Default")
      (node (ref "C47") (pin "1") (pinfunction "1_1") (pintype "passive"))
      (node (ref "IC8") (pin "2") (pinfunction "THR_2") (pintype "input"))
      (node (ref "IC8") (pin "6") (pinfunction "TR_6") (pintype "input"))
      (node (ref "RB") (pin "2") (pinfunction "2_2") (pintype "passive"))
    )
    (net (code "112") (name "Net-(IC8B-CV)") (class "Default")
      (node (ref "C49") (pin "1") (pinfunction "1_1") (pintype "passive"))
      (node (ref "IC8") (pin "11") (pinfunction "CV_11") (pintype "input"))
    )
    (net (code "113") (name "Net-(IC8B-DIS)") (class "Default")
      (node (ref "IC8") (pin "13") (pinfunction "DIS_13") (pintype "input"))
      (node (ref "RB2") (pin "1") (pinfunction "1_1") (pintype "passive"))
    )
    (net (code "114") (name "Net-(IC8B-R)") (class "Default")
      (node (ref "IC8") (pin "10") (pinfunction "R_10") (pintype "input"))
      (node (ref "RA2") (pin "1") (pinfunction "1_1") (pintype "passive"))
    )
    (net (code "115") (name "Net-(IC8B-THR)") (class "Default")
      (node (ref "C50") (pin "1") (pinfunction "1_1") (pintype "passive"))
      (node (ref "IC8") (pin "12") (pinfunction "THR_12") (pintype "input"))
      (node (ref "IC8") (pin "8") (pinfunction "TR_8") (pintype "input"))
      (node (ref "RA2") (pin "2") (pinfunction "2_2") (pintype "passive"))
      (node (ref "RB2") (pin "2") (pinfunction "2_2") (pintype "passive"))
    )
    (net (code "116") (name "Net-(IC10B-CLK)") (class "Default")
      (node (ref "IC10") (pin "11") (pinfunction "CLK_11") (pintype "input"))
      (node (ref "IC18") (pin "6") (pinfunction "O_6") (pintype "output"))
    )
    (net (code "117") (name "Net-(IC13A-A)") (class "Default")
      (node (ref "IC13") (pin "8") (pinfunction "A_8") (pintype "input"))
      (node (ref "IC14") (pin "8") (pinfunction "A_8") (pintype "input"))
      (node (ref "IC15") (pin "6") (pinfunction "ODD_6") (pintype "output"))
    )
    (net (code "118") (name "Net-(IC16B-I0)") (class "Default")
      (node (ref "IC16") (pin "11") (pinfunction "I0_11") (pintype "input"))
      (node (ref "IC16") (pin "5") (pinfunction "I0_5") (pintype "input"))
      (node (ref "IC16") (pin "8") (pinfunction "I0_8") (pintype "input"))
      (node (ref "IC41") (pin "11") (pinfunction "O_11") (pintype "output"))
    )
    (net (code "119") (name "Net-(IC17A-Y2)") (class "Default")
      (node (ref "IC17") (pin "6") (pinfunction "Y2_6") (pintype "output"))
      (node (ref "IC22") (pin "11") (pinfunction "I_11") (pintype "input"))
    )
    (net (code "120") (name "Net-(IC17B-Y0)") (class "Default")
      (node (ref "IC17") (pin "12") (pinfunction "Y0_12") (pintype "output"))
      (node (ref "Q1") (pin "3") (pinfunction "E_3") (pintype "passive"))
    )
    (net (code "121") (name "Net-(IC17B-Y1)") (class "Default")
      (node (ref "IC17") (pin "11") (pinfunction "Y1_11") (pintype "output"))
      (node (ref "Q2") (pin "3") (pinfunction "E_3") (pintype "passive"))
    )
    (net (code "122") (name "Net-(IC19A-I)") (class "Default")
      (node (ref "IC19") (pin "1") (pinfunction "I_1") (pintype "input"))
      (node (ref "IC7") (pin "5") (pinfunction "Y1_5") (pintype "output"))
    )
    (net (code "123") (name "Net-(IC19B-I)") (class "Default")
      (node (ref "IC19") (pin "3") (pinfunction "I_3") (pintype "input"))
      (node (ref "IC7") (pin "12") (pinfunction "Y0_12") (pintype "output"))
    )
    (net (code "124") (name "Net-(IC19E-I)") (class "Default")
      (node (ref "IC19") (pin "11") (pinfunction "I_11") (pintype "input"))
      (node (ref "IC53") (pin "5") (pinfunction "Y_5") (pintype "output"))
    )
    (net (code "125") (name "Net-(IC21A-Y0)") (class "Default")
      (node (ref "IC21") (pin "4") (pinfunction "Y0_4") (pintype "output"))
      (node (ref "SW1") (pin "1") (pinfunction "1_1") (pintype "passive"))
      (node (ref "SW1") (pin "2") (pinfunction "2_2") (pintype "passive"))
      (node (ref "SW1") (pin "3") (pinfunction "3_3") (pintype "passive"))
      (node (ref "SW1") (pin "4") (pinfunction "4_4") (pintype "passive"))
      (node (ref "SW1") (pin "5") (pinfunction "5_5") (pintype "passive"))
      (node (ref "SW1") (pin "6") (pinfunction "6_6") (pintype "passive"))
      (node (ref "SW1") (pin "7") (pinfunction "7_7") (pintype "passive"))
      (node (ref "SW1") (pin "8") (pinfunction "8_8") (pintype "passive"))
    )
    (net (code "126") (name "Net-(IC21A-Y1)") (class "Default")
      (node (ref "IC21") (pin "5") (pinfunction "Y1_5") (pintype "output"))
      (node (ref "SW2") (pin "1") (pinfunction "1_1") (pintype "passive"))
      (node (ref "SW2") (pin "2") (pinfunction "2_2") (pintype "passive"))
      (node (ref "SW2") (pin "3") (pinfunction "3_3") (pintype "passive"))
      (node (ref "SW2") (pin "4") (pinfunction "4_4") (pintype "passive"))
      (node (ref "SW2") (pin "5") (pinfunction "5_5") (pintype "passive"))
      (node (ref "SW2") (pin "6") (pinfunction "6_6") (pintype "passive"))
      (node (ref "SW2") (pin "7") (pinfunction "7_7") (pintype "passive"))
      (node (ref "SW2") (pin "8") (pinfunction "8_8") (pintype "passive"))
    )
    (net (code "127") (name "Net-(IC21A-Y2)") (class "Default")
      (node (ref "IC21") (pin "6") (pinfunction "Y2_6") (pintype "output"))
      (node (ref "SW3") (pin "1") (pinfunction "1_1") (pintype "passive"))
      (node (ref "SW3") (pin "2") (pinfunction "2_2") (pintype "passive"))
      (node (ref "SW3") (pin "3") (pinfunction "3_3") (pintype "passive"))
      (node (ref "SW3") (pin "4") (pinfunction "4_4") (pintype "passive"))
      (node (ref "SW3") (pin "5") (pinfunction "5_5") (pintype "passive"))
      (node (ref "SW3") (pin "6") (pinfunction "6_6") (pintype "passive"))
      (node (ref "SW3") (pin "7") (pinfunction "7_7") (pintype "passive"))
      (node (ref "SW3") (pin "8") (pinfunction "8_8") (pintype "passive"))
    )
    (net (code "128") (name "Net-(IC21A-Y3)") (class "Default")
      (node (ref "IC21") (pin "7") (pinfunction "Y3_7") (pintype "output"))
      (node (ref "SW4") (pin "1") (pinfunction "1_1") (pintype "passive"))
      (node (ref "SW4") (pin "2") (pinfunction "2_2") (pintype "passive"))
      (node (ref "SW4") (pin "3") (pinfunction "3_3") (pintype "passive"))
      (node (ref "SW4") (pin "4") (pinfunction "4_4") (pintype "passive"))
      (node (ref "SW4") (pin "5") (pinfunction "5_5") (pintype "passive"))
      (node (ref "SW4") (pin "6") (pinfunction "6_6") (pintype "passive"))
      (node (ref "SW4") (pin "7") (pinfunction "7_7") (pintype "passive"))
      (node (ref "SW4") (pin "8") (pinfunction "8_8") (pintype "passive"))
    )
    (net (code "129") (name "Net-(IC22C-I)") (class "Default")
      (node (ref "IC22") (pin "5") (pinfunction "I_5") (pintype "input"))
      (node (ref "IC28") (pin "19") (pinfunction "G_19") (pintype "input"))
      (node (ref "IC34") (pin "19") (pinfunction "G_19") (pintype "input"))
      (node (ref "IC41") (pin "8") (pinfunction "O_8") (pintype "output"))
    )
    (net (code "130") (name "Net-(IC40A-D)") (class "Default")
      (node (ref "IC40") (pin "2") (pinfunction "D_2") (pintype "input"))
      (node (ref "IC42") (pin "8") (pinfunction "O_8") (pintype "output"))
    )
    (net (code "131") (name "Net-(IC40B-~{Q})") (class "Default")
      (node (ref "IC40") (pin "8") (pinfunction "~{Q}_8") (pintype "output"))
      (node (ref "IC43") (pin "13") (pinfunction "I_13") (pintype "input"))
    )
    (net (code "132") (name "Net-(IC41A-O)") (class "Default")
      (node (ref "IC41") (pin "3") (pinfunction "O_3") (pintype "output"))
      (node (ref "IC43") (pin "1") (pinfunction "I_1") (pintype "input"))
      (node (ref "IC43") (pin "3") (pinfunction "I_3") (pintype "input"))
    )
    (net (code "133") (name "Net-(IC41B-I0)") (class "Default")
      (node (ref "IC41") (pin "4") (pinfunction "I0_4") (pintype "input"))
      (node (ref "IC42") (pin "12") (pinfunction "I7_12") (pintype "input"))
      (node (ref "IC46") (pin "3") (pinfunction "O_3") (pintype "output"))
    )
    (net (code "134") (name "Net-(IC41B-O)") (class "Default")
      (node (ref "IC41") (pin "6") (pinfunction "O_6") (pintype "output"))
      (node (ref "IC43") (pin "5") (pinfunction "I_5") (pintype "input"))
    )
    (net (code "135") (name "Net-(IC44A-CLK)") (class "Default")
      (node (ref "IC44") (pin "11") (pinfunction "CLK_11") (pintype "input"))
      (node (ref "IC45") (pin "11") (pinfunction "CLK_11") (pintype "input"))
      (node (ref "IC46") (pin "8") (pinfunction "O_8") (pintype "output"))
    )
    (net (code "136") (name "Net-(IC46A-I0)") (class "Default")
      (node (ref "IC46") (pin "1") (pinfunction "I0_1") (pintype "input"))
      (node (ref "IC46") (pin "6") (pinfunction "O_6") (pintype "output"))
    )
    (net (code "137") (name "Net-(IC46C-I0)") (class "Default")
      (node (ref "IC46") (pin "10") (pinfunction "I1_10") (pintype "input"))
      (node (ref "IC46") (pin "11") (pinfunction "O_11") (pintype "output"))
      (node (ref "IC46") (pin "9") (pinfunction "I0_9") (pintype "input"))
    )
    (net (code "138") (name "Net-(IC52A-O)") (class "Default")
      (node (ref "IC52") (pin "1") (pinfunction "O_1") (pintype "output"))
      (node (ref "IC52") (pin "5") (pinfunction "I0_5") (pintype "input"))
      (node (ref "IC52") (pin "6") (pinfunction "I1_6") (pintype "input"))
    )
    (net (code "139") (name "Net-(IC52C-O)") (class "Default")
      (node (ref "IC52") (pin "10") (pinfunction "O_10") (pintype "output"))
      (node (ref "IC52") (pin "11") (pinfunction "I0_11") (pintype "input"))
      (node (ref "IC52") (pin "12") (pinfunction "I1_12") (pintype "input"))
    )
    (net (code "140") (name "Net-(Q1-B)") (class "Default")
      (node (ref "Q1") (pin "2") (pinfunction "B_2") (pintype "passive"))
      (node (ref "Q2") (pin "2") (pinfunction "B_2") (pintype "passive"))
      (node (ref "R2") (pin "2") (pinfunction "2_2") (pintype "passive"))
    )
    (net (code "141") (name "Net-(U$19A-1)") (class "Default")
      (node (ref "D9") (pin "1") (pinfunction "1_1") (pintype "passive"))
      (node (ref "U$19") (pin "AA1") (pinfunction "1_AA1") (pintype "bidirectional"))
    )
    (net (code "142") (name "Net-(U$19AK-1)") (class "Default")
      (node (ref "D7") (pin "1") (pinfunction "1_1") (pintype "passive"))
      (node (ref "U$19") (pin "BA1") (pinfunction "1_BA1") (pintype "bidirectional"))
    )
    (net (code "143") (name "Net-(U$19AM-1)") (class "Default")
      (node (ref "D7") (pin "2") (pinfunction "2_2") (pintype "passive"))
      (node (ref "U$19") (pin "BB1") (pinfunction "1_BB1") (pintype "bidirectional"))
    )
    (net (code "144") (name "Net-(U$19BN-1)") (class "Default")
      (node (ref "D8") (pin "15") (pinfunction "15_15") (pintype "passive"))
      (node (ref "U$19") (pin "BS2") (pinfunction "1_BS2") (pintype "bidirectional"))
    )
    (net (code "145") (name "Net-(U$19BU-1)") (class "Default")
      (node (ref "D11") (pin "1") (pinfunction "1_1") (pintype "passive"))
      (node (ref "U$19") (pin "CA1") (pinfunction "1_CA1") (pintype "bidirectional"))
    )
    (net (code "146") (name "Net-(U$19BW-1)") (class "Default")
      (node (ref "D11") (pin "2") (pinfunction "2_2") (pintype "passive"))
      (node (ref "U$19") (pin "CB1") (pinfunction "1_CB1") (pintype "bidirectional"))
    )
    (net (code "147") (name "Net-(U$19C-1)") (class "Default")
      (node (ref "D9") (pin "2") (pinfunction "2_2") (pintype "passive"))
      (node (ref "U$19") (pin "AB1") (pinfunction "1_AB1") (pintype "bidirectional"))
    )
    (net (code "148") (name "Net-(U$19DE-1)") (class "Default")
      (node (ref "D13") (pin "1") (pinfunction "1_1") (pintype "passive"))
      (node (ref "U$19") (pin "DA1") (pinfunction "1_DA1") (pintype "bidirectional"))
    )
    (net (code "149") (name "Net-(U$19DG-1)") (class "Default")
      (node (ref "D13") (pin "2") (pinfunction "2_2") (pintype "passive"))
      (node (ref "U$19") (pin "DB1") (pinfunction "1_DB1") (pintype "bidirectional"))
    )
    (net (code "150") (name "PBIT") (class "Default")
      (node (ref "IC14") (pin "6") (pinfunction "ODD_6") (pintype "output"))
      (node (ref "IC50") (pin "6") (pinfunction "A5_6") (pintype "bidirectional"))
    )
    (net (code "151") (name "PCA") (class "Default")
      (node (ref "IC12") (pin "8") (pinfunction "O_8") (pintype "output"))
      (node (ref "IC35") (pin "17") (pinfunction "A4_17") (pintype "input"))
      (node (ref "IC38") (pin "5") (pinfunction "I1_5") (pintype "input"))
    )
    (net (code "152") (name "PER") (class "Default")
      (node (ref "IC30") (pin "11") (pinfunction "A1_11") (pintype "input"))
      (node (ref "IC9") (pin "9") (pinfunction "Q_9") (pintype "output"))
      (node (ref "SV1") (pin "21") (pinfunction "21_21") (pintype "passive"))
    )
    (net (code "153") (name "PIE") (class "Default")
      (node (ref "IC35") (pin "8") (pinfunction "A4_8") (pintype "input"))
      (node (ref "IC38") (pin "4") (pinfunction "I0_4") (pintype "input"))
      (node (ref "INTENB") (pin "2") (pinfunction "QB_2") (pintype "output"))
      (node (ref "SV1") (pin "5") (pinfunction "5_5") (pintype "passive"))
    )
    (net (code "154") (name "POWER_OK") (class "Default")
      (node (ref "D8") (pin "18") (pinfunction "18_18") (pintype "passive"))
      (node (ref "R2") (pin "1") (pinfunction "1_1") (pintype "passive"))
      (node (ref "U$19") (pin "BV2") (pinfunction "1_BV2") (pintype "bidirectional"))
    )
    (net (code "155") (name "PROTECT") (class "Default")
      (node (ref "IC5") (pin "6") (pinfunction "O_6") (pintype "output"))
      (node (ref "IC6") (pin "3") (pinfunction "B_3") (pintype "input"))
    )
    (net (code "156") (name "PULSE_LA") (class "Default")
      (node (ref "D14") (pin "14") (pinfunction "14_14") (pintype "passive"))
      (node (ref "U$19") (pin "DR2") (pinfunction "1_DR2") (pintype "bidirectional"))
    )
    (net (code "157") (name "RETURN") (class "Default")
      (node (ref "D10") (pin "14") (pinfunction "14_14") (pintype "passive"))
      (node (ref "U$19") (pin "AR2") (pinfunction "1_AR2") (pintype "bidirectional"))
    )
    (net (code "158") (name "SOURCE") (class "Default")
      (node (ref "D10") (pin "10") (pinfunction "10_10") (pintype "passive"))
      (node (ref "U$19") (pin "AL2") (pinfunction "1_AL2") (pintype "bidirectional"))
    )
    (net (code "159") (name "START") (class "Default")
      (node (ref "IC12") (pin "5") (pinfunction "I_5") (pintype "input"))
      (node (ref "IC18") (pin "3") (pinfunction "O_3") (pintype "output"))
    )
    (net (code "160") (name "STROBE") (class "Default")
      (node (ref "D10") (pin "11") (pinfunction "11_11") (pintype "passive"))
      (node (ref "U$19") (pin "AM2") (pinfunction "1_AM2") (pintype "bidirectional"))
    )
    (net (code "161") (name "SWITCH") (class "Default")
      (node (ref "D14") (pin "18") (pinfunction "18_18") (pintype "passive"))
      (node (ref "U$19") (pin "DV2") (pinfunction "1_DV2") (pintype "bidirectional"))
    )
    (net (code "162") (name "TP1") (class "Default")
      (node (ref "D12") (pin "4") (pinfunction "4_4") (pintype "passive"))
      (node (ref "IC40") (pin "11") (pinfunction "CLK_11") (pintype "input"))
      (node (ref "U$19") (pin "CD2") (pinfunction "1_CD2") (pintype "bidirectional"))
    )
    (net (code "163") (name "TP2") (class "Default")
      (node (ref "D12") (pin "5") (pinfunction "5_5") (pintype "passive"))
      (node (ref "U$19") (pin "CE2") (pinfunction "1_CE2") (pintype "bidirectional"))
    )
    (net (code "164") (name "TP3") (class "Default")
      (node (ref "D12") (pin "7") (pinfunction "7_7") (pintype "passive"))
      (node (ref "IC41") (pin "12") (pinfunction "I0_12") (pintype "input"))
      (node (ref "IC41") (pin "13") (pinfunction "I1_13") (pintype "input"))
      (node (ref "IC46") (pin "13") (pinfunction "I1_13") (pintype "input"))
      (node (ref "U$19") (pin "CH2") (pinfunction "1_CH2") (pintype "bidirectional"))
    )
    (net (code "165") (name "TP4") (class "Default")
      (node (ref "D12") (pin "8") (pinfunction "8_8") (pintype "passive"))
      (node (ref "IC40") (pin "3") (pinfunction "CLK_3") (pintype "input"))
      (node (ref "U$19") (pin "CJ2") (pinfunction "1_CJ2") (pintype "bidirectional"))
    )
    (net (code "166") (name "TS4") (class "Default")
      (node (ref "IC12") (pin "2") (pinfunction "O_2") (pintype "output"))
      (node (ref "IC41") (pin "5") (pinfunction "I1_5") (pintype "input"))
    )
    (net (code "167") (name "VCC") (class "Default")
      (node (ref "C1") (pin "1") (pinfunction "1_1") (pintype "passive"))
      (node (ref "C10") (pin "1") (pinfunction "1_1") (pintype "passive"))
      (node (ref "C11") (pin "1") (pinfunction "1_1") (pintype "passive"))
      (node (ref "C12") (pin "1") (pinfunction "1_1") (pintype "passive"))
      (node (ref "C13") (pin "1") (pinfunction "1_1") (pintype "passive"))
      (node (ref "C14") (pin "1") (pinfunction "1_1") (pintype "passive"))
      (node (ref "C15") (pin "1") (pinfunction "1_1") (pintype "passive"))
      (node (ref "C16") (pin "1") (pinfunction "1_1") (pintype "passive"))
      (node (ref "C17") (pin "1") (pinfunction "1_1") (pintype "passive"))
      (node (ref "C18") (pin "1") (pinfunction "1_1") (pintype "passive"))
      (node (ref "C19") (pin "1") (pinfunction "1_1") (pintype "passive"))
      (node (ref "C2") (pin "1") (pinfunction "1_1") (pintype "passive"))
      (node (ref "C20") (pin "1") (pinfunction "1_1") (pintype "passive"))
      (node (ref "C21") (pin "1") (pinfunction "1_1") (pintype "passive"))
      (node (ref "C22") (pin "1") (pinfunction "1_1") (pintype "passive"))
      (node (ref "C23") (pin "1") (pinfunction "1_1") (pintype "passive"))
      (node (ref "C24") (pin "1") (pinfunction "1_1") (pintype "passive"))
      (node (ref "C25") (pin "1") (pinfunction "1_1") (pintype "passive"))
      (node (ref "C26") (pin "1") (pinfunction "1_1") (pintype "passive"))
      (node (ref "C27") (pin "1") (pinfunction "1_1") (pintype "passive"))
      (node (ref "C28") (pin "1") (pinfunction "1_1") (pintype "passive"))
      (node (ref "C29") (pin "1") (pinfunction "1_1") (pintype "passive"))
      (node (ref "C3") (pin "1") (pinfunction "1_1") (pintype "passive"))
      (node (ref "C30") (pin "1") (pinfunction "1_1") (pintype "passive"))
      (node (ref "C31") (pin "1") (pinfunction "1_1") (pintype "passive"))
      (node (ref "C32") (pin "1") (pinfunction "1_1") (pintype "passive"))
      (node (ref "C33") (pin "1") (pinfunction "1_1") (pintype "passive"))
      (node (ref "C34") (pin "1") (pinfunction "1_1") (pintype "passive"))
      (node (ref "C35") (pin "1") (pinfunction "1_1") (pintype "passive"))
      (node (ref "C36") (pin "1") (pinfunction "1_1") (pintype "passive"))
      (node (ref "C37") (pin "1") (pinfunction "1_1") (pintype "passive"))
      (node (ref "C38") (pin "1") (pinfunction "1_1") (pintype "passive"))
      (node (ref "C39") (pin "1") (pinfunction "1_1") (pintype "passive"))
      (node (ref "C4") (pin "1") (pinfunction "1_1") (pintype "passive"))
      (node (ref "C40") (pin "1") (pinfunction "1_1") (pintype "passive"))
      (node (ref "C41") (pin "1") (pinfunction "1_1") (pintype "passive"))
      (node (ref "C42") (pin "1") (pinfunction "1_1") (pintype "passive"))
      (node (ref "C43") (pin "1") (pinfunction "1_1") (pintype "passive"))
      (node (ref "C44") (pin "1") (pinfunction "1_1") (pintype "passive"))
      (node (ref "C45") (pin "+") (pinfunction "+_+") (pintype "passive"))
      (node (ref "C46") (pin "1") (pinfunction "1_1") (pintype "passive"))
      (node (ref "C48") (pin "1") (pinfunction "1_1") (pintype "passive"))
      (node (ref "C5") (pin "1") (pinfunction "1_1") (pintype "passive"))
      (node (ref "C6") (pin "1") (pinfunction "1_1") (pintype "passive"))
      (node (ref "C7") (pin "1") (pinfunction "1_1") (pintype "passive"))
      (node (ref "C8") (pin "1") (pinfunction "1_1") (pintype "passive"))
      (node (ref "C9") (pin "1") (pinfunction "1_1") (pintype "passive"))
      (node (ref "D10") (pin "1") (pinfunction "1_1") (pintype "passive"))
      (node (ref "D12") (pin "1") (pinfunction "1_1") (pintype "passive"))
      (node (ref "D8") (pin "1") (pinfunction "1_1") (pintype "passive"))
      (node (ref "IC11") (pin "1") (pinfunction "CLR_1") (pintype "input"))
      (node (ref "IC11") (pin "10") (pinfunction "PRE_10") (pintype "input"))
      (node (ref "IC11") (pin "12") (pinfunction "D_12") (pintype "input"))
      (node (ref "IC11") (pin "2") (pinfunction "D_2") (pintype "input"))
      (node (ref "IC11") (pin "3") (pinfunction "CLK_3") (pintype "input"))
      (node (ref "IC11") (pin "4") (pinfunction "PRE_4") (pintype "input"))
      (node (ref "IC14") (pin "3") (pinfunction "EI_3") (pintype "input"))
      (node (ref "IC15") (pin "3") (pinfunction "EI_3") (pintype "input"))
      (node (ref "IC19") (pin "13") (pinfunction "I_13") (pintype "input"))
      (node (ref "IC23") (pin "1") (pinfunction "DIR_1") (pintype "input"))
      (node (ref "IC25") (pin "6") (pinfunction "G1_6") (pintype "input"))
      (node (ref "IC27") (pin "32") (pinfunction "VCC_32") (pintype "power_in"))
      (node (ref "IC28") (pin "1") (pinfunction "DIR_1") (pintype "input"))
      (node (ref "IC28") (pin "3") (pinfunction "A2_3") (pintype "bidirectional"))
      (node (ref "IC28") (pin "4") (pinfunction "A3_4") (pintype "bidirectional"))
      (node (ref "IC28") (pin "6") (pinfunction "A5_6") (pintype "bidirectional"))
      (node (ref "IC29") (pin "6") (pinfunction "G1_6") (pintype "input"))
      (node (ref "IC30") (pin "13") (pinfunction "A2_13") (pintype "input"))
      (node (ref "IC30") (pin "15") (pinfunction "A3_15") (pintype "input"))
      (node (ref "IC32") (pin "6") (pinfunction "G1_6") (pintype "input"))
      (node (ref "IC33") (pin "32") (pinfunction "VCC_32") (pintype "power_in"))
      (node (ref "IC34") (pin "1") (pinfunction "DIR_1") (pintype "input"))
      (node (ref "IC34") (pin "6") (pinfunction "A5_6") (pintype "bidirectional"))
      (node (ref "IC34") (pin "7") (pinfunction "A6_7") (pintype "bidirectional"))
      (node (ref "IC34") (pin "8") (pinfunction "A7_8") (pintype "bidirectional"))
      (node (ref "IC34") (pin "9") (pinfunction "A8_9") (pintype "bidirectional"))
      (node (ref "IC35") (pin "15") (pinfunction "A3_15") (pintype "input"))
      (node (ref "IC36") (pin "6") (pinfunction "G1_6") (pintype "input"))
      (node (ref "IC39") (pin "1") (pinfunction "DIR_1") (pintype "input"))
      (node (ref "IC40") (pin "1") (pinfunction "CLR_1") (pintype "input"))
      (node (ref "IC40") (pin "10") (pinfunction "PRE_10") (pintype "input"))
      (node (ref "IC40") (pin "13") (pinfunction "CLR_13") (pintype "input"))
      (node (ref "IC40") (pin "4") (pinfunction "PRE_4") (pintype "input"))
      (node (ref "IC47") (pin "32") (pinfunction "VCC_32") (pintype "power_in"))
      (node (ref "IC48") (pin "32") (pinfunction "VCC_32") (pintype "power_in"))
      (node (ref "IC49") (pin "1") (pinfunction "DIR_1") (pintype "input"))
      (node (ref "IC50") (pin "1") (pinfunction "DIR_1") (pintype "input"))
      (node (ref "IC51") (pin "6") (pinfunction "G1_6") (pintype "input"))
      (node (ref "IC53") (pin "1") (pinfunction "D3_1") (pintype "input"))
      (node (ref "IC53") (pin "12") (pinfunction "D7_12") (pintype "input"))
      (node (ref "IC53") (pin "13") (pinfunction "D6_13") (pintype "input"))
      (node (ref "IC53") (pin "4") (pinfunction "D0_4") (pintype "input"))
      (node (ref "IC8") (pin "14") (pinfunction "V+_14") (pintype "power_in"))
      (node (ref "IC8") (pin "4") (pinfunction "R_4") (pintype "input"))
      (node (ref "R1") (pin "2") (pinfunction "2_2") (pintype "passive"))
      (node (ref "RA") (pin "1") (pinfunction "1_1") (pintype "passive"))
      (node (ref "RL") (pin "1") (pinfunction "1_1") (pintype "passive"))
      (node (ref "SV1") (pin "25") (pinfunction "25_25") (pintype "passive"))
      (node (ref "SV1") (pin "26") (pinfunction "26_26") (pintype "passive"))
      (node (ref "U$19") (pin "AA2") (pinfunction "1_AA2") (pintype "bidirectional"))
      (node (ref "U$19") (pin "BA2") (pinfunction "1_BA2") (pintype "bidirectional"))
      (node (ref "U$19") (pin "CA2") (pinfunction "1_CA2") (pintype "bidirectional"))
    )
    (net (code "168") (name "WC") (class "Default")
      (node (ref "IC28") (pin "2") (pinfunction "A1_2") (pintype "bidirectional"))
      (node (ref "IC37") (pin "2") (pinfunction "Q1_2") (pintype "output"))
      (node (ref "IC37") (pin "5") (pinfunction "D2_5") (pintype "input"))
    )
    (net (code "169") (name "WLS") (class "Default")
      (node (ref "IC35") (pin "13") (pinfunction "A2_13") (pintype "input"))
      (node (ref "IC9") (pin "5") (pinfunction "Q_5") (pintype "output"))
      (node (ref "SV1") (pin "15") (pinfunction "15_15") (pintype "passive"))
    )
    (net (code "170") (name "WRITE") (class "Default")
      (node (ref "D10") (pin "15") (pinfunction "15_15") (pintype "passive"))
      (node (ref "U$19") (pin "AS2") (pinfunction "1_AS2") (pintype "bidirectional"))
    )
    (net (code "171") (name "WRITING") (class "Default")
      (node (ref "IC10") (pin "5") (pinfunction "Q_5") (pintype "output"))
      (node (ref "IC21") (pin "13") (pinfunction "B_13") (pintype "input"))
      (node (ref "IC21") (pin "14") (pinfunction "A_14") (pintype "input"))
      (node (ref "IC6") (pin "2") (pinfunction "A_2") (pintype "input"))
      (node (ref "SV1") (pin "9") (pinfunction "9_9") (pintype "passive"))
    )
    (net (code "172") (name "unconnected-(DAR4-7A-BO-Pad13)") (class "Default")
      (node (ref "DAR4-7") (pin "13") (pinfunction "BO_13") (pintype "output"))
    )
    (net (code "173") (name "unconnected-(DAR4-7A-CO-Pad12)") (class "Default")
      (node (ref "DAR4-7") (pin "12") (pinfunction "CO_12") (pintype "output"))
    )
    (net (code "174") (name "unconnected-(DAR8-11A-BO-Pad13)") (class "Default")
      (node (ref "DAR8-11") (pin "13") (pinfunction "BO_13") (pintype "output"))
    )
    (net (code "175") (name "unconnected-(DMA0-3A-BO-Pad13)") (class "Default")
      (node (ref "DMA0-3") (pin "13") (pinfunction "BO_13") (pintype "output"))
    )
    (net (code "176") (name "unconnected-(DMA4-7A-BO-Pad13)") (class "Default")
      (node (ref "DMA4-7") (pin "13") (pinfunction "BO_13") (pintype "output"))
    )
    (net (code "177") (name "unconnected-(DMA8-11A-BO-Pad13)") (class "Default")
      (node (ref "DMA8-11") (pin "13") (pinfunction "BO_13") (pintype "output"))
    )
    (net (code "178") (name "unconnected-(FIELDA-BO-Pad13)") (class "Default")
      (node (ref "FIELD") (pin "13") (pinfunction "BO_13") (pintype "output"))
    )
    (net (code "179") (name "unconnected-(FIELDA-CO-Pad12)") (class "Default")
      (node (ref "FIELD") (pin "12") (pinfunction "CO_12") (pintype "output"))
    )
    (net (code "180") (name "unconnected-(FIELDA-QD-Pad7)") (class "Default")
      (node (ref "FIELD") (pin "7") (pinfunction "QD_7") (pintype "output"))
    )
    (net (code "181") (name "unconnected-(IC1A-W-Pad6)") (class "Default")
      (node (ref "IC1") (pin "6") (pinfunction "W_6") (pintype "output"))
    )
    (net (code "182") (name "unconnected-(IC2A-W-Pad6)") (class "Default")
      (node (ref "IC2") (pin "6") (pinfunction "W_6") (pintype "output"))
    )
    (net (code "183") (name "unconnected-(IC3A-W-Pad6)") (class "Default")
      (node (ref "IC3") (pin "6") (pinfunction "W_6") (pintype "output"))
    )
    (net (code "184") (name "unconnected-(IC4A-W-Pad6)") (class "Default")
      (node (ref "IC4") (pin "6") (pinfunction "W_6") (pintype "output"))
    )
    (net (code "185") (name "unconnected-(IC6A-Y0-Pad4)") (class "Default")
      (node (ref "IC6") (pin "4") (pinfunction "Y0_4") (pintype "output"))
    )
    (net (code "186") (name "unconnected-(IC6A-Y2-Pad6)") (class "Default")
      (node (ref "IC6") (pin "6") (pinfunction "Y2_6") (pintype "output"))
    )
    (net (code "187") (name "unconnected-(IC6B-Y2-Pad10)") (class "Default")
      (node (ref "IC6") (pin "10") (pinfunction "Y2_10") (pintype "output"))
    )
    (net (code "188") (name "unconnected-(IC6B-Y3-Pad9)") (class "Default")
      (node (ref "IC6") (pin "9") (pinfunction "Y3_9") (pintype "output"))
    )
    (net (code "189") (name "unconnected-(IC7A-Y0-Pad4)") (class "Default")
      (node (ref "IC7") (pin "4") (pinfunction "Y0_4") (pintype "output"))
    )
    (net (code "190") (name "unconnected-(IC7A-Y2-Pad6)") (class "Default")
      (node (ref "IC7") (pin "6") (pinfunction "Y2_6") (pintype "output"))
    )
    (net (code "191") (name "unconnected-(IC7A-Y3-Pad7)") (class "Default")
      (node (ref "IC7") (pin "7") (pinfunction "Y3_7") (pintype "output"))
    )
    (net (code "192") (name "unconnected-(IC7B-Y1-Pad11)") (class "Default")
      (node (ref "IC7") (pin "11") (pinfunction "Y1_11") (pintype "output"))
    )
    (net (code "193") (name "unconnected-(IC7B-Y2-Pad10)") (class "Default")
      (node (ref "IC7") (pin "10") (pinfunction "Y2_10") (pintype "output"))
    )
    (net (code "194") (name "unconnected-(IC7B-Y3-Pad9)") (class "Default")
      (node (ref "IC7") (pin "9") (pinfunction "Y3_9") (pintype "output"))
    )
    (net (code "195") (name "unconnected-(IC10A-~{Q}-Pad6)") (class "Default")
      (node (ref "IC10") (pin "6") (pinfunction "~{Q}_6") (pintype "output"))
    )
    (net (code "196") (name "unconnected-(IC11A-Q-Pad5)") (class "Default")
      (node (ref "IC11") (pin "5") (pinfunction "Q_5") (pintype "output"))
    )
    (net (code "197") (name "unconnected-(IC11A-~{Q}-Pad6)") (class "Default")
      (node (ref "IC11") (pin "6") (pinfunction "~{Q}_6") (pintype "output"))
    )
    (net (code "198") (name "unconnected-(IC11B-~{Q}-Pad8)") (class "Default")
      (node (ref "IC11") (pin "8") (pinfunction "~{Q}_8") (pintype "output"))
    )
    (net (code "199") (name "unconnected-(IC13A-ODD-Pad6)") (class "Default")
      (node (ref "IC13") (pin "6") (pinfunction "ODD_6") (pintype "output"))
    )
    (net (code "200") (name "unconnected-(IC14A-EVN-Pad5)") (class "Default")
      (node (ref "IC14") (pin "5") (pinfunction "EVN_5") (pintype "output"))
    )
    (net (code "201") (name "unconnected-(IC15A-EVN-Pad5)") (class "Default")
      (node (ref "IC15") (pin "5") (pinfunction "EVN_5") (pintype "output"))
    )
    (net (code "202") (name "unconnected-(IC17A-Y0-Pad4)") (class "Default")
      (node (ref "IC17") (pin "4") (pinfunction "Y0_4") (pintype "output"))
    )
    (net (code "203") (name "unconnected-(IC17A-Y1-Pad5)") (class "Default")
      (node (ref "IC17") (pin "5") (pinfunction "Y1_5") (pintype "output"))
    )
    (net (code "204") (name "unconnected-(IC17A-Y3-Pad7)") (class "Default")
      (node (ref "IC17") (pin "7") (pinfunction "Y3_7") (pintype "output"))
    )
    (net (code "205") (name "unconnected-(IC17B-Y2-Pad10)") (class "Default")
      (node (ref "IC17") (pin "10") (pinfunction "Y2_10") (pintype "output"))
    )
    (net (code "206") (name "unconnected-(IC17B-Y3-Pad9)") (class "Default")
      (node (ref "IC17") (pin "9") (pinfunction "Y3_9") (pintype "output"))
    )
    (net (code "207") (name "unconnected-(IC20-Pad1)") (class "Default")
      (node (ref "IC20") (pin "1") (pinfunction "1_1") (pintype "passive"))
    )
    (net (code "208") (name "unconnected-(IC20-Pad2)") (class "Default")
      (node (ref "IC20") (pin "2") (pinfunction "2_2") (pintype "passive"))
    )
    (net (code "209") (name "unconnected-(IC20-Pad3)") (class "Default")
      (node (ref "IC20") (pin "3") (pinfunction "3_3") (pintype "passive"))
    )
    (net (code "210") (name "unconnected-(IC20-Pad4)") (class "Default")
      (node (ref "IC20") (pin "4") (pinfunction "4_4") (pintype "passive"))
    )
    (net (code "211") (name "unconnected-(IC20-Pad5)") (class "Default")
      (node (ref "IC20") (pin "5") (pinfunction "5_5") (pintype "passive"))
    )
    (net (code "212") (name "unconnected-(IC20-Pad6)") (class "Default")
      (node (ref "IC20") (pin "6") (pinfunction "6_6") (pintype "passive"))
    )
    (net (code "213") (name "unconnected-(IC20-Pad7)") (class "Default")
      (node (ref "IC20") (pin "7") (pinfunction "7_7") (pintype "passive"))
    )
    (net (code "214") (name "unconnected-(IC20-Pad8)") (class "Default")
      (node (ref "IC20") (pin "8") (pinfunction "8_8") (pintype "passive"))
    )
    (net (code "215") (name "unconnected-(IC20-Pad9)") (class "Default")
      (node (ref "IC20") (pin "9") (pinfunction "9_9") (pintype "passive"))
    )
    (net (code "216") (name "unconnected-(IC20-Pad10)") (class "Default")
      (node (ref "IC20") (pin "10") (pinfunction "10_10") (pintype "passive"))
    )
    (net (code "217") (name "unconnected-(IC20-Pad11)") (class "Default")
      (node (ref "IC20") (pin "11") (pinfunction "11_11") (pintype "passive"))
    )
    (net (code "218") (name "unconnected-(IC20-Pad12)") (class "Default")
      (node (ref "IC20") (pin "12") (pinfunction "12_12") (pintype "passive"))
    )
    (net (code "219") (name "unconnected-(IC20-Pad13)") (class "Default")
      (node (ref "IC20") (pin "13") (pinfunction "13_13") (pintype "passive"))
    )
    (net (code "220") (name "unconnected-(IC20-Pad14)") (class "Default")
      (node (ref "IC20") (pin "14") (pinfunction "14_14") (pintype "passive"))
    )
    (net (code "221") (name "unconnected-(IC20-Pad15)") (class "Default")
      (node (ref "IC20") (pin "15") (pinfunction "15_15") (pintype "passive"))
    )
    (net (code "222") (name "unconnected-(IC20-Pad16)") (class "Default")
      (node (ref "IC20") (pin "16") (pinfunction "16_16") (pintype "passive"))
    )
    (net (code "223") (name "unconnected-(IC20-Pad17)") (class "Default")
      (node (ref "IC20") (pin "17") (pinfunction "17_17") (pintype "passive"))
    )
    (net (code "224") (name "unconnected-(IC20-Pad18)") (class "Default")
      (node (ref "IC20") (pin "18") (pinfunction "18_18") (pintype "passive"))
    )
    (net (code "225") (name "unconnected-(IC20-Pad19)") (class "Default")
      (node (ref "IC20") (pin "19") (pinfunction "19_19") (pintype "passive"))
    )
    (net (code "226") (name "unconnected-(IC20-Pad20)") (class "Default")
      (node (ref "IC20") (pin "20") (pinfunction "20_20") (pintype "passive"))
    )
    (net (code "227") (name "unconnected-(IC21B-Y1-Pad11)") (class "Default")
      (node (ref "IC21") (pin "11") (pinfunction "Y1_11") (pintype "output"))
    )
    (net (code "228") (name "unconnected-(IC21B-Y2-Pad10)") (class "Default")
      (node (ref "IC21") (pin "10") (pinfunction "Y2_10") (pintype "output"))
    )
    (net (code "229") (name "unconnected-(IC25A-Y0-Pad15)") (class "Default")
      (node (ref "IC25") (pin "15") (pinfunction "Y0_15") (pintype "output"))
    )
    (net (code "230") (name "unconnected-(IC25A-Y1-Pad14)") (class "Default")
      (node (ref "IC25") (pin "14") (pinfunction "Y1_14") (pintype "output"))
    )
    (net (code "231") (name "unconnected-(IC25A-Y2-Pad13)") (class "Default")
      (node (ref "IC25") (pin "13") (pinfunction "Y2_13") (pintype "output"))
    )
    (net (code "232") (name "unconnected-(IC25A-Y4-Pad11)") (class "Default")
      (node (ref "IC25") (pin "11") (pinfunction "Y4_11") (pintype "output"))
    )
    (net (code "233") (name "unconnected-(IC29A-Y0-Pad15)") (class "Default")
      (node (ref "IC29") (pin "15") (pinfunction "Y0_15") (pintype "output"))
    )
    (net (code "234") (name "unconnected-(IC29A-Y1-Pad14)") (class "Default")
      (node (ref "IC29") (pin "14") (pinfunction "Y1_14") (pintype "output"))
    )
    (net (code "235") (name "unconnected-(IC29A-Y2-Pad13)") (class "Default")
      (node (ref "IC29") (pin "13") (pinfunction "Y2_13") (pintype "output"))
    )
    (net (code "236") (name "unconnected-(IC29A-Y4-Pad11)") (class "Default")
      (node (ref "IC29") (pin "11") (pinfunction "Y4_11") (pintype "output"))
    )
    (net (code "237") (name "unconnected-(IC30A-Y4-Pad12)") (class "Default")
      (node (ref "IC30") (pin "12") (pinfunction "Y4_12") (pintype "tri_state"))
    )
    (net (code "238") (name "unconnected-(IC32A-Y0-Pad15)") (class "Default")
      (node (ref "IC32") (pin "15") (pinfunction "Y0_15") (pintype "output"))
    )
    (net (code "239") (name "unconnected-(IC32A-Y1-Pad14)") (class "Default")
      (node (ref "IC32") (pin "14") (pinfunction "Y1_14") (pintype "output"))
    )
    (net (code "240") (name "unconnected-(IC32A-Y2-Pad13)") (class "Default")
      (node (ref "IC32") (pin "13") (pinfunction "Y2_13") (pintype "output"))
    )
    (net (code "241") (name "unconnected-(IC32A-Y4-Pad11)") (class "Default")
      (node (ref "IC32") (pin "11") (pinfunction "Y4_11") (pintype "output"))
    )
    (net (code "242") (name "unconnected-(IC34A-B8-Pad11)") (class "Default")
      (node (ref "IC34") (pin "11") (pinfunction "B8_11") (pintype "bidirectional"))
    )
    (net (code "243") (name "unconnected-(IC37A-Q4-Pad15)") (class "Default")
      (node (ref "IC37") (pin "15") (pinfunction "Q4_15") (pintype "output"))
    )
    (net (code "244") (name "unconnected-(IC37A-~{Q2}-Pad6)") (class "Default")
      (node (ref "IC37") (pin "6") (pinfunction "~{Q2}_6") (pintype "output"))
    )
    (net (code "245") (name "unconnected-(IC38D-O-Pad11)") (class "Default")
      (node (ref "IC38") (pin "11") (pinfunction "O_11") (pintype "open_collector"))
    )
    (net (code "246") (name "unconnected-(IC39A-A5-Pad6)") (class "Default")
      (node (ref "IC39") (pin "6") (pinfunction "A5_6") (pintype "bidirectional"))
    )
    (net (code "247") (name "unconnected-(IC39A-A6-Pad7)") (class "Default")
      (node (ref "IC39") (pin "7") (pinfunction "A6_7") (pintype "bidirectional"))
    )
    (net (code "248") (name "unconnected-(IC39A-A7-Pad8)") (class "Default")
      (node (ref "IC39") (pin "8") (pinfunction "A7_8") (pintype "bidirectional"))
    )
    (net (code "249") (name "unconnected-(IC39A-A8-Pad9)") (class "Default")
      (node (ref "IC39") (pin "9") (pinfunction "A8_9") (pintype "bidirectional"))
    )
    (net (code "250") (name "unconnected-(IC39A-B5-Pad14)") (class "Default")
      (node (ref "IC39") (pin "14") (pinfunction "B5_14") (pintype "bidirectional"))
    )
    (net (code "251") (name "unconnected-(IC39A-B6-Pad13)") (class "Default")
      (node (ref "IC39") (pin "13") (pinfunction "B6_13") (pintype "bidirectional"))
    )
    (net (code "252") (name "unconnected-(IC39A-B7-Pad12)") (class "Default")
      (node (ref "IC39") (pin "12") (pinfunction "B7_12") (pintype "bidirectional"))
    )
    (net (code "253") (name "unconnected-(IC39A-B8-Pad11)") (class "Default")
      (node (ref "IC39") (pin "11") (pinfunction "B8_11") (pintype "bidirectional"))
    )
    (net (code "254") (name "unconnected-(IC40B-Q-Pad9)") (class "Default")
      (node (ref "IC40") (pin "9") (pinfunction "Q_9") (pintype "output"))
    )
    (net (code "255") (name "unconnected-(IC45A-8Q-Pad12)") (class "Default")
      (node (ref "IC45") (pin "12") (pinfunction "8Q_12") (pintype "tri_state"))
    )
    (net (code "256") (name "unconnected-(IC47-I{slash}O5-Pad19)") (class "Default")
      (node (ref "IC47") (pin "19") (pinfunction "I/O5_19") (pintype "bidirectional"))
    )
    (net (code "257") (name "unconnected-(IC47-I{slash}O6-Pad20)") (class "Default")
      (node (ref "IC47") (pin "20") (pinfunction "I/O6_20") (pintype "bidirectional"))
    )
    (net (code "258") (name "unconnected-(IC47-I{slash}O7-Pad21)") (class "Default")
      (node (ref "IC47") (pin "21") (pinfunction "I/O7_21") (pintype "bidirectional"))
    )
    (net (code "259") (name "unconnected-(IC48-I{slash}O5-Pad19)") (class "Default")
      (node (ref "IC48") (pin "19") (pinfunction "I/O5_19") (pintype "bidirectional"))
    )
    (net (code "260") (name "unconnected-(IC48-I{slash}O6-Pad20)") (class "Default")
      (node (ref "IC48") (pin "20") (pinfunction "I/O6_20") (pintype "bidirectional"))
    )
    (net (code "261") (name "unconnected-(IC48-I{slash}O7-Pad21)") (class "Default")
      (node (ref "IC48") (pin "21") (pinfunction "I/O7_21") (pintype "bidirectional"))
    )
    (net (code "262") (name "unconnected-(IC50A-A6-Pad7)") (class "Default")
      (node (ref "IC50") (pin "7") (pinfunction "A6_7") (pintype "bidirectional"))
    )
    (net (code "263") (name "unconnected-(IC50A-A7-Pad8)") (class "Default")
      (node (ref "IC50") (pin "8") (pinfunction "A7_8") (pintype "bidirectional"))
    )
    (net (code "264") (name "unconnected-(IC50A-A8-Pad9)") (class "Default")
      (node (ref "IC50") (pin "9") (pinfunction "A8_9") (pintype "bidirectional"))
    )
    (net (code "265") (name "unconnected-(IC50A-B6-Pad13)") (class "Default")
      (node (ref "IC50") (pin "13") (pinfunction "B6_13") (pintype "bidirectional"))
    )
    (net (code "266") (name "unconnected-(IC50A-B7-Pad12)") (class "Default")
      (node (ref "IC50") (pin "12") (pinfunction "B7_12") (pintype "bidirectional"))
    )
    (net (code "267") (name "unconnected-(IC50A-B8-Pad11)") (class "Default")
      (node (ref "IC50") (pin "11") (pinfunction "B8_11") (pintype "bidirectional"))
    )
    (net (code "268") (name "unconnected-(IC51A-Y0-Pad15)") (class "Default")
      (node (ref "IC51") (pin "15") (pinfunction "Y0_15") (pintype "output"))
    )
    (net (code "269") (name "unconnected-(IC51A-Y3-Pad12)") (class "Default")
      (node (ref "IC51") (pin "12") (pinfunction "Y3_12") (pintype "output"))
    )
    (net (code "270") (name "unconnected-(IC51A-Y4-Pad11)") (class "Default")
      (node (ref "IC51") (pin "11") (pinfunction "Y4_11") (pintype "output"))
    )
    (net (code "271") (name "unconnected-(IC51A-Y7-Pad7)") (class "Default")
      (node (ref "IC51") (pin "7") (pinfunction "Y7_7") (pintype "output"))
    )
    (net (code "272") (name "unconnected-(IC52D-O-Pad13)") (class "Default")
      (node (ref "IC52") (pin "13") (pinfunction "O_13") (pintype "output"))
    )
    (net (code "273") (name "unconnected-(IC53A-W-Pad6)") (class "Default")
      (node (ref "IC53") (pin "6") (pinfunction "W_6") (pintype "output"))
    )
    (net (code "274") (name "unconnected-(INTENBA-BO-Pad13)") (class "Default")
      (node (ref "INTENB") (pin "13") (pinfunction "BO_13") (pintype "output"))
    )
    (net (code "275") (name "unconnected-(INTENBA-CO-Pad12)") (class "Default")
      (node (ref "INTENB") (pin "12") (pinfunction "CO_12") (pintype "output"))
    )
    (net (code "276") (name "unconnected-(INTENBA-QD-Pad7)") (class "Default")
      (node (ref "INTENB") (pin "7") (pinfunction "QD_7") (pintype "output"))
    )
    (net (code "277") (name "unconnected-(SV1-Pad7)") (class "Default")
      (node (ref "SV1") (pin "7") (pinfunction "7_7") (pintype "passive"))
    )
    (net (code "278") (name "unconnected-(SV1-Pad13)") (class "Default")
      (node (ref "SV1") (pin "13") (pinfunction "13_13") (pintype "passive"))
    )
    (net (code "279") (name "~{601}") (class "Default")
      (node (ref "IC16") (pin "6") (pinfunction "I1_6") (pintype "input"))
      (node (ref "IC18") (pin "12") (pinfunction "I0_12") (pintype "input"))
      (node (ref "IC32") (pin "7") (pinfunction "Y7_7") (pintype "output"))
    )
    (net (code "280") (name "~{602}") (class "Default")
      (node (ref "IC16") (pin "9") (pinfunction "I1_9") (pintype "input"))
      (node (ref "IC18") (pin "1") (pinfunction "I0_1") (pintype "input"))
      (node (ref "IC29") (pin "7") (pinfunction "Y7_7") (pintype "output"))
    )
    (net (code "281") (name "~{604}") (class "Default")
      (node (ref "IC10") (pin "4") (pinfunction "PRE_4") (pintype "input"))
      (node (ref "IC18") (pin "2") (pinfunction "I1_2") (pintype "input"))
      (node (ref "IC25") (pin "7") (pinfunction "Y7_7") (pintype "output"))
    )
    (net (code "282") (name "~{611}") (class "Default")
      (node (ref "IC32") (pin "9") (pinfunction "Y6_9") (pintype "output"))
      (node (ref "IC51") (pin "1") (pinfunction "A_1") (pintype "input"))
    )
    (net (code "283") (name "~{612}") (class "Default")
      (node (ref "IC29") (pin "9") (pinfunction "Y6_9") (pintype "output"))
      (node (ref "IC51") (pin "2") (pinfunction "B_2") (pintype "input"))
      (node (ref "IC53") (pin "14") (pinfunction "D5_14") (pintype "input"))
    )
    (net (code "284") (name "~{614}") (class "Default")
      (node (ref "IC25") (pin "9") (pinfunction "Y6_9") (pintype "output"))
      (node (ref "IC51") (pin "3") (pinfunction "C_3") (pintype "input"))
    )
    (net (code "285") (name "~{621}") (class "Default")
      (node (ref "IC32") (pin "10") (pinfunction "Y5_10") (pintype "output"))
      (node (ref "IC7") (pin "3") (pinfunction "B_3") (pintype "input"))
    )
    (net (code "286") (name "~{622}") (class "Default")
      (node (ref "IC29") (pin "10") (pinfunction "Y5_10") (pintype "output"))
      (node (ref "IC7") (pin "13") (pinfunction "B_13") (pintype "input"))
    )
    (net (code "287") (name "~{624}") (class "Default")
      (node (ref "IC22") (pin "13") (pinfunction "I_13") (pintype "input"))
      (node (ref "IC24") (pin "1") (pinfunction "G_1") (pintype "input"))
      (node (ref "IC25") (pin "10") (pinfunction "Y5_10") (pintype "output"))
      (node (ref "IC26") (pin "1") (pinfunction "G_1") (pintype "input"))
      (node (ref "IC31") (pin "1") (pinfunction "G_1") (pintype "input"))
    )
    (net (code "288") (name "~{641}") (class "Default")
      (node (ref "IC32") (pin "12") (pinfunction "Y3_12") (pintype "output"))
      (node (ref "IC6") (pin "13") (pinfunction "B_13") (pintype "input"))
    )
    (net (code "289") (name "~{642}") (class "Default")
      (node (ref "DAR4-7") (pin "11") (pinfunction "LD_11") (pintype "input"))
      (node (ref "DAR8-11") (pin "11") (pinfunction "LD_11") (pintype "input"))
      (node (ref "IC29") (pin "12") (pinfunction "Y3_12") (pintype "output"))
      (node (ref "IC53") (pin "15") (pinfunction "D4_15") (pintype "input"))
    )
    (net (code "290") (name "~{644}") (class "Default")
      (node (ref "IC25") (pin "12") (pinfunction "Y3_12") (pintype "output"))
      (node (ref "IC6") (pin "14") (pinfunction "A_14") (pintype "input"))
    )
    (net (code "291") (name "~{BMD00}") (class "Default")
      (node (ref "IC13") (pin "12") (pinfunction "E_12") (pintype "input"))
      (node (ref "IC14") (pin "12") (pinfunction "E_12") (pintype "input"))
      (node (ref "IC39") (pin "5") (pinfunction "A4_5") (pintype "bidirectional"))
      (node (ref "IC47") (pin "17") (pinfunction "I/O3_17") (pintype "bidirectional"))
      (node (ref "IC48") (pin "17") (pinfunction "I/O3_17") (pintype "bidirectional"))
      (node (ref "IC50") (pin "15") (pinfunction "B4_15") (pintype "bidirectional"))
      (node (ref "SV1") (pin "2") (pinfunction "2_2") (pintype "passive"))
    )
    (net (code "292") (name "~{BMD01}") (class "Default")
      (node (ref "IC13") (pin "11") (pinfunction "D_11") (pintype "input"))
      (node (ref "IC14") (pin "11") (pinfunction "D_11") (pintype "input"))
      (node (ref "IC39") (pin "4") (pinfunction "A3_4") (pintype "bidirectional"))
      (node (ref "IC47") (pin "15") (pinfunction "I/O2_15") (pintype "bidirectional"))
      (node (ref "IC48") (pin "15") (pinfunction "I/O2_15") (pintype "bidirectional"))
      (node (ref "IC50") (pin "16") (pinfunction "B3_16") (pintype "bidirectional"))
      (node (ref "SV1") (pin "4") (pinfunction "4_4") (pintype "passive"))
    )
    (net (code "293") (name "~{BMD02}") (class "Default")
      (node (ref "IC13") (pin "10") (pinfunction "C_10") (pintype "input"))
      (node (ref "IC14") (pin "10") (pinfunction "C_10") (pintype "input"))
      (node (ref "IC39") (pin "3") (pinfunction "A2_3") (pintype "bidirectional"))
      (node (ref "IC47") (pin "14") (pinfunction "I/O1_14") (pintype "bidirectional"))
      (node (ref "IC48") (pin "14") (pinfunction "I/O1_14") (pintype "bidirectional"))
      (node (ref "IC50") (pin "17") (pinfunction "B2_17") (pintype "bidirectional"))
      (node (ref "SV1") (pin "6") (pinfunction "6_6") (pintype "passive"))
    )
    (net (code "294") (name "~{BMD03}") (class "Default")
      (node (ref "IC13") (pin "9") (pinfunction "B_9") (pintype "input"))
      (node (ref "IC14") (pin "9") (pinfunction "B_9") (pintype "input"))
      (node (ref "IC36") (pin "3") (pinfunction "C_3") (pintype "input"))
      (node (ref "IC39") (pin "2") (pinfunction "A1_2") (pintype "bidirectional"))
      (node (ref "IC47") (pin "13") (pinfunction "I/O0_13") (pintype "bidirectional"))
      (node (ref "IC48") (pin "13") (pinfunction "I/O0_13") (pintype "bidirectional"))
      (node (ref "IC50") (pin "18") (pinfunction "B1_18") (pintype "bidirectional"))
      (node (ref "SV1") (pin "8") (pinfunction "8_8") (pintype "passive"))
    )
    (net (code "295") (name "~{BMD04}") (class "Default")
      (node (ref "IC15") (pin "2") (pinfunction "H_2") (pintype "input"))
      (node (ref "IC23") (pin "9") (pinfunction "A8_9") (pintype "bidirectional"))
      (node (ref "IC27") (pin "21") (pinfunction "I/O7_21") (pintype "bidirectional"))
      (node (ref "IC33") (pin "21") (pinfunction "I/O7_21") (pintype "bidirectional"))
      (node (ref "IC36") (pin "2") (pinfunction "B_2") (pintype "input"))
      (node (ref "IC49") (pin "11") (pinfunction "B8_11") (pintype "bidirectional"))
      (node (ref "SV1") (pin "10") (pinfunction "10_10") (pintype "passive"))
    )
    (net (code "296") (name "~{BMD05}") (class "Default")
      (node (ref "IC15") (pin "1") (pinfunction "G_1") (pintype "input"))
      (node (ref "IC23") (pin "8") (pinfunction "A7_8") (pintype "bidirectional"))
      (node (ref "IC27") (pin "20") (pinfunction "I/O6_20") (pintype "bidirectional"))
      (node (ref "IC33") (pin "20") (pinfunction "I/O6_20") (pintype "bidirectional"))
      (node (ref "IC36") (pin "1") (pinfunction "A_1") (pintype "input"))
      (node (ref "IC49") (pin "12") (pinfunction "B7_12") (pintype "bidirectional"))
      (node (ref "SV1") (pin "12") (pinfunction "12_12") (pintype "passive"))
    )
    (net (code "297") (name "~{BMD06}") (class "Default")
      (node (ref "IC15") (pin "13") (pinfunction "F_13") (pintype "input"))
      (node (ref "IC23") (pin "7") (pinfunction "A6_7") (pintype "bidirectional"))
      (node (ref "IC25") (pin "3") (pinfunction "C_3") (pintype "input"))
      (node (ref "IC27") (pin "19") (pinfunction "I/O5_19") (pintype "bidirectional"))
      (node (ref "IC29") (pin "3") (pinfunction "C_3") (pintype "input"))
      (node (ref "IC32") (pin "3") (pinfunction "C_3") (pintype "input"))
      (node (ref "IC33") (pin "19") (pinfunction "I/O5_19") (pintype "bidirectional"))
      (node (ref "IC49") (pin "13") (pinfunction "B6_13") (pintype "bidirectional"))
      (node (ref "SV1") (pin "14") (pinfunction "14_14") (pintype "passive"))
    )
    (net (code "298") (name "~{BMD07}") (class "Default")
      (node (ref "IC15") (pin "12") (pinfunction "E_12") (pintype "input"))
      (node (ref "IC23") (pin "6") (pinfunction "A5_6") (pintype "bidirectional"))
      (node (ref "IC25") (pin "2") (pinfunction "B_2") (pintype "input"))
      (node (ref "IC27") (pin "18") (pinfunction "I/O4_18") (pintype "bidirectional"))
      (node (ref "IC29") (pin "2") (pinfunction "B_2") (pintype "input"))
      (node (ref "IC32") (pin "2") (pinfunction "B_2") (pintype "input"))
      (node (ref "IC33") (pin "18") (pinfunction "I/O4_18") (pintype "bidirectional"))
      (node (ref "IC49") (pin "14") (pinfunction "B5_14") (pintype "bidirectional"))
      (node (ref "SV1") (pin "16") (pinfunction "16_16") (pintype "passive"))
    )
    (net (code "299") (name "~{BMD08}") (class "Default")
      (node (ref "IC15") (pin "11") (pinfunction "D_11") (pintype "input"))
      (node (ref "IC23") (pin "5") (pinfunction "A4_5") (pintype "bidirectional"))
      (node (ref "IC25") (pin "1") (pinfunction "A_1") (pintype "input"))
      (node (ref "IC27") (pin "17") (pinfunction "I/O3_17") (pintype "bidirectional"))
      (node (ref "IC29") (pin "1") (pinfunction "A_1") (pintype "input"))
      (node (ref "IC32") (pin "1") (pinfunction "A_1") (pintype "input"))
      (node (ref "IC33") (pin "17") (pinfunction "I/O3_17") (pintype "bidirectional"))
      (node (ref "IC49") (pin "15") (pinfunction "B4_15") (pintype "bidirectional"))
      (node (ref "SV1") (pin "18") (pinfunction "18_18") (pintype "passive"))
    )
    (net (code "300") (name "~{BMD09}") (class "Default")
      (node (ref "IC15") (pin "10") (pinfunction "C_10") (pintype "input"))
      (node (ref "IC17") (pin "3") (pinfunction "B_3") (pintype "input"))
      (node (ref "IC23") (pin "4") (pinfunction "A3_4") (pintype "bidirectional"))
      (node (ref "IC25") (pin "5") (pinfunction "G2B_5") (pintype "input"))
      (node (ref "IC27") (pin "15") (pinfunction "I/O2_15") (pintype "bidirectional"))
      (node (ref "IC33") (pin "15") (pinfunction "I/O2_15") (pintype "bidirectional"))
      (node (ref "IC49") (pin "16") (pinfunction "B3_16") (pintype "bidirectional"))
      (node (ref "IC53") (pin "9") (pinfunction "C_9") (pintype "input"))
      (node (ref "SV1") (pin "20") (pinfunction "20_20") (pintype "passive"))
    )
    (net (code "301") (name "~{BMD10}") (class "Default")
      (node (ref "IC15") (pin "9") (pinfunction "B_9") (pintype "input"))
      (node (ref "IC23") (pin "3") (pinfunction "A2_3") (pintype "bidirectional"))
      (node (ref "IC27") (pin "14") (pinfunction "I/O1_14") (pintype "bidirectional"))
      (node (ref "IC29") (pin "5") (pinfunction "G2B_5") (pintype "input"))
      (node (ref "IC33") (pin "14") (pinfunction "I/O1_14") (pintype "bidirectional"))
      (node (ref "IC49") (pin "17") (pinfunction "B2_17") (pintype "bidirectional"))
      (node (ref "IC53") (pin "10") (pinfunction "B_10") (pintype "input"))
      (node (ref "SV1") (pin "22") (pinfunction "22_22") (pintype "passive"))
    )
    (net (code "302") (name "~{BMD11}") (class "Default")
      (node (ref "IC15") (pin "8") (pinfunction "A_8") (pintype "input"))
      (node (ref "IC23") (pin "2") (pinfunction "A1_2") (pintype "bidirectional"))
      (node (ref "IC27") (pin "13") (pinfunction "I/O0_13") (pintype "bidirectional"))
      (node (ref "IC32") (pin "5") (pinfunction "G2B_5") (pintype "input"))
      (node (ref "IC33") (pin "13") (pinfunction "I/O0_13") (pintype "bidirectional"))
      (node (ref "IC49") (pin "18") (pinfunction "B1_18") (pintype "bidirectional"))
      (node (ref "IC53") (pin "11") (pinfunction "A_11") (pintype "input"))
      (node (ref "SV1") (pin "24") (pinfunction "24_24") (pintype "passive"))
    )
    (net (code "303") (name "~{BREAK_CYCLE}") (class "Default")
      (node (ref "D8") (pin "10") (pinfunction "10_10") (pintype "passive"))
      (node (ref "IC43") (pin "10") (pinfunction "O_10") (pintype "open_collector"))
      (node (ref "U$19") (pin "BL2") (pinfunction "1_BL2") (pintype "bidirectional"))
    )
    (net (code "304") (name "~{BRK_DATA_CONT}") (class "Default")
      (node (ref "D8") (pin "9") (pinfunction "9_9") (pintype "passive"))
      (node (ref "IC22") (pin "6") (pinfunction "O_6") (pintype "open_collector"))
      (node (ref "U$19") (pin "BK2") (pinfunction "1_BK2") (pintype "bidirectional"))
    )
    (net (code "305") (name "~{BRK_IN_PROG}") (class "Default")
      (node (ref "D8") (pin "5") (pinfunction "5_5") (pintype "passive"))
      (node (ref "IC43") (pin "2") (pinfunction "O_2") (pintype "open_collector"))
      (node (ref "U$19") (pin "BE2") (pinfunction "1_BE2") (pintype "bidirectional"))
    )
    (net (code "306") (name "~{BUSY}") (class "Default")
      (node (ref "IC10") (pin "8") (pinfunction "~{Q}_8") (pintype "output"))
      (node (ref "IC11") (pin "11") (pinfunction "CLK_11") (pintype "input"))
      (node (ref "IC16") (pin "3") (pinfunction "I1_3") (pintype "input"))
    )
    (net (code "307") (name "~{BUS_STROBE}") (class "Default")
      (node (ref "D11") (pin "9") (pinfunction "9_9") (pintype "passive"))
      (node (ref "U$19") (pin "CK1") (pinfunction "1_CK1") (pintype "bidirectional"))
    )
    (net (code "308") (name "~{BWC0}") (class "Default")
      (node (ref "IC18") (pin "4") (pinfunction "I0_4") (pintype "input"))
      (node (ref "IC52") (pin "4") (pinfunction "O_4") (pintype "output"))
      (node (ref "SV1") (pin "19") (pinfunction "19_19") (pintype "passive"))
    )
    (net (code "309") (name "~{C0}") (class "Default")
      (node (ref "D11") (pin "5") (pinfunction "5_5") (pintype "passive"))
      (node (ref "IC19") (pin "10") (pinfunction "O_10") (pintype "open_collector"))
      (node (ref "U$19") (pin "CE1") (pinfunction "1_CE1") (pintype "bidirectional"))
    )
    (net (code "310") (name "~{C1}") (class "Default")
      (node (ref "D11") (pin "7") (pinfunction "7_7") (pintype "passive"))
      (node (ref "IC22") (pin "12") (pinfunction "O_12") (pintype "open_collector"))
      (node (ref "IC22") (pin "2") (pinfunction "O_2") (pintype "open_collector"))
      (node (ref "IC22") (pin "4") (pinfunction "O_4") (pintype "open_collector"))
      (node (ref "U$19") (pin "CH1") (pinfunction "1_CH1") (pintype "bidirectional"))
    )
    (net (code "311") (name "~{C2}") (class "Default")
      (node (ref "D11") (pin "8") (pinfunction "8_8") (pintype "passive"))
      (node (ref "U$19") (pin "CJ1") (pinfunction "1_CJ1") (pintype "bidirectional"))
    )
    (net (code "312") (name "~{CPMA_DISABLE}") (class "Default")
      (node (ref "D11") (pin "17") (pinfunction "17_17") (pintype "passive"))
      (node (ref "IC43") (pin "4") (pinfunction "O_4") (pintype "open_collector"))
      (node (ref "U$19") (pin "CU1") (pinfunction "1_CU1") (pintype "bidirectional"))
    )
    (net (code "313") (name "~{CS0}") (class "Default")
      (node (ref "IC27") (pin "22") (pinfunction "~{CS}_22") (pintype "input"))
      (node (ref "IC33") (pin "22") (pinfunction "~{CS}_22") (pintype "input"))
      (node (ref "Q1") (pin "1") (pinfunction "C_1") (pintype "passive"))
      (node (ref "R3") (pin "1") (pinfunction "1_1") (pintype "passive"))
    )
    (net (code "314") (name "~{CS1}") (class "Default")
      (node (ref "IC47") (pin "22") (pinfunction "~{CS}_22") (pintype "input"))
      (node (ref "IC48") (pin "22") (pinfunction "~{CS}_22") (pintype "input"))
      (node (ref "Q2") (pin "1") (pinfunction "C_1") (pintype "passive"))
      (node (ref "R4") (pin "1") (pinfunction "1_1") (pintype "passive"))
    )
    (net (code "315") (name "~{DATA0}") (class "Default")
      (node (ref "D9") (pin "14") (pinfunction "14_14") (pintype "passive"))
      (node (ref "IC26") (pin "12") (pinfunction "Y4_12") (pintype "tri_state"))
      (node (ref "IC26") (pin "3") (pinfunction "Y4_3") (pintype "tri_state"))
      (node (ref "IC35") (pin "3") (pinfunction "Y4_3") (pintype "tri_state"))
      (node (ref "IC39") (pin "15") (pinfunction "B4_15") (pintype "bidirectional"))
      (node (ref "IC42") (pin "1") (pinfunction "I0_1") (pintype "input"))
      (node (ref "IC55") (pin "14") (pinfunction "2A2_14") (pintype "input"))
      (node (ref "U$19") (pin "AR1") (pinfunction "1_AR1") (pintype "bidirectional"))
    )
    (net (code "316") (name "~{DATA1}") (class "Default")
      (node (ref "D9") (pin "15") (pinfunction "15_15") (pintype "passive"))
      (node (ref "IC26") (pin "14") (pinfunction "Y3_14") (pintype "tri_state"))
      (node (ref "IC26") (pin "5") (pinfunction "Y3_5") (pintype "tri_state"))
      (node (ref "IC35") (pin "5") (pinfunction "Y3_5") (pintype "tri_state"))
      (node (ref "IC39") (pin "16") (pinfunction "B3_16") (pintype "bidirectional"))
      (node (ref "IC42") (pin "2") (pinfunction "I1_2") (pintype "input"))
      (node (ref "IC55") (pin "12") (pinfunction "2A1_12") (pintype "input"))
      (node (ref "U$19") (pin "AS1") (pinfunction "1_AS1") (pintype "bidirectional"))
    )
    (net (code "317") (name "~{DATA2}") (class "Default")
      (node (ref "D9") (pin "17") (pinfunction "17_17") (pintype "passive"))
      (node (ref "IC26") (pin "16") (pinfunction "Y2_16") (pintype "tri_state"))
      (node (ref "IC26") (pin "7") (pinfunction "Y2_7") (pintype "tri_state"))
      (node (ref "IC35") (pin "7") (pinfunction "Y2_7") (pintype "tri_state"))
      (node (ref "IC39") (pin "17") (pinfunction "B2_17") (pintype "bidirectional"))
      (node (ref "IC42") (pin "3") (pinfunction "I2_3") (pintype "input"))
      (node (ref "IC55") (pin "10") (pinfunction "1A4_10") (pintype "input"))
      (node (ref "U$19") (pin "AU1") (pinfunction "1_AU1") (pintype "bidirectional"))
    )
    (net (code "318") (name "~{DATA3}") (class "Default")
      (node (ref "D9") (pin "18") (pinfunction "18_18") (pintype "passive"))
      (node (ref "IC26") (pin "18") (pinfunction "Y1_18") (pintype "tri_state"))
      (node (ref "IC26") (pin "9") (pinfunction "Y1_9") (pintype "tri_state"))
      (node (ref "IC35") (pin "9") (pinfunction "Y1_9") (pintype "tri_state"))
      (node (ref "IC39") (pin "18") (pinfunction "B1_18") (pintype "bidirectional"))
      (node (ref "IC42") (pin "4") (pinfunction "I3_4") (pintype "input"))
      (node (ref "IC55") (pin "6") (pinfunction "1A3_6") (pintype "input"))
      (node (ref "U$19") (pin "AV1") (pinfunction "1_AV1") (pintype "bidirectional"))
    )
    (net (code "319") (name "~{DATA4}") (class "Default")
      (node (ref "D7") (pin "14") (pinfunction "14_14") (pintype "passive"))
      (node (ref "IC23") (pin "11") (pinfunction "B8_11") (pintype "bidirectional"))
      (node (ref "IC31") (pin "12") (pinfunction "Y4_12") (pintype "tri_state"))
      (node (ref "IC31") (pin "3") (pinfunction "Y4_3") (pintype "tri_state"))
      (node (ref "IC35") (pin "12") (pinfunction "Y4_12") (pintype "tri_state"))
      (node (ref "IC42") (pin "5") (pinfunction "I4_5") (pintype "input"))
      (node (ref "IC55") (pin "4") (pinfunction "1A2_4") (pintype "input"))
      (node (ref "U$19") (pin "BR1") (pinfunction "1_BR1") (pintype "bidirectional"))
    )
    (net (code "320") (name "~{DATA5}") (class "Default")
      (node (ref "D7") (pin "15") (pinfunction "15_15") (pintype "passive"))
      (node (ref "IC23") (pin "12") (pinfunction "B7_12") (pintype "bidirectional"))
      (node (ref "IC31") (pin "14") (pinfunction "Y3_14") (pintype "tri_state"))
      (node (ref "IC31") (pin "5") (pinfunction "Y3_5") (pintype "tri_state"))
      (node (ref "IC35") (pin "14") (pinfunction "Y3_14") (pintype "tri_state"))
      (node (ref "IC42") (pin "6") (pinfunction "I5_6") (pintype "input"))
      (node (ref "IC55") (pin "2") (pinfunction "1A1_2") (pintype "input"))
      (node (ref "U$19") (pin "BS1") (pinfunction "1_BS1") (pintype "bidirectional"))
    )
    (net (code "321") (name "~{DATA6}") (class "Default")
      (node (ref "D7") (pin "17") (pinfunction "17_17") (pintype "passive"))
      (node (ref "IC23") (pin "13") (pinfunction "B6_13") (pintype "bidirectional"))
      (node (ref "IC31") (pin "16") (pinfunction "Y2_16") (pintype "tri_state"))
      (node (ref "IC31") (pin "7") (pinfunction "Y2_7") (pintype "tri_state"))
      (node (ref "IC35") (pin "16") (pinfunction "Y2_16") (pintype "tri_state"))
      (node (ref "IC42") (pin "11") (pinfunction "I6_11") (pintype "input"))
      (node (ref "IC54") (pin "14") (pinfunction "2A2_14") (pintype "input"))
      (node (ref "U$19") (pin "BU1") (pinfunction "1_BU1") (pintype "bidirectional"))
    )
    (net (code "322") (name "~{DATA7}") (class "Default")
      (node (ref "D7") (pin "18") (pinfunction "18_18") (pintype "passive"))
      (node (ref "IC23") (pin "14") (pinfunction "B5_14") (pintype "bidirectional"))
      (node (ref "IC31") (pin "18") (pinfunction "Y1_18") (pintype "tri_state"))
      (node (ref "IC31") (pin "9") (pinfunction "Y1_9") (pintype "tri_state"))
      (node (ref "IC35") (pin "18") (pinfunction "Y1_18") (pintype "tri_state"))
      (node (ref "IC43") (pin "6") (pinfunction "O_6") (pintype "open_collector"))
      (node (ref "IC54") (pin "12") (pinfunction "2A1_12") (pintype "input"))
      (node (ref "U$19") (pin "BV1") (pinfunction "1_BV1") (pintype "bidirectional"))
    )
    (net (code "323") (name "~{DATA8}") (class "Default")
      (node (ref "D13") (pin "14") (pinfunction "14_14") (pintype "passive"))
      (node (ref "IC23") (pin "15") (pinfunction "B4_15") (pintype "bidirectional"))
      (node (ref "IC24") (pin "12") (pinfunction "Y4_12") (pintype "tri_state"))
      (node (ref "IC24") (pin "3") (pinfunction "Y4_3") (pintype "tri_state"))
      (node (ref "IC30") (pin "3") (pinfunction "Y4_3") (pintype "tri_state"))
      (node (ref "IC54") (pin "10") (pinfunction "1A4_10") (pintype "input"))
      (node (ref "U$19") (pin "DR1") (pinfunction "1_DR1") (pintype "bidirectional"))
    )
    (net (code "324") (name "~{DATA9}") (class "Default")
      (node (ref "D13") (pin "15") (pinfunction "15_15") (pintype "passive"))
      (node (ref "IC23") (pin "16") (pinfunction "B3_16") (pintype "bidirectional"))
      (node (ref "IC24") (pin "14") (pinfunction "Y3_14") (pintype "tri_state"))
      (node (ref "IC24") (pin "5") (pinfunction "Y3_5") (pintype "tri_state"))
      (node (ref "IC30") (pin "5") (pinfunction "Y3_5") (pintype "tri_state"))
      (node (ref "IC54") (pin "6") (pinfunction "1A3_6") (pintype "input"))
      (node (ref "U$19") (pin "DS1") (pinfunction "1_DS1") (pintype "bidirectional"))
    )
    (net (code "325") (name "~{DATA10}") (class "Default")
      (node (ref "D13") (pin "17") (pinfunction "17_17") (pintype "passive"))
      (node (ref "IC23") (pin "17") (pinfunction "B2_17") (pintype "bidirectional"))
      (node (ref "IC24") (pin "16") (pinfunction "Y2_16") (pintype "tri_state"))
      (node (ref "IC24") (pin "7") (pinfunction "Y2_7") (pintype "tri_state"))
      (node (ref "IC30") (pin "7") (pinfunction "Y2_7") (pintype "tri_state"))
      (node (ref "IC54") (pin "4") (pinfunction "1A2_4") (pintype "input"))
      (node (ref "U$19") (pin "DU1") (pinfunction "1_DU1") (pintype "bidirectional"))
    )
    (net (code "326") (name "~{DATA11}") (class "Default")
      (node (ref "D13") (pin "18") (pinfunction "18_18") (pintype "passive"))
      (node (ref "IC23") (pin "18") (pinfunction "B1_18") (pintype "bidirectional"))
      (node (ref "IC24") (pin "18") (pinfunction "Y1_18") (pintype "tri_state"))
      (node (ref "IC24") (pin "9") (pinfunction "Y1_9") (pintype "tri_state"))
      (node (ref "IC30") (pin "9") (pinfunction "Y1_9") (pintype "tri_state"))
      (node (ref "IC54") (pin "2") (pinfunction "1A1_2") (pintype "input"))
      (node (ref "U$19") (pin "DV1") (pinfunction "1_DV1") (pintype "bidirectional"))
    )
    (net (code "327") (name "~{DCIM}") (class "Default")
      (node (ref "IC16") (pin "12") (pinfunction "I1_12") (pintype "input"))
      (node (ref "IC51") (pin "9") (pinfunction "Y6_9") (pintype "output"))
    )
    (net (code "328") (name "~{DCXA}") (class "Default")
      (node (ref "IC18") (pin "9") (pinfunction "I0_9") (pintype "input"))
      (node (ref "IC6") (pin "11") (pinfunction "Y1_11") (pintype "output"))
    )
    (net (code "329") (name "~{DIMA}") (class "Default")
      (node (ref "IC22") (pin "3") (pinfunction "I_3") (pintype "input"))
      (node (ref "IC30") (pin "19") (pinfunction "G_19") (pintype "input"))
      (node (ref "IC35") (pin "1") (pinfunction "G_1") (pintype "input"))
      (node (ref "IC35") (pin "19") (pinfunction "G_19") (pintype "input"))
      (node (ref "IC51") (pin "14") (pinfunction "Y1_14") (pintype "output"))
    )
    (net (code "330") (name "~{DIML}") (class "Default")
      (node (ref "FIELD") (pin "11") (pinfunction "LD_11") (pintype "input"))
      (node (ref "IC51") (pin "13") (pinfunction "Y2_13") (pintype "output"))
      (node (ref "INTENB") (pin "11") (pinfunction "LD_11") (pintype "input"))
    )
    (net (code "331") (name "~{DMA-IN}") (class "Default")
      (node (ref "IC12") (pin "11") (pinfunction "I_11") (pintype "input"))
      (node (ref "IC21") (pin "12") (pinfunction "Y0_12") (pintype "output"))
      (node (ref "IC23") (pin "19") (pinfunction "G_19") (pintype "input"))
      (node (ref "IC27") (pin "24") (pinfunction "~{OE}_24") (pintype "input"))
      (node (ref "IC33") (pin "24") (pinfunction "~{OE}_24") (pintype "input"))
      (node (ref "IC39") (pin "19") (pinfunction "G_19") (pintype "input"))
      (node (ref "IC47") (pin "24") (pinfunction "~{OE}_24") (pintype "input"))
      (node (ref "IC48") (pin "24") (pinfunction "~{OE}_24") (pintype "input"))
    )
    (net (code "332") (name "~{DMA-OUT}") (class "Default")
      (node (ref "IC19") (pin "9") (pinfunction "I_9") (pintype "input"))
      (node (ref "IC21") (pin "9") (pinfunction "Y3_9") (pintype "output"))
      (node (ref "IC49") (pin "19") (pinfunction "G_19") (pintype "input"))
      (node (ref "IC50") (pin "19") (pinfunction "G_19") (pintype "input"))
    )
    (net (code "333") (name "~{DSAC}") (class "Default")
      (node (ref "IC19") (pin "5") (pinfunction "I_5") (pintype "input"))
      (node (ref "IC51") (pin "10") (pinfunction "Y5_10") (pintype "output"))
    )
    (net (code "334") (name "~{DT}") (class "Default")
      (node (ref "IC21") (pin "15") (pinfunction "G_15") (pintype "input"))
      (node (ref "IC37") (pin "11") (pinfunction "~{Q3}_11") (pintype "output"))
      (node (ref "IC37") (pin "13") (pinfunction "D4_13") (pintype "input"))
      (node (ref "IC41") (pin "10") (pinfunction "I1_10") (pintype "input"))
      (node (ref "IC44") (pin "1") (pinfunction "OC_1") (pintype "input"))
      (node (ref "IC45") (pin "1") (pinfunction "OC_1") (pintype "input"))
      (node (ref "IC6") (pin "1") (pinfunction "G_1") (pintype "input"))
    )
    (net (code "335") (name "~{DXAC}") (class "Default")
      (node (ref "IC22") (pin "1") (pinfunction "I_1") (pintype "input"))
      (node (ref "IC24") (pin "19") (pinfunction "G_19") (pintype "input"))
      (node (ref "IC26") (pin "19") (pinfunction "G_19") (pintype "input"))
      (node (ref "IC31") (pin "19") (pinfunction "G_19") (pintype "input"))
      (node (ref "IC6") (pin "12") (pinfunction "Y0_12") (pintype "output"))
    )
    (net (code "336") (name "~{D}") (class "Default")
      (node (ref "D14") (pin "9") (pinfunction "9_9") (pintype "passive"))
      (node (ref "U$19") (pin "DK2") (pinfunction "1_DK2") (pintype "bidirectional"))
    )
    (net (code "337") (name "~{EMA0}") (class "Default")
      (node (ref "D10") (pin "4") (pinfunction "4_4") (pintype "passive"))
      (node (ref "IC34") (pin "12") (pinfunction "B7_12") (pintype "bidirectional"))
      (node (ref "IC45") (pin "13") (pinfunction "7Q_13") (pintype "tri_state"))
      (node (ref "U$19") (pin "AD2") (pinfunction "1_AD2") (pintype "bidirectional"))
    )
    (net (code "338") (name "~{EMA1}") (class "Default")
      (node (ref "D10") (pin "5") (pinfunction "5_5") (pintype "passive"))
      (node (ref "IC34") (pin "13") (pinfunction "B6_13") (pintype "bidirectional"))
      (node (ref "IC45") (pin "14") (pinfunction "6Q_14") (pintype "tri_state"))
      (node (ref "U$19") (pin "AE2") (pinfunction "1_AE2") (pintype "bidirectional"))
    )
    (net (code "339") (name "~{EMA2}") (class "Default")
      (node (ref "D10") (pin "7") (pinfunction "7_7") (pintype "passive"))
      (node (ref "IC34") (pin "14") (pinfunction "B5_14") (pintype "bidirectional"))
      (node (ref "IC45") (pin "15") (pinfunction "5Q_15") (pintype "tri_state"))
      (node (ref "U$19") (pin "AH2") (pinfunction "1_AH2") (pintype "bidirectional"))
    )
    (net (code "340") (name "~{ERROR}") (class "Default")
      (node (ref "IC12") (pin "4") (pinfunction "O_4") (pintype "output"))
      (node (ref "IC18") (pin "5") (pinfunction "I1_5") (pintype "input"))
    )
    (net (code "341") (name "~{E}") (class "Default")
      (node (ref "D14") (pin "10") (pinfunction "10_10") (pintype "passive"))
      (node (ref "U$19") (pin "DL2") (pinfunction "1_DL2") (pintype "bidirectional"))
    )
    (net (code "342") (name "~{F.1}") (class "Default")
      (node (ref "IC30") (pin "18") (pinfunction "Y1_18") (pintype "tri_state"))
      (node (ref "IC45") (pin "6") (pinfunction "5D_6") (pintype "input"))
    )
    (net (code "343") (name "~{F.2}") (class "Default")
      (node (ref "IC30") (pin "16") (pinfunction "Y2_16") (pintype "tri_state"))
      (node (ref "IC45") (pin "7") (pinfunction "6D_7") (pintype "input"))
    )
    (net (code "344") (name "~{F.3}") (class "Default")
      (node (ref "IC30") (pin "14") (pinfunction "Y3_14") (pintype "tri_state"))
      (node (ref "IC45") (pin "8") (pinfunction "7D_8") (pintype "input"))
      (node (ref "IC45") (pin "9") (pinfunction "8D_9") (pintype "input"))
    )
    (net (code "345") (name "~{FSET}") (class "Default")
      (node (ref "D14") (pin "13") (pinfunction "13_13") (pintype "passive"))
      (node (ref "U$19") (pin "DP2") (pinfunction "1_DP2") (pintype "bidirectional"))
    )
    (net (code "346") (name "~{F}") (class "Default")
      (node (ref "D14") (pin "8") (pinfunction "8_8") (pintype "passive"))
      (node (ref "U$19") (pin "DJ2") (pinfunction "1_DJ2") (pintype "bidirectional"))
    )
    (net (code "347") (name "~{IND1}") (class "Default")
      (node (ref "D12") (pin "17") (pinfunction "17_17") (pintype "passive"))
      (node (ref "U$19") (pin "CU2") (pinfunction "1_CU2") (pintype "bidirectional"))
    )
    (net (code "348") (name "~{IND2}") (class "Default")
      (node (ref "D12") (pin "18") (pinfunction "18_18") (pintype "passive"))
      (node (ref "U$19") (pin "CV2") (pinfunction "1_CV2") (pintype "bidirectional"))
    )
    (net (code "349") (name "~{INITIALIZE}") (class "Default")
      (node (ref "IC10") (pin "1") (pinfunction "CLR_1") (pintype "input"))
      (node (ref "IC10") (pin "13") (pinfunction "CLR_13") (pintype "input"))
      (node (ref "IC12") (pin "12") (pinfunction "O_12") (pintype "output"))
      (node (ref "IC18") (pin "10") (pinfunction "I1_10") (pintype "input"))
      (node (ref "IC18") (pin "13") (pinfunction "I1_13") (pintype "input"))
      (node (ref "IC37") (pin "1") (pinfunction "CLR_1") (pintype "input"))
      (node (ref "IC9") (pin "1") (pinfunction "CLR_1") (pintype "input"))
      (node (ref "IC9") (pin "13") (pinfunction "CLR_13") (pintype "input"))
    )
    (net (code "350") (name "~{INTERNAL_IO}") (class "Default")
      (node (ref "D11") (pin "10") (pinfunction "10_10") (pintype "passive"))
      (node (ref "IC22") (pin "8") (pinfunction "O_8") (pintype "open_collector"))
      (node (ref "U$19") (pin "CL1") (pinfunction "1_CL1") (pintype "bidirectional"))
    )
    (net (code "351") (name "~{INT_RQST}") (class "Default")
      (node (ref "D11") (pin "13") (pinfunction "13_13") (pintype "passive"))
      (node (ref "U$19") (pin "CP1") (pinfunction "1_CP1") (pintype "bidirectional"))
    )
    (net (code "352") (name "~{INT_RQ}") (class "Default")
      (node (ref "IC38") (pin "3") (pinfunction "O_3") (pintype "open_collector"))
      (node (ref "IC38") (pin "6") (pinfunction "O_6") (pintype "open_collector"))
      (node (ref "IC38") (pin "8") (pinfunction "O_8") (pintype "open_collector"))
    )
    (net (code "353") (name "~{IO_PAUSE}") (class "Default")
      (node (ref "D11") (pin "4") (pinfunction "4_4") (pintype "passive"))
      (node (ref "IC36") (pin "4") (pinfunction "G2A_4") (pintype "input"))
      (node (ref "U$19") (pin "CD1") (pinfunction "1_CD1") (pintype "bidirectional"))
    )
    (net (code "354") (name "~{IR0}") (class "Default")
      (node (ref "D14") (pin "4") (pinfunction "4_4") (pintype "passive"))
      (node (ref "U$19") (pin "DD2") (pinfunction "1_DD2") (pintype "bidirectional"))
    )
    (net (code "355") (name "~{IR1}") (class "Default")
      (node (ref "D14") (pin "5") (pinfunction "5_5") (pintype "passive"))
      (node (ref "U$19") (pin "DE2") (pinfunction "1_DE2") (pintype "bidirectional"))
    )
    (net (code "356") (name "~{IR2}") (class "Default")
      (node (ref "D14") (pin "7") (pinfunction "7_7") (pintype "passive"))
      (node (ref "U$19") (pin "DH2") (pinfunction "1_DH2") (pintype "bidirectional"))
    )
    (net (code "357") (name "~{KEY_CONT}") (class "Default")
      (node (ref "D14") (pin "17") (pinfunction "17_17") (pintype "passive"))
      (node (ref "U$19") (pin "DU2") (pinfunction "1_DU2") (pintype "bidirectional"))
    )
    (net (code "358") (name "~{LA_ENABLE}") (class "Default")
      (node (ref "D8") (pin "11") (pinfunction "11_11") (pintype "passive"))
      (node (ref "U$19") (pin "BM2") (pinfunction "1_BM2") (pintype "bidirectional"))
    )
    (net (code "359") (name "~{LINK_DATA}") (class "Default")
      (node (ref "D12") (pin "14") (pinfunction "14_14") (pintype "passive"))
      (node (ref "U$19") (pin "CR2") (pinfunction "1_CR2") (pintype "bidirectional"))
    )
    (net (code "360") (name "~{LINK_LOAD}") (class "Default")
      (node (ref "D12") (pin "15") (pinfunction "15_15") (pintype "passive"))
      (node (ref "U$19") (pin "CS2") (pinfunction "1_CS2") (pintype "bidirectional"))
    )
    (net (code "361") (name "~{LINK}") (class "Default")
      (node (ref "D10") (pin "18") (pinfunction "18_18") (pintype "passive"))
      (node (ref "U$19") (pin "AV2") (pinfunction "1_AV2") (pintype "bidirectional"))
    )
    (net (code "362") (name "~{LOAD_CONT}") (class "Default")
      (node (ref "D8") (pin "7") (pinfunction "7_7") (pintype "passive"))
      (node (ref "IC43") (pin "12") (pinfunction "O_12") (pintype "open_collector"))
      (node (ref "U$19") (pin "BH2") (pinfunction "1_BH2") (pintype "bidirectional"))
    )
    (net (code "363") (name "~{MA00}") (class "Default")
      (node (ref "D9") (pin "4") (pinfunction "4_4") (pintype "passive"))
      (node (ref "IC34") (pin "15") (pinfunction "B4_15") (pintype "bidirectional"))
      (node (ref "IC45") (pin "16") (pinfunction "4Q_16") (pintype "tri_state"))
      (node (ref "U$19") (pin "AD1") (pinfunction "1_AD1") (pintype "bidirectional"))
    )
    (net (code "364") (name "~{MA01}") (class "Default")
      (node (ref "D9") (pin "5") (pinfunction "5_5") (pintype "passive"))
      (node (ref "IC34") (pin "16") (pinfunction "B3_16") (pintype "bidirectional"))
      (node (ref "IC45") (pin "17") (pinfunction "3Q_17") (pintype "tri_state"))
      (node (ref "U$19") (pin "AE1") (pinfunction "1_AE1") (pintype "bidirectional"))
    )
    (net (code "365") (name "~{MA02}") (class "Default")
      (node (ref "D9") (pin "7") (pinfunction "7_7") (pintype "passive"))
      (node (ref "IC34") (pin "17") (pinfunction "B2_17") (pintype "bidirectional"))
      (node (ref "IC45") (pin "18") (pinfunction "2Q_18") (pintype "tri_state"))
      (node (ref "U$19") (pin "AH1") (pinfunction "1_AH1") (pintype "bidirectional"))
    )
    (net (code "366") (name "~{MA03}") (class "Default")
      (node (ref "D9") (pin "8") (pinfunction "8_8") (pintype "passive"))
      (node (ref "IC34") (pin "18") (pinfunction "B1_18") (pintype "bidirectional"))
      (node (ref "IC45") (pin "19") (pinfunction "1Q_19") (pintype "tri_state"))
      (node (ref "U$19") (pin "AJ1") (pinfunction "1_AJ1") (pintype "bidirectional"))
    )
    (net (code "367") (name "~{MA04}") (class "Default")
      (node (ref "D7") (pin "4") (pinfunction "4_4") (pintype "passive"))
      (node (ref "IC28") (pin "11") (pinfunction "B8_11") (pintype "bidirectional"))
      (node (ref "IC44") (pin "12") (pinfunction "8Q_12") (pintype "tri_state"))
      (node (ref "U$19") (pin "BD1") (pinfunction "1_BD1") (pintype "bidirectional"))
    )
    (net (code "368") (name "~{MA05}") (class "Default")
      (node (ref "D7") (pin "5") (pinfunction "5_5") (pintype "passive"))
      (node (ref "IC28") (pin "12") (pinfunction "B7_12") (pintype "bidirectional"))
      (node (ref "IC44") (pin "13") (pinfunction "7Q_13") (pintype "tri_state"))
      (node (ref "U$19") (pin "BE1") (pinfunction "1_BE1") (pintype "bidirectional"))
    )
    (net (code "369") (name "~{MA06}") (class "Default")
      (node (ref "D7") (pin "7") (pinfunction "7_7") (pintype "passive"))
      (node (ref "IC28") (pin "13") (pinfunction "B6_13") (pintype "bidirectional"))
      (node (ref "IC44") (pin "14") (pinfunction "6Q_14") (pintype "tri_state"))
      (node (ref "U$19") (pin "BH1") (pinfunction "1_BH1") (pintype "bidirectional"))
    )
    (net (code "370") (name "~{MA07}") (class "Default")
      (node (ref "D7") (pin "8") (pinfunction "8_8") (pintype "passive"))
      (node (ref "IC28") (pin "14") (pinfunction "B5_14") (pintype "bidirectional"))
      (node (ref "IC44") (pin "15") (pinfunction "5Q_15") (pintype "tri_state"))
      (node (ref "U$19") (pin "BJ1") (pinfunction "1_BJ1") (pintype "bidirectional"))
    )
    (net (code "371") (name "~{MA08}") (class "Default")
      (node (ref "D13") (pin "4") (pinfunction "4_4") (pintype "passive"))
      (node (ref "IC28") (pin "15") (pinfunction "B4_15") (pintype "bidirectional"))
      (node (ref "IC44") (pin "16") (pinfunction "4Q_16") (pintype "tri_state"))
      (node (ref "U$19") (pin "DD1") (pinfunction "1_DD1") (pintype "bidirectional"))
    )
    (net (code "372") (name "~{MA09}") (class "Default")
      (node (ref "D13") (pin "5") (pinfunction "5_5") (pintype "passive"))
      (node (ref "IC28") (pin "16") (pinfunction "B3_16") (pintype "bidirectional"))
      (node (ref "IC44") (pin "17") (pinfunction "3Q_17") (pintype "tri_state"))
      (node (ref "U$19") (pin "DE1") (pinfunction "1_DE1") (pintype "bidirectional"))
    )
    (net (code "373") (name "~{MA10}") (class "Default")
      (node (ref "D13") (pin "7") (pinfunction "7_7") (pintype "passive"))
      (node (ref "IC28") (pin "17") (pinfunction "B2_17") (pintype "bidirectional"))
      (node (ref "IC44") (pin "18") (pinfunction "2Q_18") (pintype "tri_state"))
      (node (ref "U$19") (pin "DH1") (pinfunction "1_DH1") (pintype "bidirectional"))
    )
    (net (code "374") (name "~{MA11}") (class "Default")
      (node (ref "D13") (pin "8") (pinfunction "8_8") (pintype "passive"))
      (node (ref "IC28") (pin "18") (pinfunction "B1_18") (pintype "bidirectional"))
      (node (ref "IC44") (pin "19") (pinfunction "1Q_19") (pintype "tri_state"))
      (node (ref "U$19") (pin "DJ1") (pinfunction "1_DJ1") (pintype "bidirectional"))
    )
    (net (code "375") (name "~{MD00}") (class "Default")
      (node (ref "D9") (pin "9") (pinfunction "9_9") (pintype "passive"))
      (node (ref "IC45") (pin "5") (pinfunction "4D_5") (pintype "input"))
      (node (ref "IC50") (pin "5") (pinfunction "A4_5") (pintype "bidirectional"))
      (node (ref "U$19") (pin "AK1") (pinfunction "1_AK1") (pintype "bidirectional"))
    )
    (net (code "376") (name "~{MD01}") (class "Default")
      (node (ref "D9") (pin "10") (pinfunction "10_10") (pintype "passive"))
      (node (ref "IC45") (pin "4") (pinfunction "3D_4") (pintype "input"))
      (node (ref "IC50") (pin "4") (pinfunction "A3_4") (pintype "bidirectional"))
      (node (ref "U$19") (pin "AL1") (pinfunction "1_AL1") (pintype "bidirectional"))
    )
    (net (code "377") (name "~{MD02}") (class "Default")
      (node (ref "D9") (pin "11") (pinfunction "11_11") (pintype "passive"))
      (node (ref "IC45") (pin "3") (pinfunction "2D_3") (pintype "input"))
      (node (ref "IC50") (pin "3") (pinfunction "A2_3") (pintype "bidirectional"))
      (node (ref "U$19") (pin "AM1") (pinfunction "1_AM1") (pintype "bidirectional"))
    )
    (net (code "378") (name "~{MD03}") (class "Default")
      (node (ref "D9") (pin "13") (pinfunction "13_13") (pintype "passive"))
      (node (ref "IC45") (pin "2") (pinfunction "1D_2") (pintype "input"))
      (node (ref "IC50") (pin "2") (pinfunction "A1_2") (pintype "bidirectional"))
      (node (ref "U$19") (pin "AP1") (pinfunction "1_AP1") (pintype "bidirectional"))
    )
    (net (code "379") (name "~{MD04}") (class "Default")
      (node (ref "D7") (pin "9") (pinfunction "9_9") (pintype "passive"))
      (node (ref "IC44") (pin "9") (pinfunction "8D_9") (pintype "input"))
      (node (ref "IC49") (pin "9") (pinfunction "A8_9") (pintype "bidirectional"))
      (node (ref "U$19") (pin "BK1") (pinfunction "1_BK1") (pintype "bidirectional"))
    )
    (net (code "380") (name "~{MD05}") (class "Default")
      (node (ref "D7") (pin "10") (pinfunction "10_10") (pintype "passive"))
      (node (ref "IC44") (pin "8") (pinfunction "7D_8") (pintype "input"))
      (node (ref "IC49") (pin "8") (pinfunction "A7_8") (pintype "bidirectional"))
      (node (ref "U$19") (pin "BL1") (pinfunction "1_BL1") (pintype "bidirectional"))
    )
    (net (code "381") (name "~{MD06}") (class "Default")
      (node (ref "D7") (pin "11") (pinfunction "11_11") (pintype "passive"))
      (node (ref "IC44") (pin "7") (pinfunction "6D_7") (pintype "input"))
      (node (ref "IC49") (pin "7") (pinfunction "A6_7") (pintype "bidirectional"))
      (node (ref "U$19") (pin "BM1") (pinfunction "1_BM1") (pintype "bidirectional"))
    )
    (net (code "382") (name "~{MD07}") (class "Default")
      (node (ref "D7") (pin "13") (pinfunction "13_13") (pintype "passive"))
      (node (ref "IC44") (pin "6") (pinfunction "5D_6") (pintype "input"))
      (node (ref "IC49") (pin "6") (pinfunction "A5_6") (pintype "bidirectional"))
      (node (ref "U$19") (pin "BP1") (pinfunction "1_BP1") (pintype "bidirectional"))
    )
    (net (code "383") (name "~{MD08}") (class "Default")
      (node (ref "D13") (pin "9") (pinfunction "9_9") (pintype "passive"))
      (node (ref "IC44") (pin "5") (pinfunction "4D_5") (pintype "input"))
      (node (ref "IC49") (pin "5") (pinfunction "A4_5") (pintype "bidirectional"))
      (node (ref "U$19") (pin "DK1") (pinfunction "1_DK1") (pintype "bidirectional"))
    )
    (net (code "384") (name "~{MD09}") (class "Default")
      (node (ref "D13") (pin "10") (pinfunction "10_10") (pintype "passive"))
      (node (ref "IC44") (pin "4") (pinfunction "3D_4") (pintype "input"))
      (node (ref "IC49") (pin "4") (pinfunction "A3_4") (pintype "bidirectional"))
      (node (ref "U$19") (pin "DL1") (pinfunction "1_DL1") (pintype "bidirectional"))
    )
    (net (code "385") (name "~{MD10}") (class "Default")
      (node (ref "D13") (pin "11") (pinfunction "11_11") (pintype "passive"))
      (node (ref "IC44") (pin "3") (pinfunction "2D_3") (pintype "input"))
      (node (ref "IC49") (pin "3") (pinfunction "A2_3") (pintype "bidirectional"))
      (node (ref "U$19") (pin "DM1") (pinfunction "1_DM1") (pintype "bidirectional"))
    )
    (net (code "386") (name "~{MD11}") (class "Default")
      (node (ref "D13") (pin "13") (pinfunction "13_13") (pintype "passive"))
      (node (ref "IC44") (pin "2") (pinfunction "1D_2") (pintype "input"))
      (node (ref "IC49") (pin "2") (pinfunction "A1_2") (pintype "bidirectional"))
      (node (ref "U$19") (pin "DP1") (pinfunction "1_DP1") (pintype "bidirectional"))
    )
    (net (code "387") (name "~{MD_DIR}") (class "Default")
      (node (ref "D10") (pin "9") (pinfunction "9_9") (pintype "passive"))
      (node (ref "IC19") (pin "8") (pinfunction "O_8") (pintype "open_collector"))
      (node (ref "U$19") (pin "AK2") (pinfunction "1_AK2") (pintype "bidirectional"))
    )
    (net (code "388") (name "~{MEM_START}") (class "Default")
      (node (ref "D10") (pin "8") (pinfunction "8_8") (pintype "passive"))
      (node (ref "U$19") (pin "AJ2") (pinfunction "1_AJ2") (pintype "bidirectional"))
    )
    (net (code "389") (name "~{MS_DISABLE}") (class "Default")
      (node (ref "D11") (pin "18") (pinfunction "18_18") (pintype "passive"))
      (node (ref "IC43") (pin "8") (pinfunction "O_8") (pintype "open_collector"))
      (node (ref "U$19") (pin "CV1") (pinfunction "1_CV1") (pintype "bidirectional"))
    )
    (net (code "390") (name "~{MYDEV}") (class "Default")
      (node (ref "IC22") (pin "9") (pinfunction "I_9") (pintype "input"))
      (node (ref "IC25") (pin "4") (pinfunction "G2A_4") (pintype "input"))
      (node (ref "IC29") (pin "4") (pinfunction "G2A_4") (pintype "input"))
      (node (ref "IC32") (pin "4") (pinfunction "G2A_4") (pintype "input"))
      (node (ref "MYDEV") (pin "1") (pinfunction "P_1") (pintype "passive"))
    )
    (net (code "391") (name "~{MY_DB}") (class "Default")
      (node (ref "IC40") (pin "6") (pinfunction "~{Q}_6") (pintype "output"))
      (node (ref "IC43") (pin "11") (pinfunction "I_11") (pintype "input"))
      (node (ref "IC43") (pin "9") (pinfunction "I_9") (pintype "input"))
      (node (ref "SV1") (pin "11") (pinfunction "11_11") (pintype "passive"))
    )
    (net (code "392") (name "~{NOT_LAST_TR}") (class "Default")
      (node (ref "D11") (pin "11") (pinfunction "11_11") (pintype "passive"))
      (node (ref "U$19") (pin "CM1") (pinfunction "1_CM1") (pintype "bidirectional"))
    )
    (net (code "393") (name "~{NTS_STALL}") (class "Default")
      (node (ref "D8") (pin "14") (pinfunction "14_14") (pintype "passive"))
      (node (ref "U$19") (pin "BR2") (pinfunction "1_BR2") (pintype "bidirectional"))
    )
    (net (code "394") (name "~{OVERFLOW}") (class "Default")
      (node (ref "D8") (pin "8") (pinfunction "8_8") (pintype "passive"))
      (node (ref "IC52") (pin "2") (pinfunction "I0_2") (pintype "input"))
      (node (ref "U$19") (pin "BJ2") (pinfunction "1_BJ2") (pintype "bidirectional"))
    )
    (net (code "395") (name "~{PCA}") (class "Default")
      (node (ref "IC12") (pin "9") (pinfunction "I_9") (pintype "input"))
      (node (ref "IC8") (pin "5") (pinfunction "Q_5") (pintype "output"))
      (node (ref "RL") (pin "2") (pinfunction "2_2") (pintype "passive"))
    )
    (net (code "396") (name "~{PER}") (class "Default")
      (node (ref "IC5") (pin "10") (pinfunction "I1_10") (pintype "input"))
      (node (ref "IC5") (pin "9") (pinfunction "I0_9") (pintype "input"))
      (node (ref "IC9") (pin "8") (pinfunction "~{Q}_8") (pintype "output"))
    )
    (net (code "397") (name "~{ROM_ADDR}") (class "Default")
      (node (ref "D10") (pin "17") (pinfunction "17_17") (pintype "passive"))
      (node (ref "U$19") (pin "AU2") (pinfunction "1_AU2") (pintype "bidirectional"))
    )
    (net (code "398") (name "~{RUN}") (class "Default")
      (node (ref "D8") (pin "17") (pinfunction "17_17") (pintype "passive"))
      (node (ref "U$19") (pin "BU2") (pinfunction "1_BU2") (pintype "bidirectional"))
    )
    (net (code "399") (name "~{SETPER}") (class "Default")
      (node (ref "IC13") (pin "5") (pinfunction "EVN_5") (pintype "output"))
      (node (ref "IC9") (pin "10") (pinfunction "PRE_10") (pintype "input"))
    )
    (net (code "400") (name "~{SETWLS}") (class "Default")
      (node (ref "IC6") (pin "7") (pinfunction "Y3_7") (pintype "output"))
      (node (ref "IC9") (pin "4") (pinfunction "PRE_4") (pintype "input"))
    )
    (net (code "401") (name "~{SKIP}") (class "Default")
      (node (ref "D11") (pin "15") (pinfunction "15_15") (pintype "passive"))
      (node (ref "IC22") (pin "10") (pinfunction "O_10") (pintype "open_collector"))
      (node (ref "U$19") (pin "CS1") (pinfunction "1_CS1") (pintype "bidirectional"))
    )
    (net (code "402") (name "~{SKP}") (class "Default")
      (node (ref "IC17") (pin "2") (pinfunction "A_2") (pintype "input"))
      (node (ref "IC19") (pin "2") (pinfunction "O_2") (pintype "open_collector"))
      (node (ref "IC19") (pin "4") (pinfunction "O_4") (pintype "open_collector"))
      (node (ref "IC19") (pin "6") (pinfunction "O_6") (pintype "open_collector"))
      (node (ref "R1") (pin "1") (pinfunction "1_1") (pintype "passive"))
    )
    (net (code "403") (name "~{START}") (class "Default")
      (node (ref "DMA0-3") (pin "11") (pinfunction "LD_11") (pintype "input"))
      (node (ref "DMA4-7") (pin "11") (pinfunction "LD_11") (pintype "input"))
      (node (ref "DMA8-11") (pin "11") (pinfunction "LD_11") (pintype "input"))
      (node (ref "IC10") (pin "10") (pinfunction "PRE_10") (pintype "input"))
      (node (ref "IC12") (pin "6") (pinfunction "O_6") (pintype "output"))
    )
    (net (code "404") (name "~{STOP}") (class "Default")
      (node (ref "D14") (pin "15") (pinfunction "15_15") (pintype "passive"))
      (node (ref "U$19") (pin "DS2") (pinfunction "1_DS2") (pintype "bidirectional"))
    )
    (net (code "405") (name "~{TS1}") (class "Default")
      (node (ref "D12") (pin "9") (pinfunction "9_9") (pintype "passive"))
      (node (ref "U$19") (pin "CK2") (pinfunction "1_CK2") (pintype "bidirectional"))
    )
    (net (code "406") (name "~{TS2}") (class "Default")
      (node (ref "D12") (pin "10") (pinfunction "10_10") (pintype "passive"))
      (node (ref "U$19") (pin "CL2") (pinfunction "1_CL2") (pintype "bidirectional"))
    )
    (net (code "407") (name "~{TS3}") (class "Default")
      (node (ref "D12") (pin "11") (pinfunction "11_11") (pintype "passive"))
      (node (ref "U$19") (pin "CM2") (pinfunction "1_CM2") (pintype "bidirectional"))
    )
    (net (code "408") (name "~{TS4}") (class "Default")
      (node (ref "D12") (pin "13") (pinfunction "13_13") (pintype "passive"))
      (node (ref "IC12") (pin "1") (pinfunction "I_1") (pintype "input"))
      (node (ref "U$19") (pin "CP2") (pinfunction "1_CP2") (pintype "bidirectional"))
    )
    (net (code "409") (name "~{USER_MODE}") (class "Default")
      (node (ref "D14") (pin "11") (pinfunction "11_11") (pintype "passive"))
      (node (ref "U$19") (pin "DM2") (pinfunction "1_DM2") (pintype "bidirectional"))
    )
    (net (code "410") (name "~{WC}") (class "Default")
      (node (ref "IC37") (pin "3") (pinfunction "~{Q1}_3") (pintype "output"))
      (node (ref "IC52") (pin "3") (pinfunction "I1_3") (pintype "input"))
    )
    (net (code "411") (name "~{WE}") (class "Default")
      (node (ref "IC27") (pin "29") (pinfunction "~{WE}_29") (pintype "input"))
      (node (ref "IC33") (pin "29") (pinfunction "~{WE}_29") (pintype "input"))
      (node (ref "IC47") (pin "29") (pinfunction "~{WE}_29") (pintype "input"))
      (node (ref "IC48") (pin "29") (pinfunction "~{WE}_29") (pintype "input"))
      (node (ref "IC6") (pin "5") (pinfunction "Y1_5") (pintype "output"))
    )
    (net (code "412") (name "~{WLS}") (class "Default")
      (node (ref "IC5") (pin "12") (pinfunction "I2_12") (pintype "input"))
      (node (ref "IC5") (pin "13") (pinfunction "I3_13") (pintype "input"))
      (node (ref "IC9") (pin "6") (pinfunction "~{Q}_6") (pintype "output"))
    )
    (net (code "413") (name "~{WORD}") (class "Default")
      (node (ref "IC16") (pin "2") (pinfunction "I0_2") (pintype "input"))
      (node (ref "IC8") (pin "9") (pinfunction "Q_9") (pintype "output"))
    )
  )
)
